# microBoard_power.net
KiCad netlist of a schematic drawn in EAGLE
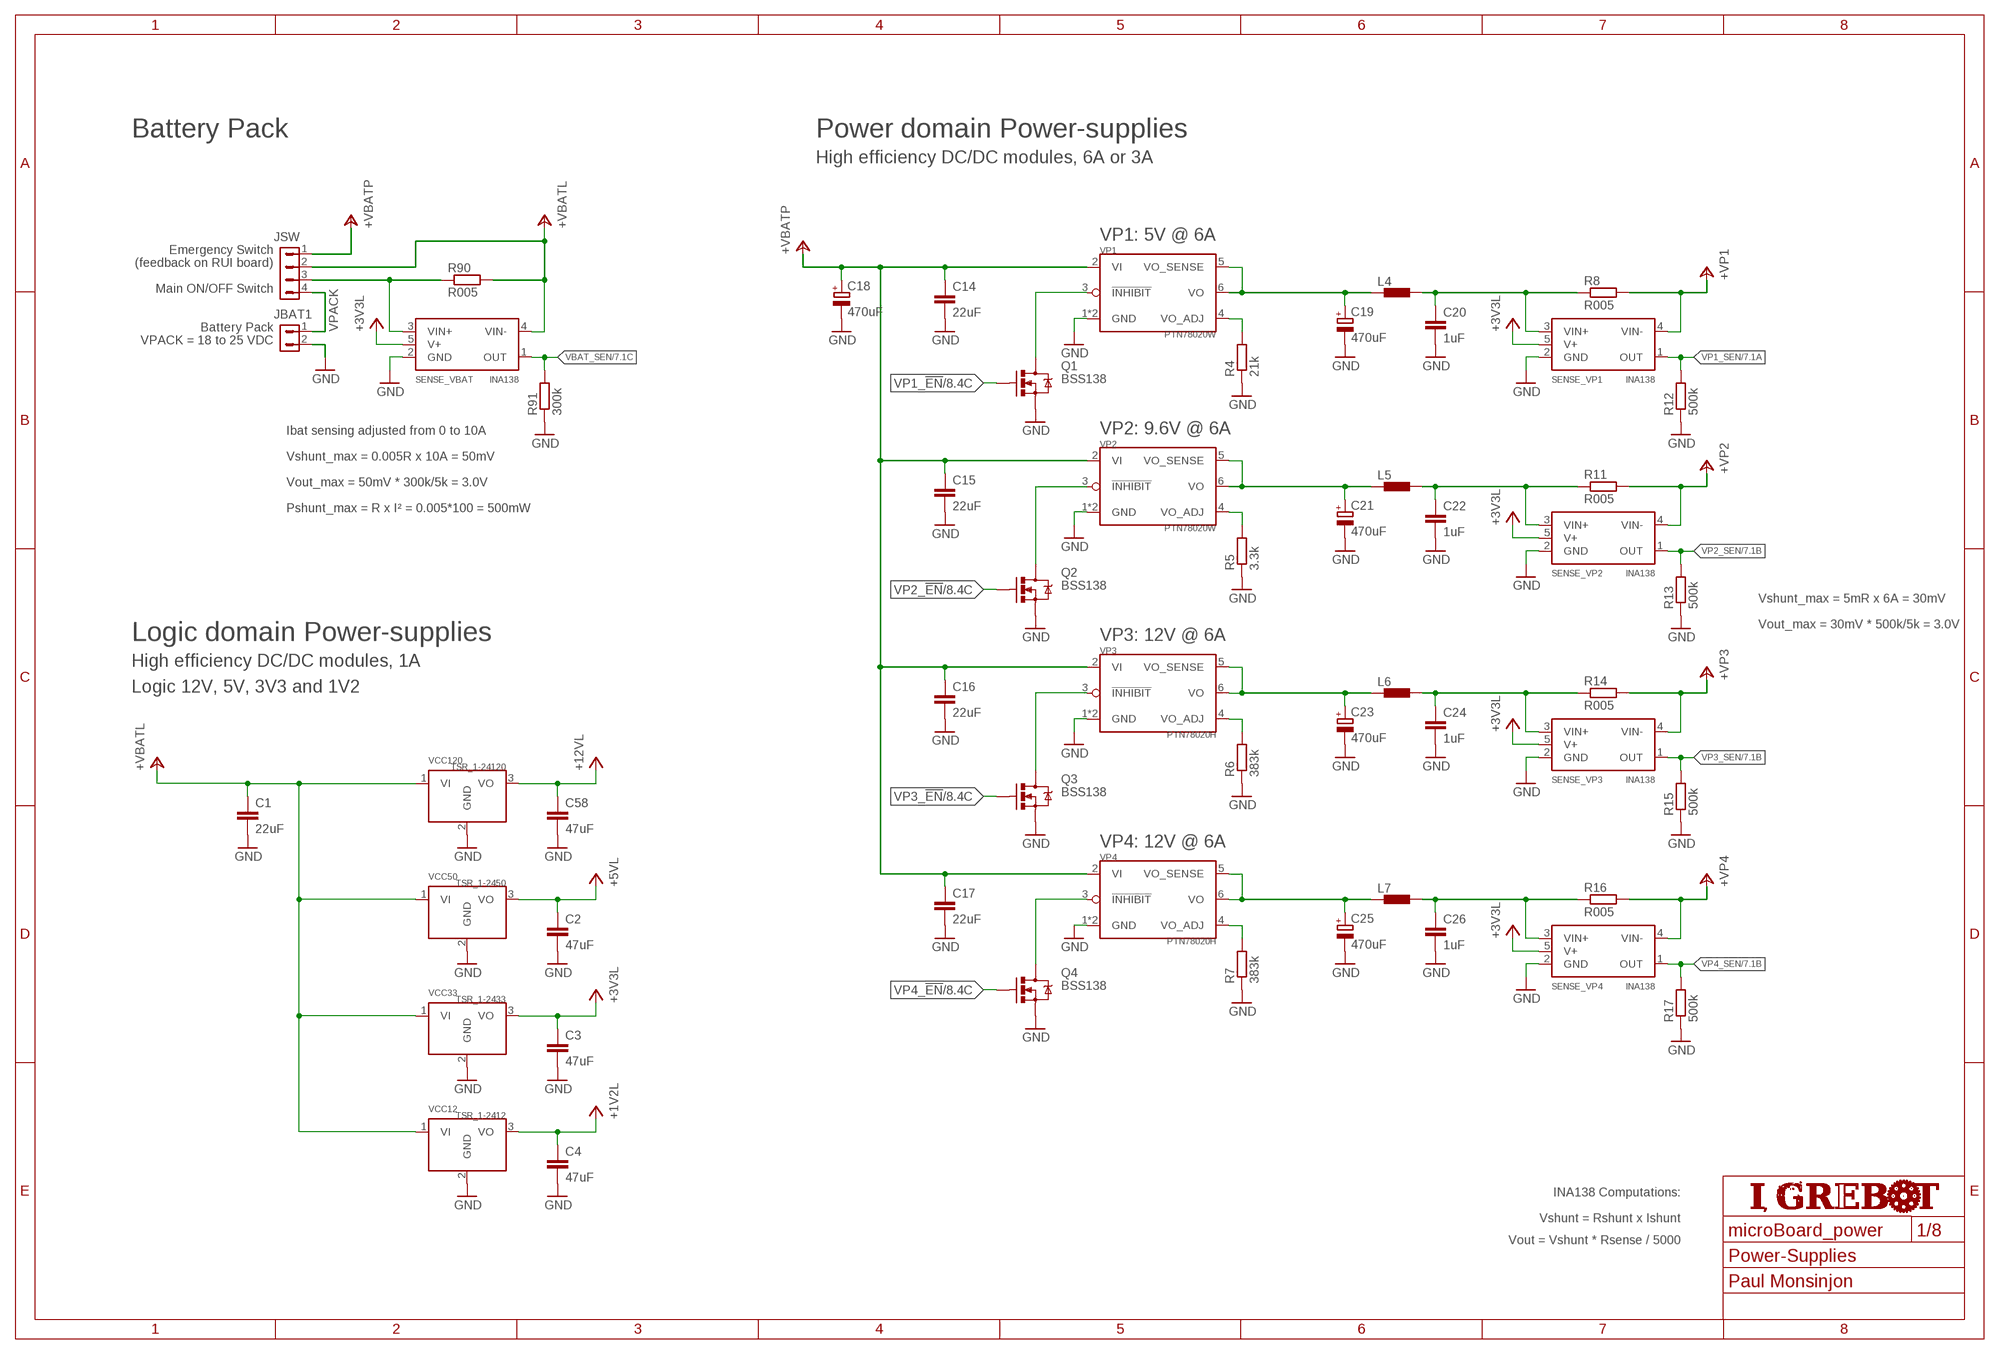
[diagram p0: schematic, sheet 1]
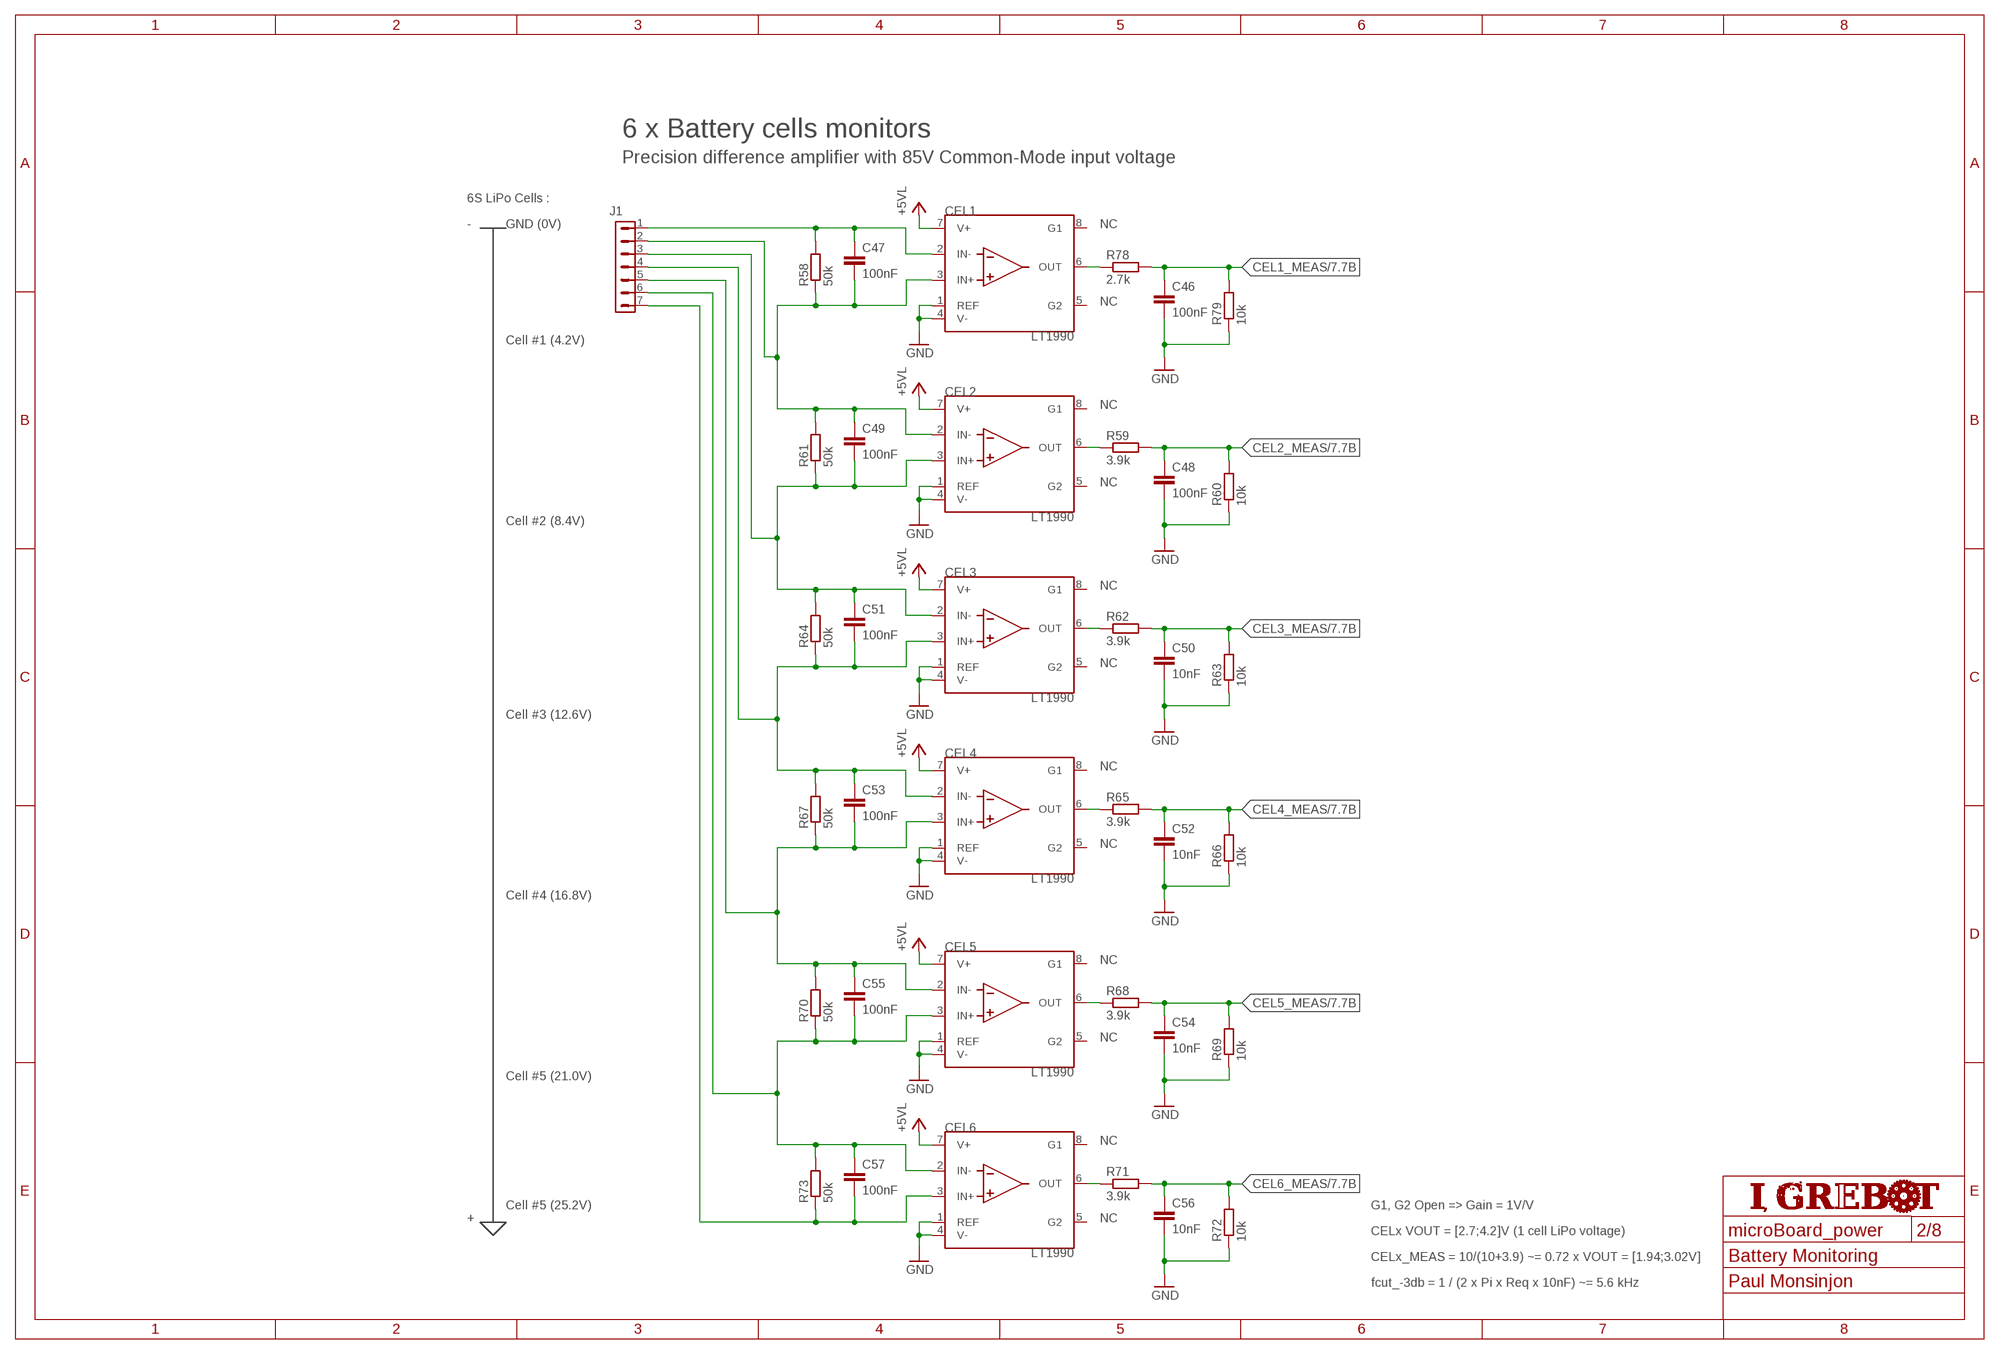
[diagram p1: schematic, sheet 2]
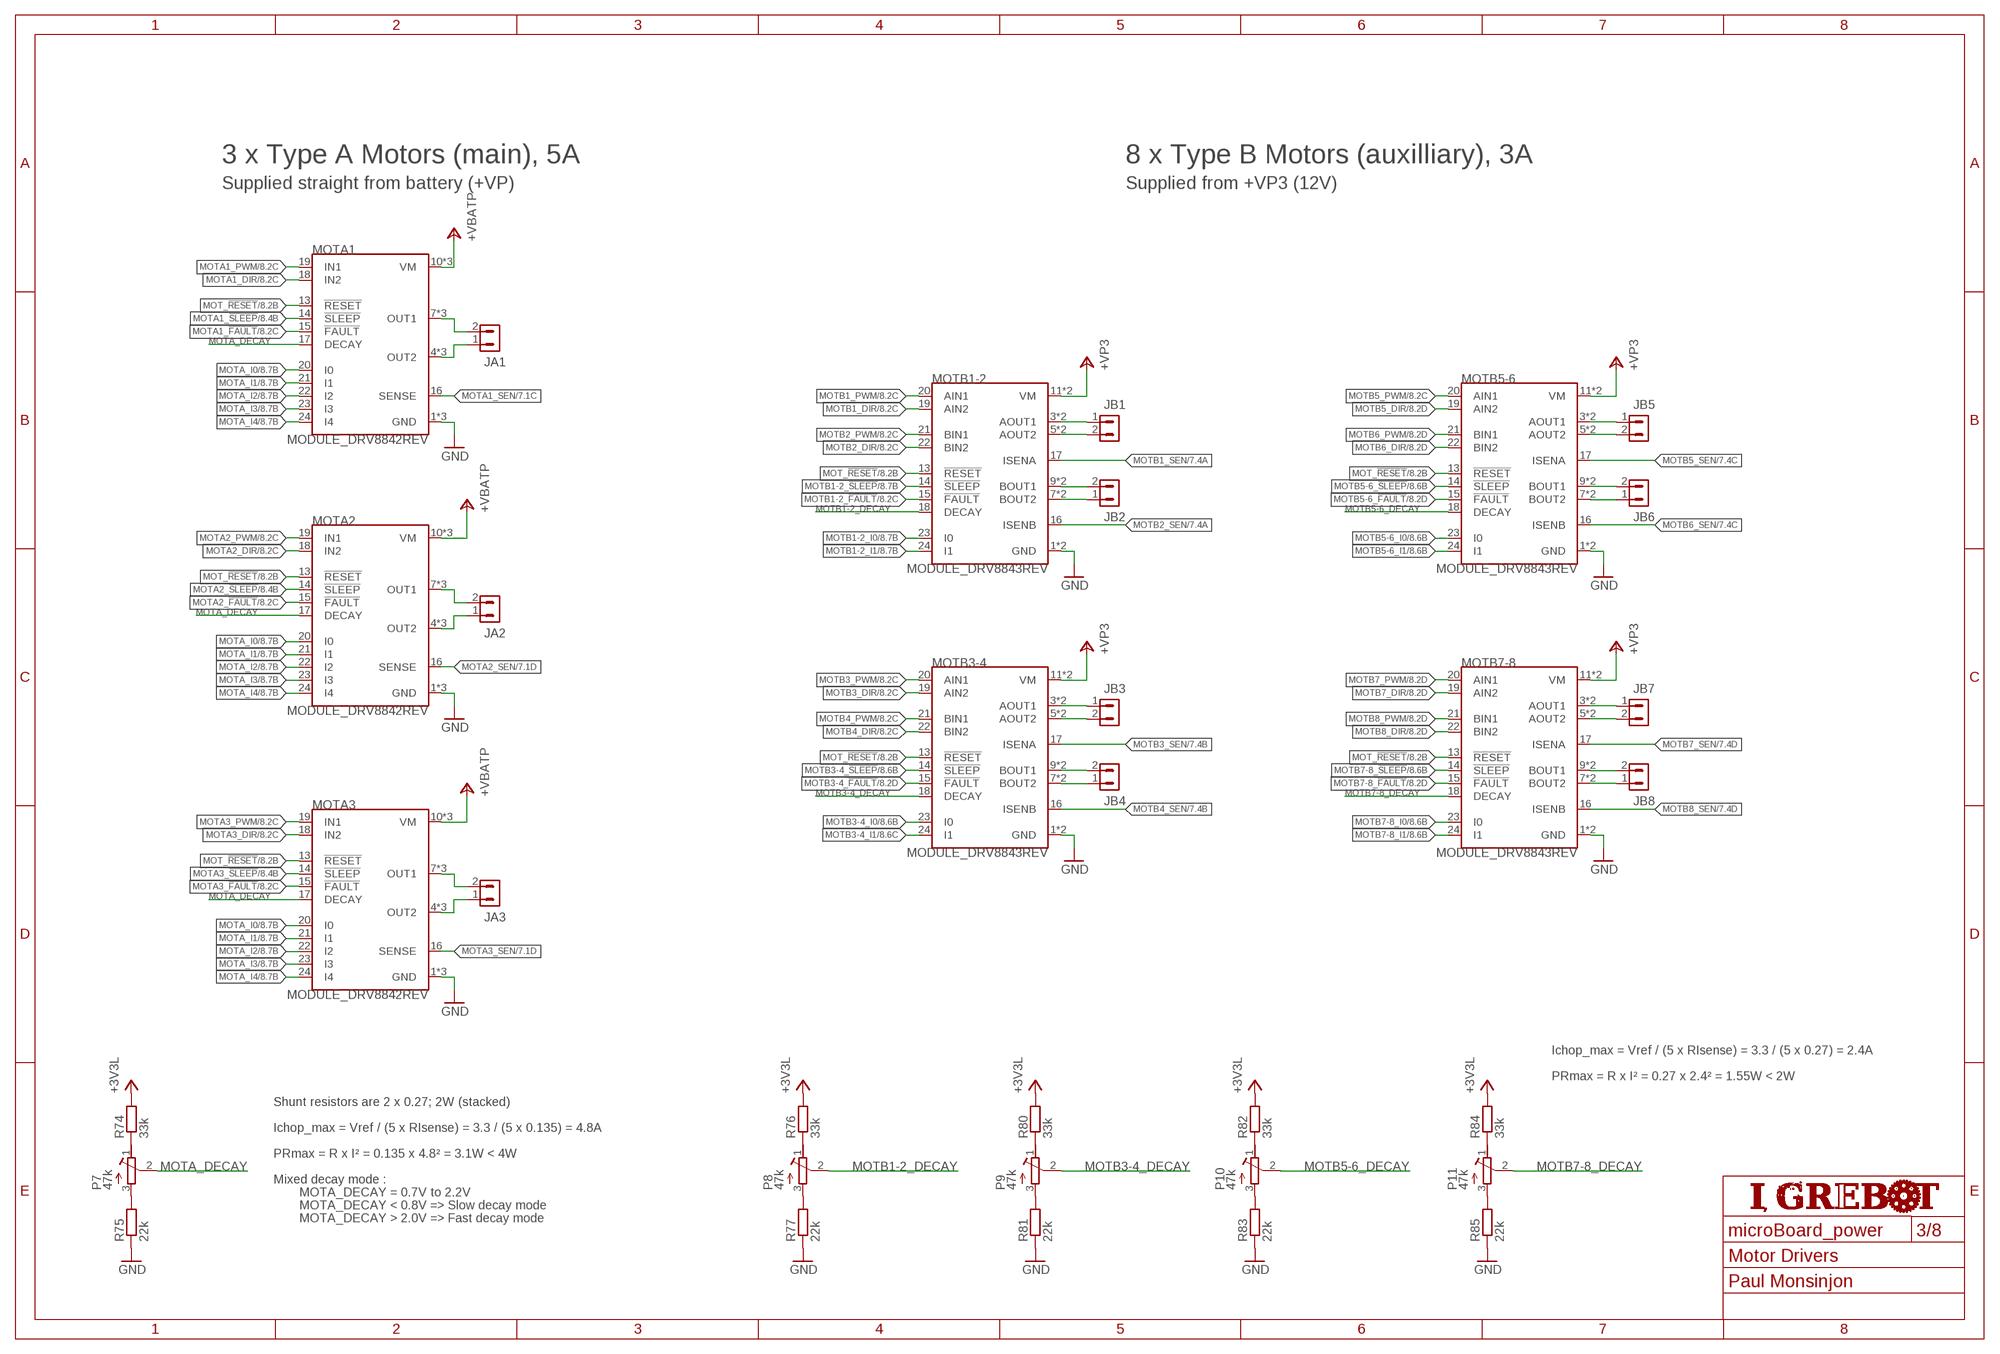
[diagram p2: schematic, sheet 3]
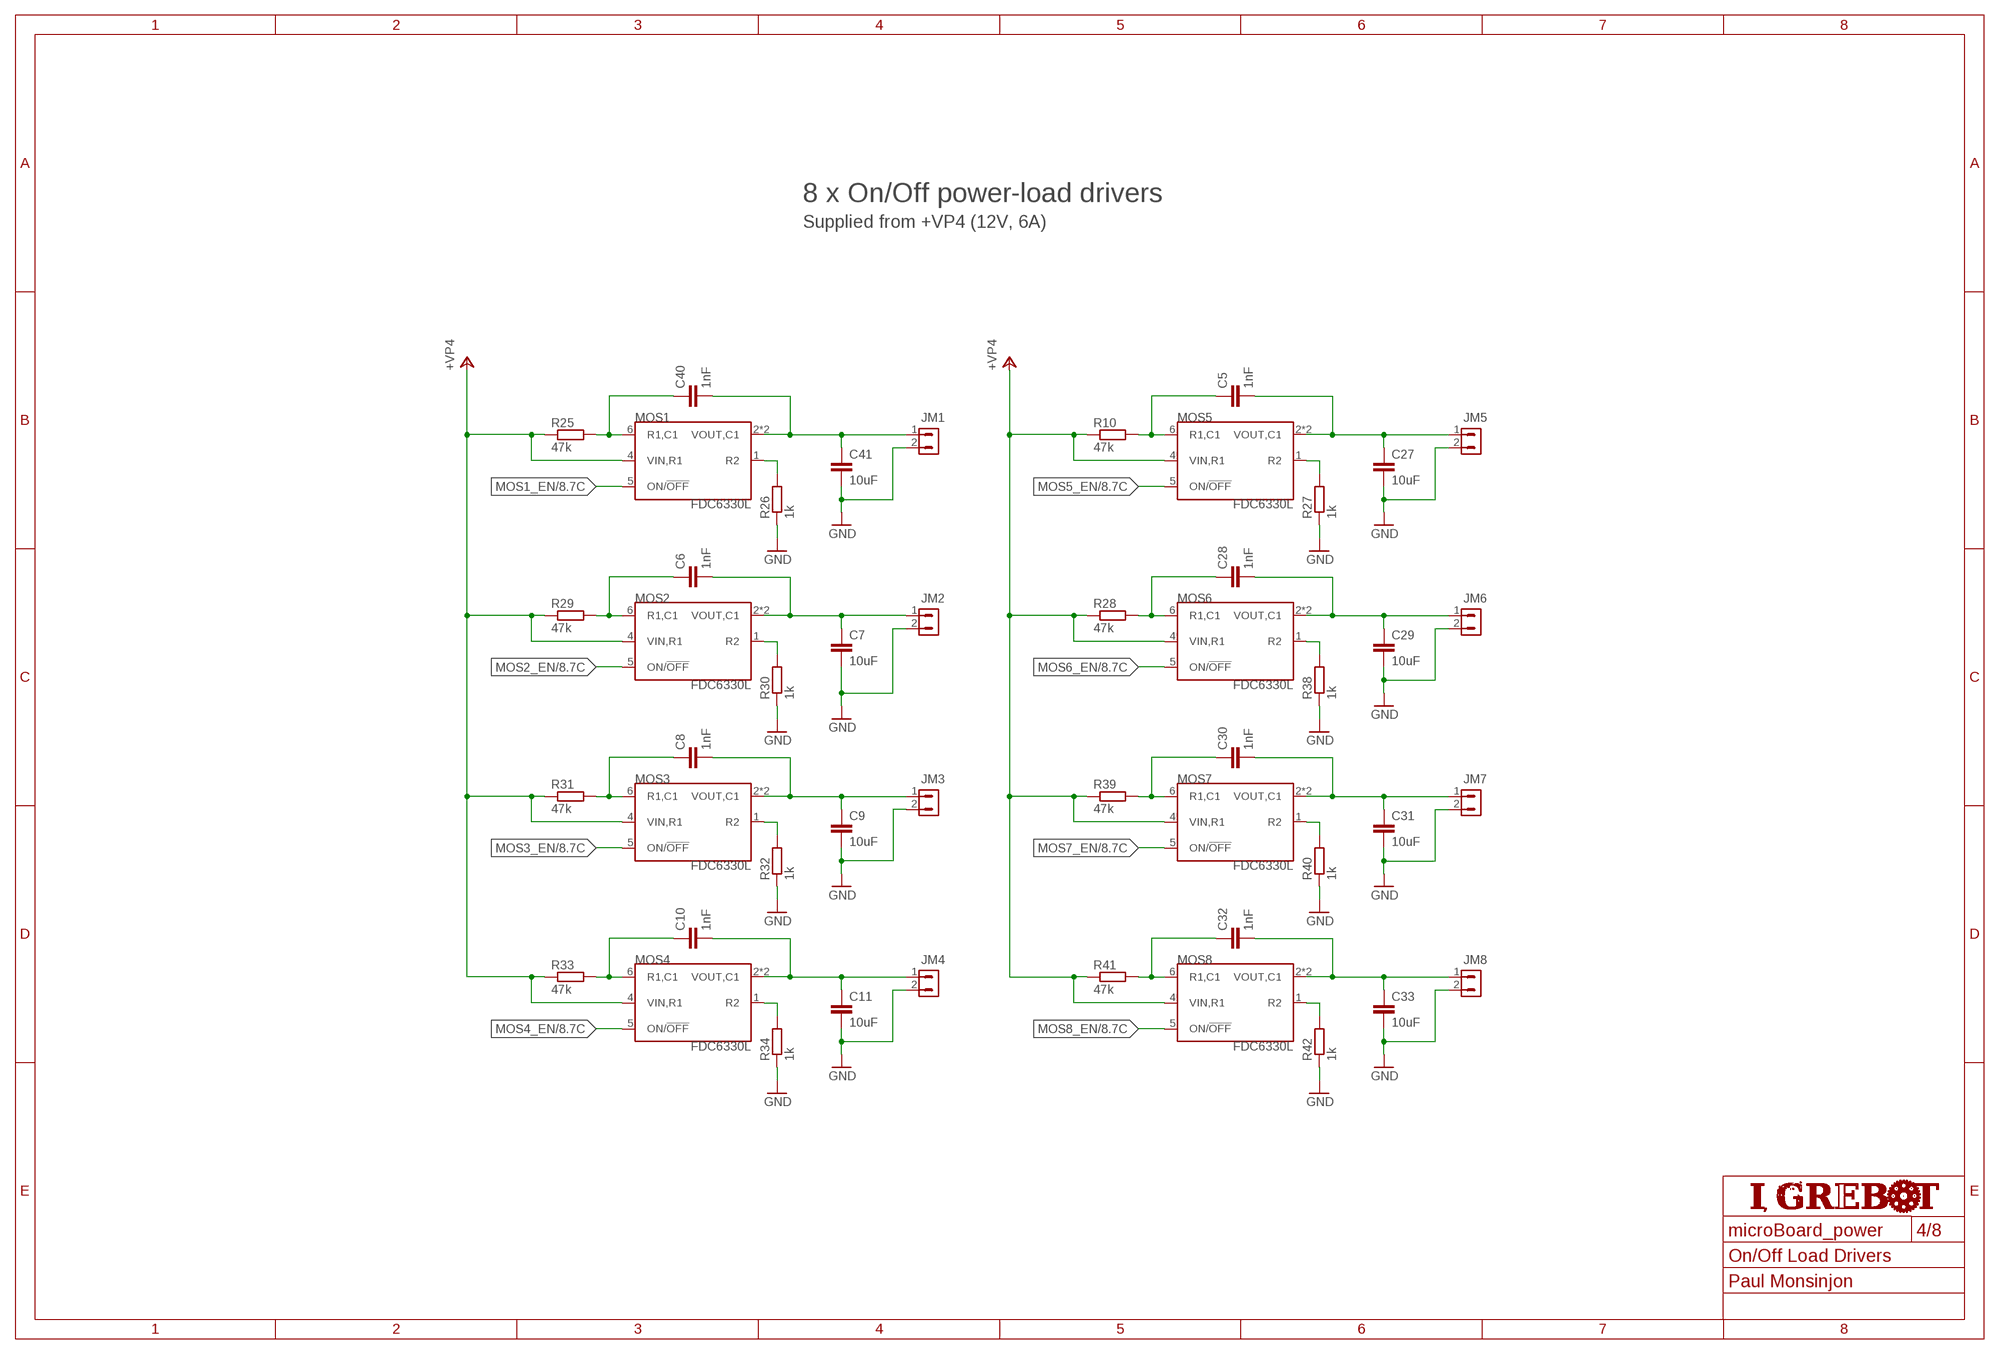
[diagram p3: schematic, sheet 4]
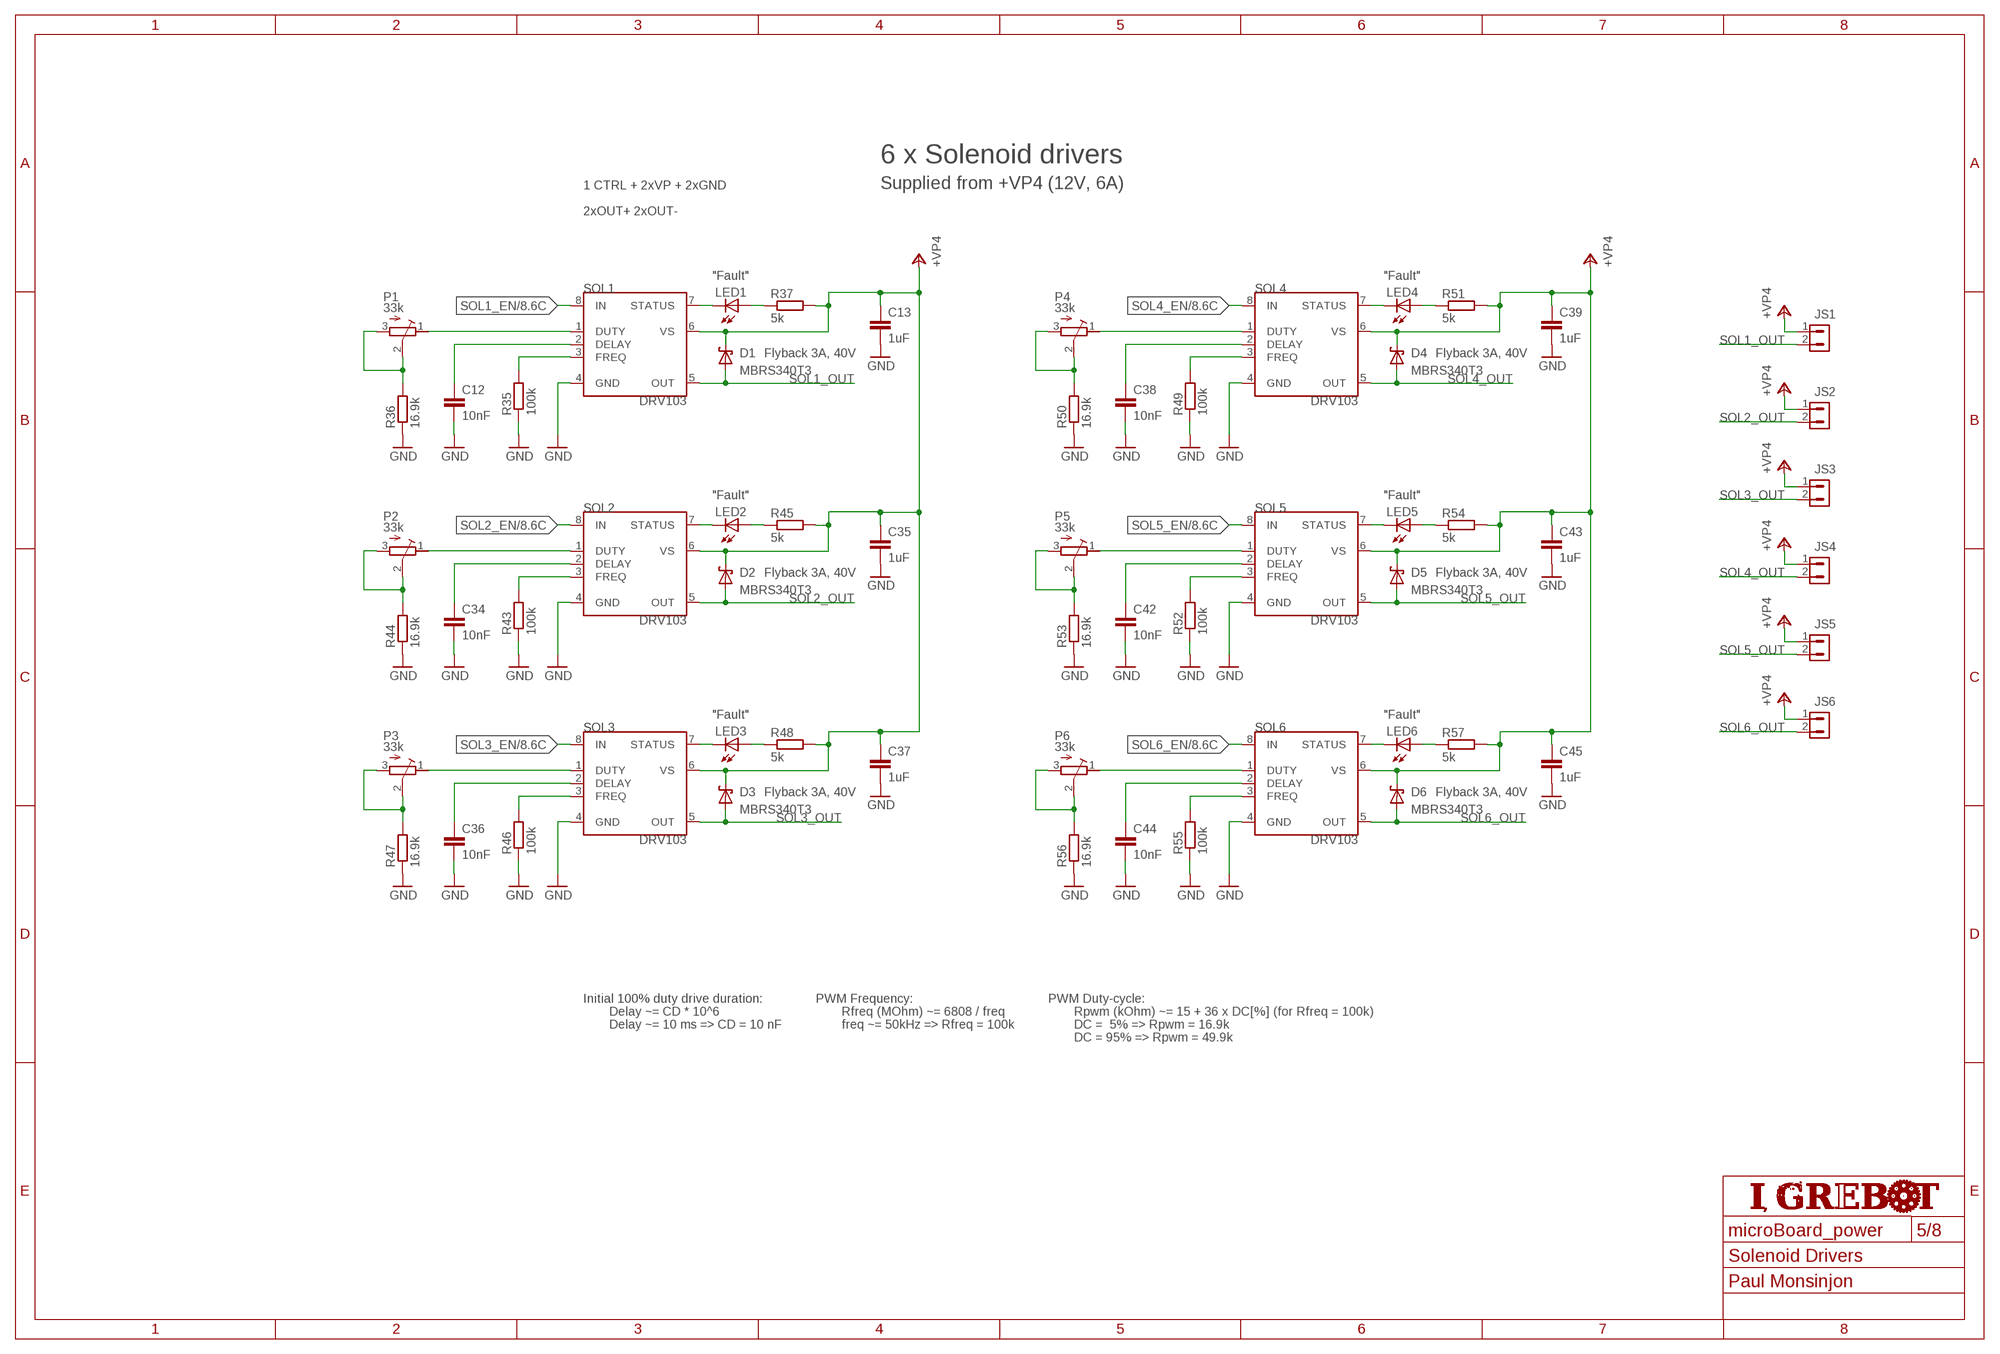
[diagram p4: schematic, sheet 5]
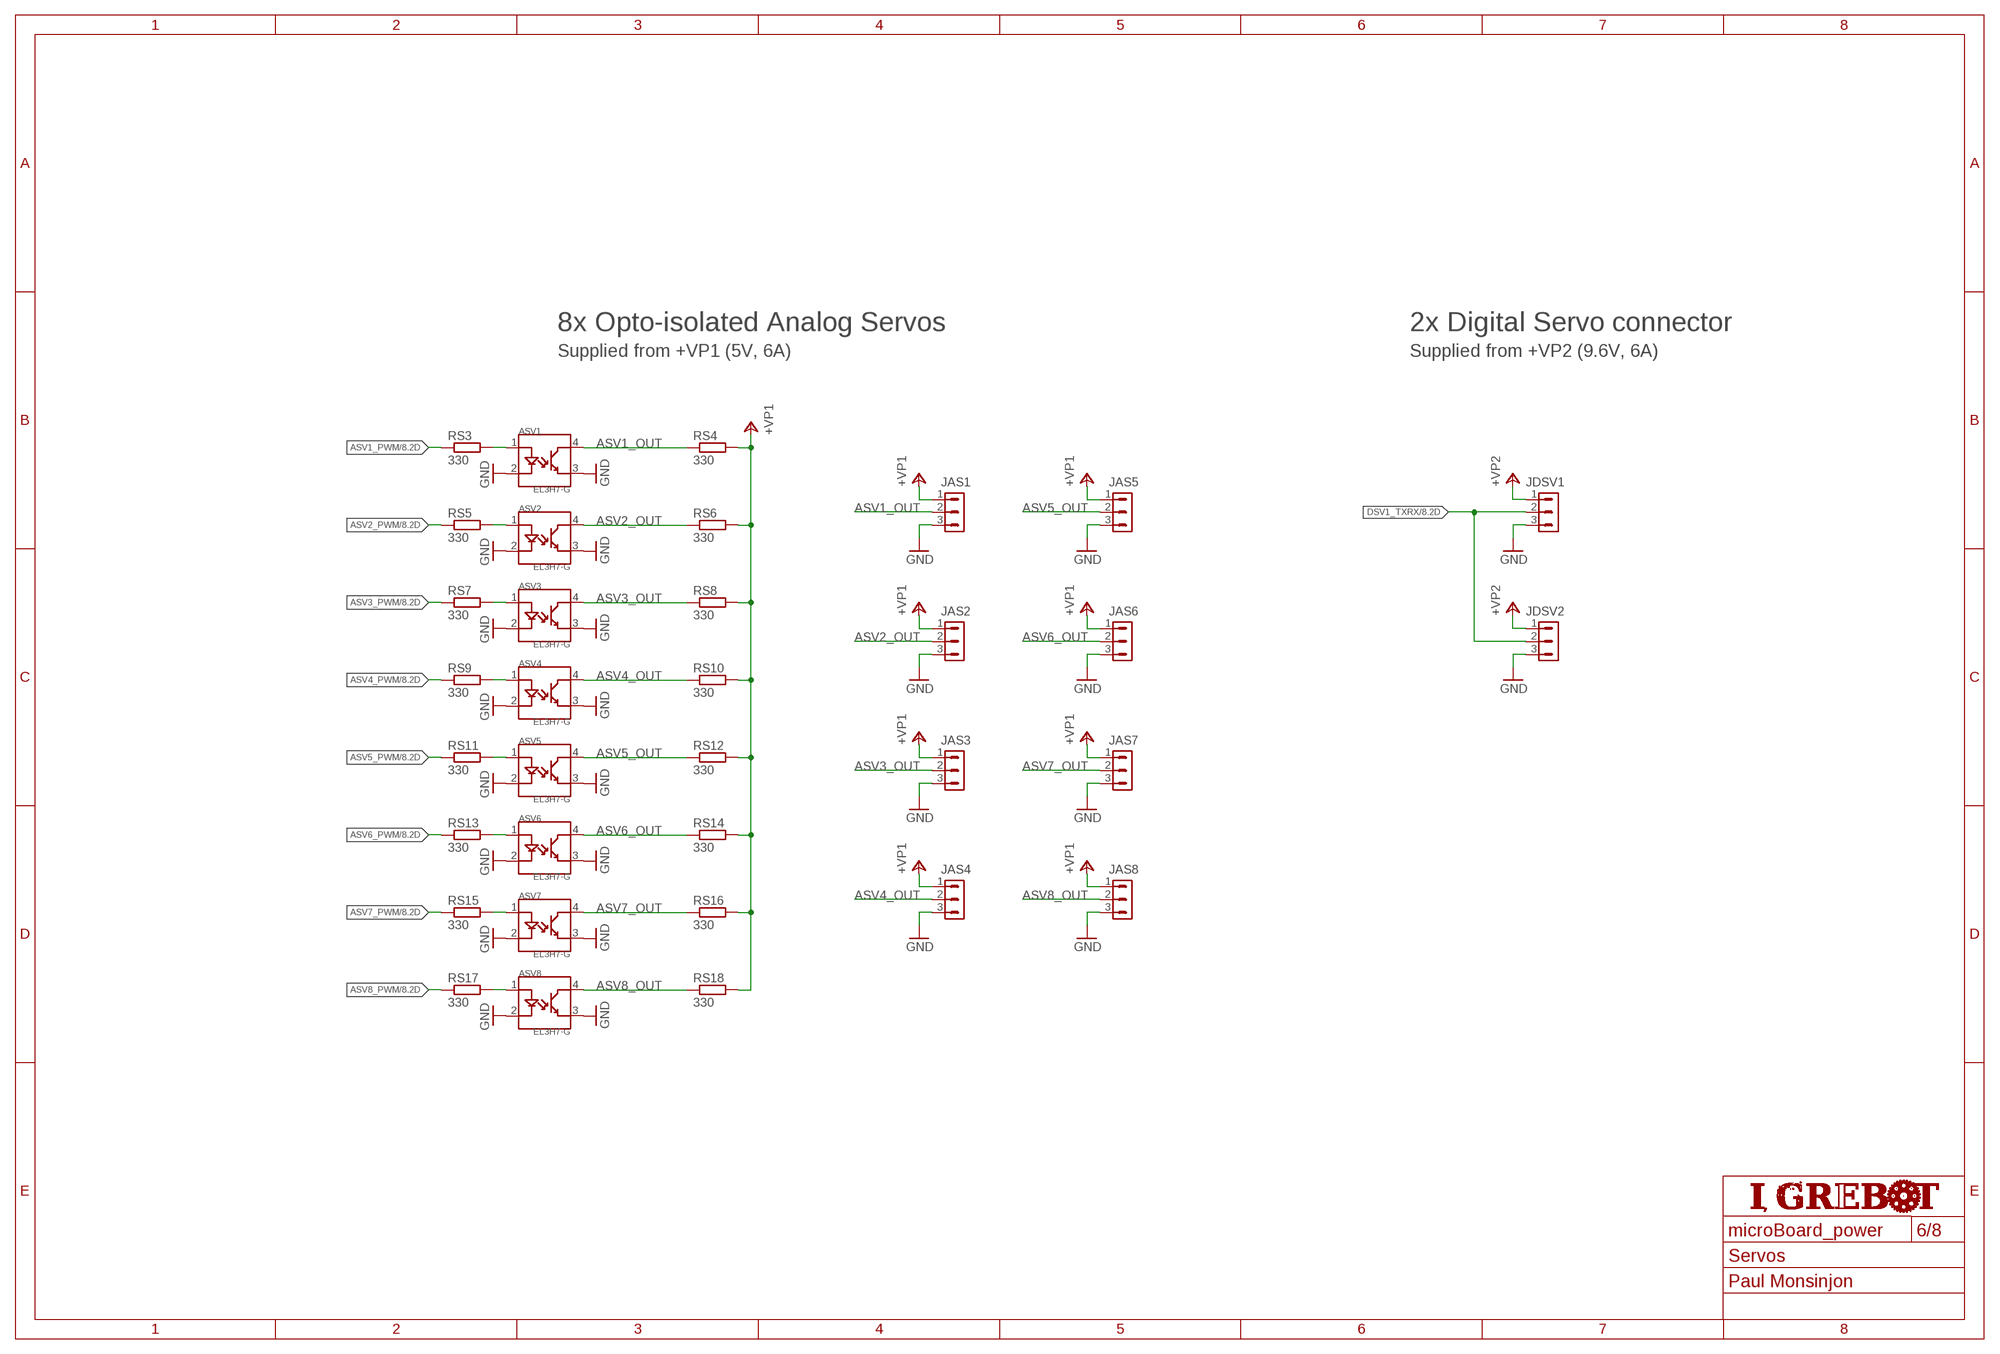
[diagram p5: schematic, sheet 6]
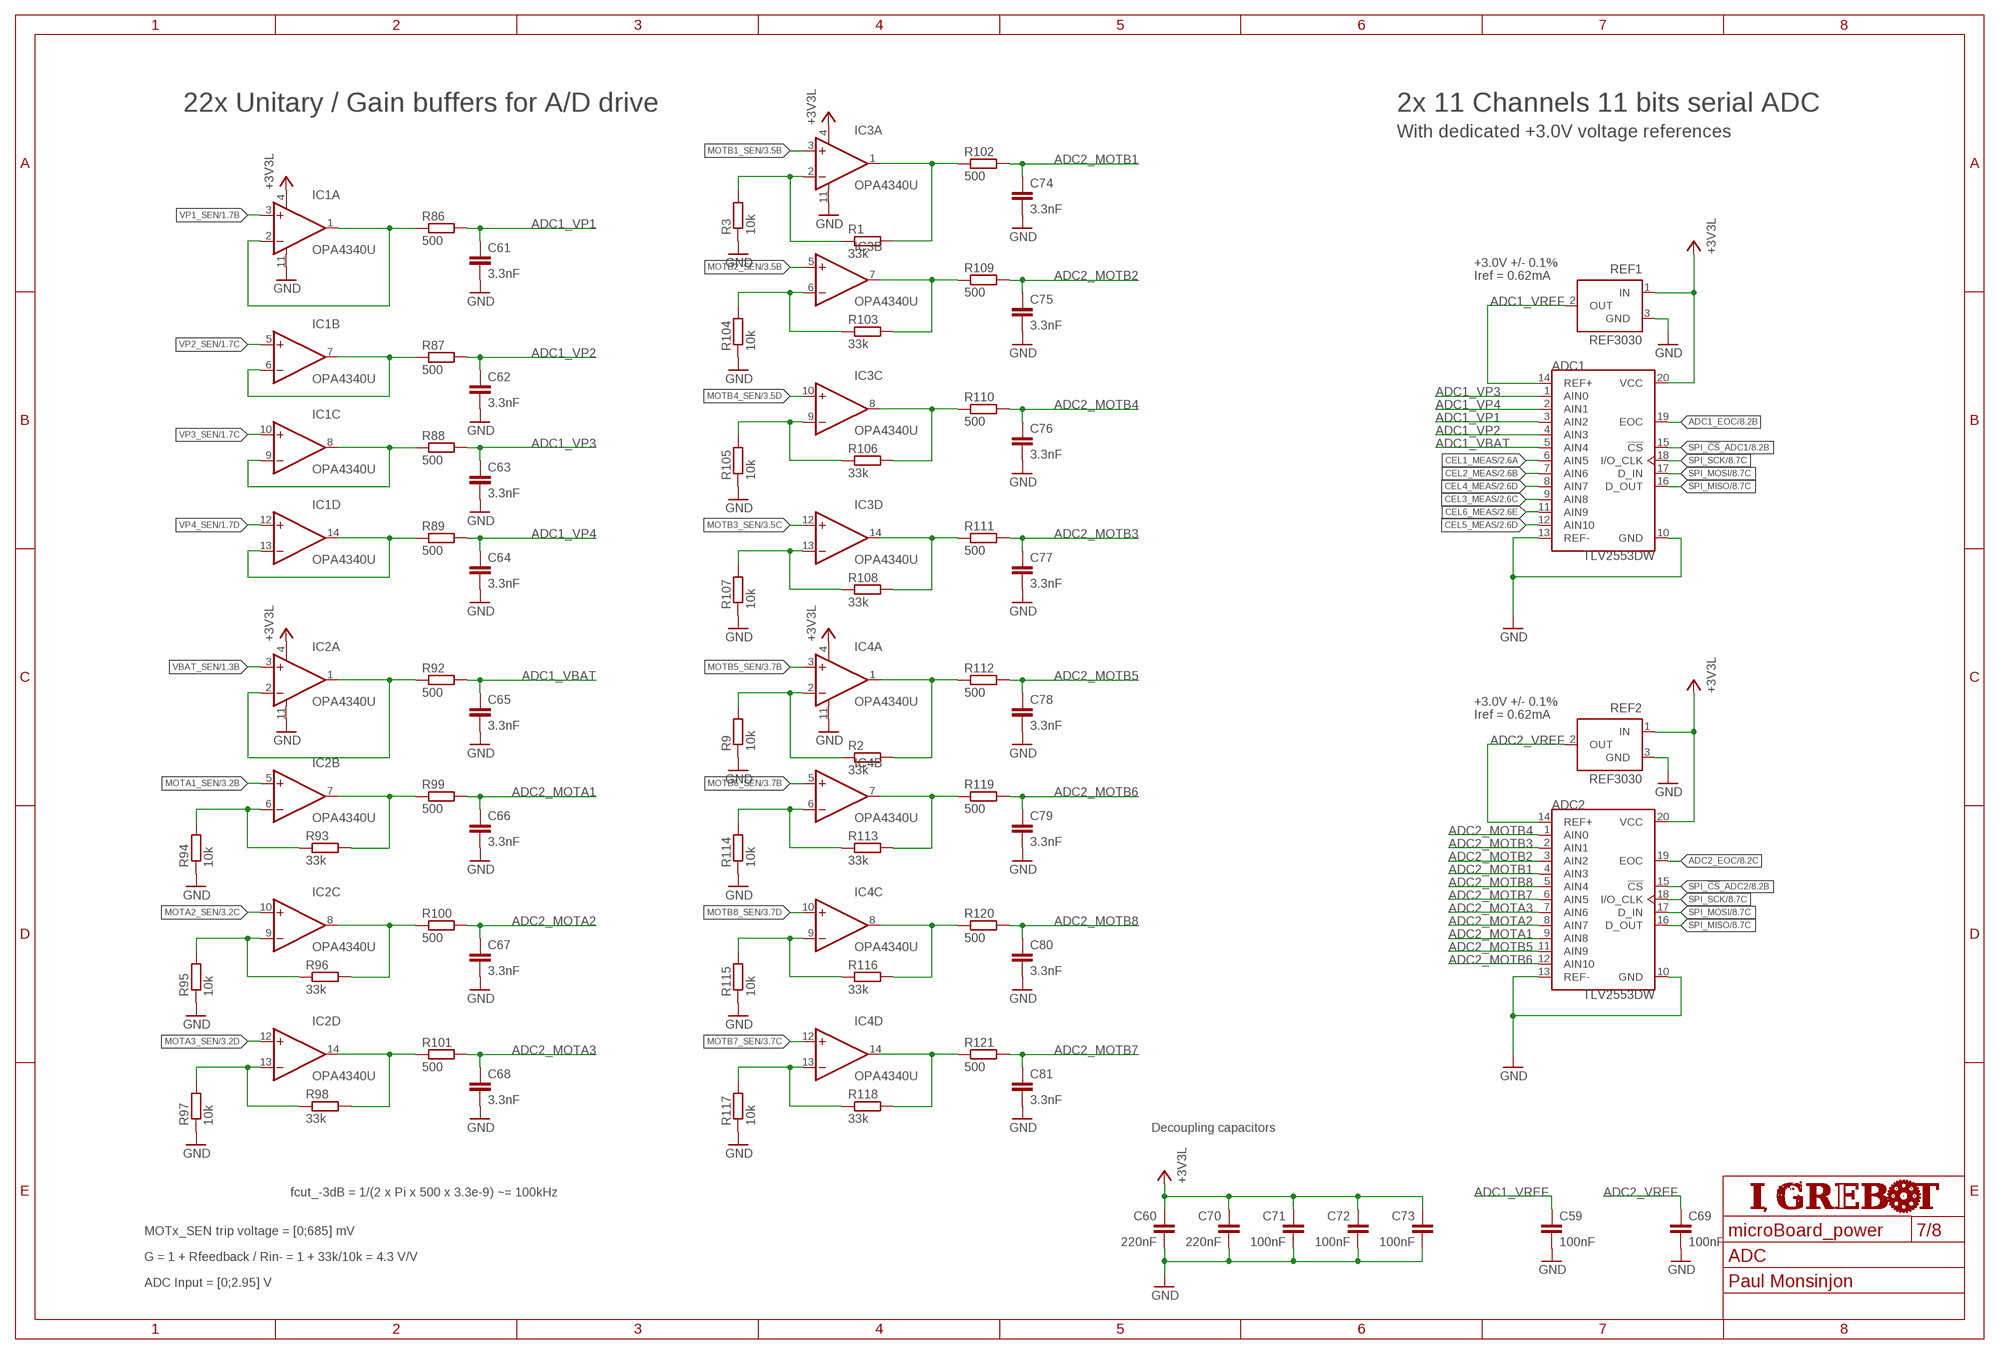
[diagram p6: schematic, sheet 7]
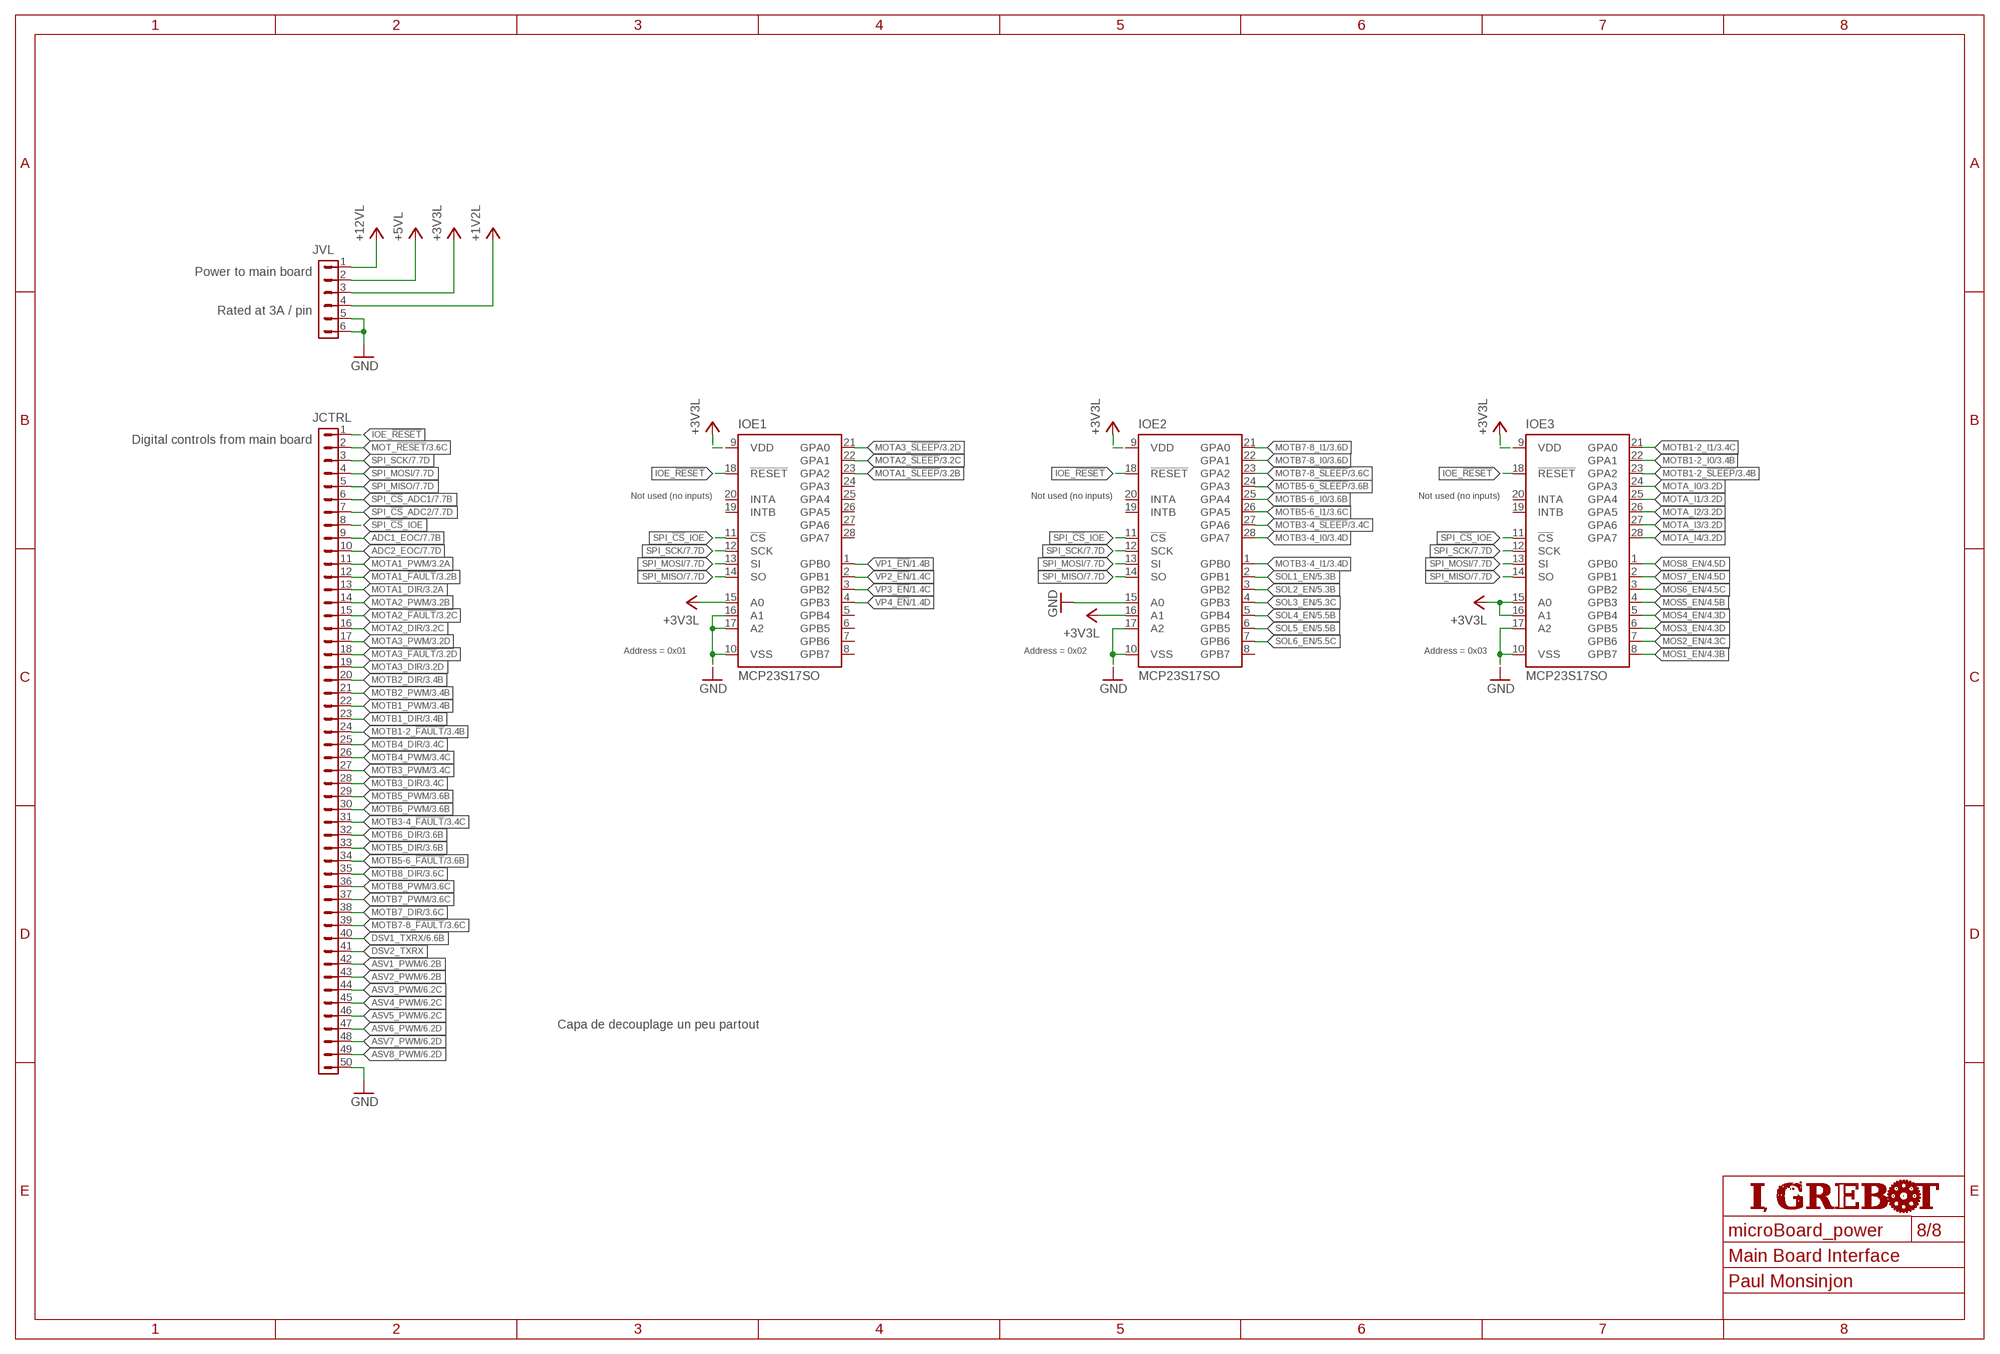
[diagram p7: schematic, sheet 8]

(export (version "E")
  (design (tool "Eeschema 10.0.6"))
  (components
    (comp (ref "ASV1")
      (value "EL3H7-G")
      (footprint "eagle-import:SSOP_4")
      (libsource (lib "eagle-import") (part "EL3H7-G"))
    )
    (comp (ref "ASV2")
      (value "EL3H7-G")
      (footprint "eagle-import:SSOP_4")
      (libsource (lib "eagle-import") (part "EL3H7-G"))
    )
    (comp (ref "ASV3")
      (value "EL3H7-G")
      (footprint "eagle-import:SSOP_4")
      (libsource (lib "eagle-import") (part "EL3H7-G"))
    )
    (comp (ref "ASV4")
      (value "EL3H7-G")
      (footprint "eagle-import:SSOP_4")
      (libsource (lib "eagle-import") (part "EL3H7-G"))
    )
    (comp (ref "ASV5")
      (value "EL3H7-G")
      (footprint "eagle-import:SSOP_4")
      (libsource (lib "eagle-import") (part "EL3H7-G"))
    )
    (comp (ref "ASV6")
      (value "EL3H7-G")
      (footprint "eagle-import:SSOP_4")
      (libsource (lib "eagle-import") (part "EL3H7-G"))
    )
    (comp (ref "ASV7")
      (value "EL3H7-G")
      (footprint "eagle-import:SSOP_4")
      (libsource (lib "eagle-import") (part "EL3H7-G"))
    )
    (comp (ref "ASV8")
      (value "EL3H7-G")
      (footprint "eagle-import:SSOP_4")
      (libsource (lib "eagle-import") (part "EL3H7-G"))
    )
    (comp (ref "JAS1")
      (value "HE14_H_3")
      (footprint "eagle-import:HE14_H_3")
      (libsource (lib "eagle-import") (part "HE14_H_3"))
    )
    (comp (ref "JAS2")
      (value "HE14_H_3")
      (footprint "eagle-import:HE14_H_3")
      (libsource (lib "eagle-import") (part "HE14_H_3"))
    )
    (comp (ref "JAS3")
      (value "HE14_H_3")
      (footprint "eagle-import:HE14_H_3")
      (libsource (lib "eagle-import") (part "HE14_H_3"))
    )
    (comp (ref "JAS4")
      (value "HE14_H_3")
      (footprint "eagle-import:HE14_H_3")
      (libsource (lib "eagle-import") (part "HE14_H_3"))
    )
    (comp (ref "JAS5")
      (value "HE14_H_3")
      (footprint "eagle-import:HE14_H_3")
      (libsource (lib "eagle-import") (part "HE14_H_3"))
    )
    (comp (ref "JAS6")
      (value "HE14_H_3")
      (footprint "eagle-import:HE14_H_3")
      (libsource (lib "eagle-import") (part "HE14_H_3"))
    )
    (comp (ref "JAS7")
      (value "HE14_H_3")
      (footprint "eagle-import:HE14_H_3")
      (libsource (lib "eagle-import") (part "HE14_H_3"))
    )
    (comp (ref "JAS8")
      (value "HE14_H_3")
      (footprint "eagle-import:HE14_H_3")
      (libsource (lib "eagle-import") (part "HE14_H_3"))
    )
    (comp (ref "JDSV1")
      (value "HE14_H_3")
      (footprint "eagle-import:HE14_H_3")
      (libsource (lib "eagle-import") (part "HE14_H_3"))
    )
    (comp (ref "JDSV2")
      (value "HE14_H_3")
      (footprint "eagle-import:HE14_H_3")
      (libsource (lib "eagle-import") (part "HE14_H_3"))
    )
    (comp (ref "RS3")
      (value "330")
      (footprint "eagle-import:R0603")
      (libsource (lib "eagle-import") (part "resistor_R-EU_R0603"))
    )
    (comp (ref "RS4")
      (value "330")
      (footprint "eagle-import:R0603")
      (libsource (lib "eagle-import") (part "resistor_R-EU_R0603"))
    )
    (comp (ref "RS5")
      (value "330")
      (footprint "eagle-import:R0603")
      (libsource (lib "eagle-import") (part "resistor_R-EU_R0603"))
    )
    (comp (ref "RS6")
      (value "330")
      (footprint "eagle-import:R0603")
      (libsource (lib "eagle-import") (part "resistor_R-EU_R0603"))
    )
    (comp (ref "RS7")
      (value "330")
      (footprint "eagle-import:R0603")
      (libsource (lib "eagle-import") (part "resistor_R-EU_R0603"))
    )
    (comp (ref "RS8")
      (value "330")
      (footprint "eagle-import:R0603")
      (libsource (lib "eagle-import") (part "resistor_R-EU_R0603"))
    )
    (comp (ref "RS9")
      (value "330")
      (footprint "eagle-import:R0603")
      (libsource (lib "eagle-import") (part "resistor_R-EU_R0603"))
    )
    (comp (ref "RS10")
      (value "330")
      (footprint "eagle-import:R0603")
      (libsource (lib "eagle-import") (part "resistor_R-EU_R0603"))
    )
    (comp (ref "RS11")
      (value "330")
      (footprint "eagle-import:R0603")
      (libsource (lib "eagle-import") (part "resistor_R-EU_R0603"))
    )
    (comp (ref "RS12")
      (value "330")
      (footprint "eagle-import:R0603")
      (libsource (lib "eagle-import") (part "resistor_R-EU_R0603"))
    )
    (comp (ref "RS13")
      (value "330")
      (footprint "eagle-import:R0603")
      (libsource (lib "eagle-import") (part "resistor_R-EU_R0603"))
    )
    (comp (ref "RS14")
      (value "330")
      (footprint "eagle-import:R0603")
      (libsource (lib "eagle-import") (part "resistor_R-EU_R0603"))
    )
    (comp (ref "RS15")
      (value "330")
      (footprint "eagle-import:R0603")
      (libsource (lib "eagle-import") (part "resistor_R-EU_R0603"))
    )
    (comp (ref "RS16")
      (value "330")
      (footprint "eagle-import:R0603")
      (libsource (lib "eagle-import") (part "resistor_R-EU_R0603"))
    )
    (comp (ref "RS17")
      (value "330")
      (footprint "eagle-import:R0603")
      (libsource (lib "eagle-import") (part "resistor_R-EU_R0603"))
    )
    (comp (ref "RS18")
      (value "330")
      (footprint "eagle-import:R0603")
      (libsource (lib "eagle-import") (part "resistor_R-EU_R0603"))
    )
    (comp (ref "C46")
      (value "100nF")
      (footprint "eagle-import:C0603")
      (libsource (lib "eagle-import") (part "C-EUC0603"))
    )
    (comp (ref "C47")
      (value "100nF")
      (footprint "eagle-import:C0603")
      (libsource (lib "eagle-import") (part "C-EUC0603"))
    )
    (comp (ref "C48")
      (value "100nF")
      (footprint "eagle-import:C0603")
      (libsource (lib "eagle-import") (part "C-EUC0603"))
    )
    (comp (ref "C49")
      (value "100nF")
      (footprint "eagle-import:C0603")
      (libsource (lib "eagle-import") (part "C-EUC0603"))
    )
    (comp (ref "C50")
      (value "10nF")
      (footprint "eagle-import:C0603")
      (libsource (lib "eagle-import") (part "C-EUC0603"))
    )
    (comp (ref "C51")
      (value "100nF")
      (footprint "eagle-import:C0603")
      (libsource (lib "eagle-import") (part "C-EUC0603"))
    )
    (comp (ref "C52")
      (value "10nF")
      (footprint "eagle-import:C0603")
      (libsource (lib "eagle-import") (part "C-EUC0603"))
    )
    (comp (ref "C53")
      (value "100nF")
      (footprint "eagle-import:C0603")
      (libsource (lib "eagle-import") (part "C-EUC0603"))
    )
    (comp (ref "C54")
      (value "10nF")
      (footprint "eagle-import:C0603")
      (libsource (lib "eagle-import") (part "C-EUC0603"))
    )
    (comp (ref "C55")
      (value "100nF")
      (footprint "eagle-import:C0603")
      (libsource (lib "eagle-import") (part "C-EUC0603"))
    )
    (comp (ref "C56")
      (value "10nF")
      (footprint "eagle-import:C0603")
      (libsource (lib "eagle-import") (part "C-EUC0603"))
    )
    (comp (ref "C57")
      (value "100nF")
      (footprint "eagle-import:C0603")
      (libsource (lib "eagle-import") (part "C-EUC0603"))
    )
    (comp (ref "CEL1")
      (value "LT1990")
      (footprint "eagle-import:S8")
      (libsource (lib "eagle-import") (part "LT1990"))
    )
    (comp (ref "CEL2")
      (value "LT1990")
      (footprint "eagle-import:S8")
      (libsource (lib "eagle-import") (part "LT1990"))
    )
    (comp (ref "CEL3")
      (value "LT1990")
      (footprint "eagle-import:S8")
      (libsource (lib "eagle-import") (part "LT1990"))
    )
    (comp (ref "CEL4")
      (value "LT1990")
      (footprint "eagle-import:S8")
      (libsource (lib "eagle-import") (part "LT1990"))
    )
    (comp (ref "CEL5")
      (value "LT1990")
      (footprint "eagle-import:S8")
      (libsource (lib "eagle-import") (part "LT1990"))
    )
    (comp (ref "CEL6")
      (value "LT1990")
      (footprint "eagle-import:S8")
      (libsource (lib "eagle-import") (part "LT1990"))
    )
    (comp (ref "J1")
      (value "JST-XH-S_7")
      (footprint "eagle-import:JST-XH-7S")
      (libsource (lib "eagle-import") (part "JST-XH-S_7"))
    )
    (comp (ref "R58")
      (value "50k")
      (footprint "eagle-import:R0603")
      (libsource (lib "eagle-import") (part "resistor_R-EU_R0603"))
    )
    (comp (ref "R59")
      (value "3.9k")
      (footprint "eagle-import:R0603")
      (libsource (lib "eagle-import") (part "resistor_R-EU_R0603"))
    )
    (comp (ref "R60")
      (value "10k")
      (footprint "eagle-import:R0603")
      (libsource (lib "eagle-import") (part "resistor_R-EU_R0603"))
    )
    (comp (ref "R61")
      (value "50k")
      (footprint "eagle-import:R0603")
      (libsource (lib "eagle-import") (part "resistor_R-EU_R0603"))
    )
    (comp (ref "R62")
      (value "3.9k")
      (footprint "eagle-import:R0603")
      (libsource (lib "eagle-import") (part "resistor_R-EU_R0603"))
    )
    (comp (ref "R63")
      (value "10k")
      (footprint "eagle-import:R0603")
      (libsource (lib "eagle-import") (part "resistor_R-EU_R0603"))
    )
    (comp (ref "R64")
      (value "50k")
      (footprint "eagle-import:R0603")
      (libsource (lib "eagle-import") (part "resistor_R-EU_R0603"))
    )
    (comp (ref "R65")
      (value "3.9k")
      (footprint "eagle-import:R0603")
      (libsource (lib "eagle-import") (part "resistor_R-EU_R0603"))
    )
    (comp (ref "R66")
      (value "10k")
      (footprint "eagle-import:R0603")
      (libsource (lib "eagle-import") (part "resistor_R-EU_R0603"))
    )
    (comp (ref "R67")
      (value "50k")
      (footprint "eagle-import:R0603")
      (libsource (lib "eagle-import") (part "resistor_R-EU_R0603"))
    )
    (comp (ref "R68")
      (value "3.9k")
      (footprint "eagle-import:R0603")
      (libsource (lib "eagle-import") (part "resistor_R-EU_R0603"))
    )
    (comp (ref "R69")
      (value "10k")
      (footprint "eagle-import:R0603")
      (libsource (lib "eagle-import") (part "resistor_R-EU_R0603"))
    )
    (comp (ref "R70")
      (value "50k")
      (footprint "eagle-import:R0603")
      (libsource (lib "eagle-import") (part "resistor_R-EU_R0603"))
    )
    (comp (ref "R71")
      (value "3.9k")
      (footprint "eagle-import:R0603")
      (libsource (lib "eagle-import") (part "resistor_R-EU_R0603"))
    )
    (comp (ref "R72")
      (value "10k")
      (footprint "eagle-import:R0603")
      (libsource (lib "eagle-import") (part "resistor_R-EU_R0603"))
    )
    (comp (ref "R73")
      (value "50k")
      (footprint "eagle-import:R0603")
      (libsource (lib "eagle-import") (part "resistor_R-EU_R0603"))
    )
    (comp (ref "R78")
      (value "2.7k")
      (footprint "eagle-import:R0603")
      (libsource (lib "eagle-import") (part "resistor_R-EU_R0603"))
    )
    (comp (ref "R79")
      (value "10k")
      (footprint "eagle-import:R0603")
      (libsource (lib "eagle-import") (part "resistor_R-EU_R0603"))
    )
    (comp (ref "ADC1")
      (value "TLV2553DW")
      (footprint "eagle-import:SSOP_20")
      (libsource (lib "eagle-import") (part "TLV2553DW"))
    )
    (comp (ref "ADC2")
      (value "TLV2553DW")
      (footprint "eagle-import:SSOP_20")
      (libsource (lib "eagle-import") (part "TLV2553DW"))
    )
    (comp (ref "C59")
      (value "100nF")
      (footprint "eagle-import:C0603")
      (libsource (lib "eagle-import") (part "C-EUC0603"))
    )
    (comp (ref "C60")
      (value "220nF")
      (footprint "eagle-import:C0603")
      (libsource (lib "eagle-import") (part "C-EUC0603"))
    )
    (comp (ref "C61")
      (value "3.3nF")
      (footprint "eagle-import:C0603")
      (libsource (lib "eagle-import") (part "C-EUC0603"))
    )
    (comp (ref "C62")
      (value "3.3nF")
      (footprint "eagle-import:C0603")
      (libsource (lib "eagle-import") (part "C-EUC0603"))
    )
    (comp (ref "C63")
      (value "3.3nF")
      (footprint "eagle-import:C0603")
      (libsource (lib "eagle-import") (part "C-EUC0603"))
    )
    (comp (ref "C64")
      (value "3.3nF")
      (footprint "eagle-import:C0603")
      (libsource (lib "eagle-import") (part "C-EUC0603"))
    )
    (comp (ref "C65")
      (value "3.3nF")
      (footprint "eagle-import:C0603")
      (libsource (lib "eagle-import") (part "C-EUC0603"))
    )
    (comp (ref "C66")
      (value "3.3nF")
      (footprint "eagle-import:C0603")
      (libsource (lib "eagle-import") (part "C-EUC0603"))
    )
    (comp (ref "C67")
      (value "3.3nF")
      (footprint "eagle-import:C0603")
      (libsource (lib "eagle-import") (part "C-EUC0603"))
    )
    (comp (ref "C68")
      (value "3.3nF")
      (footprint "eagle-import:C0603")
      (libsource (lib "eagle-import") (part "C-EUC0603"))
    )
    (comp (ref "C69")
      (value "100nF")
      (footprint "eagle-import:C0603")
      (libsource (lib "eagle-import") (part "C-EUC0603"))
    )
    (comp (ref "C70")
      (value "220nF")
      (footprint "eagle-import:C0603")
      (libsource (lib "eagle-import") (part "C-EUC0603"))
    )
    (comp (ref "C71")
      (value "100nF")
      (footprint "eagle-import:C0603")
      (libsource (lib "eagle-import") (part "C-EUC0603"))
    )
    (comp (ref "C72")
      (value "100nF")
      (footprint "eagle-import:C0603")
      (libsource (lib "eagle-import") (part "C-EUC0603"))
    )
    (comp (ref "C73")
      (value "100nF")
      (footprint "eagle-import:C0603")
      (libsource (lib "eagle-import") (part "C-EUC0603"))
    )
    (comp (ref "C74")
      (value "3.3nF")
      (footprint "eagle-import:C0603")
      (libsource (lib "eagle-import") (part "C-EUC0603"))
    )
    (comp (ref "C75")
      (value "3.3nF")
      (footprint "eagle-import:C0603")
      (libsource (lib "eagle-import") (part "C-EUC0603"))
    )
    (comp (ref "C76")
      (value "3.3nF")
      (footprint "eagle-import:C0603")
      (libsource (lib "eagle-import") (part "C-EUC0603"))
    )
    (comp (ref "C77")
      (value "3.3nF")
      (footprint "eagle-import:C0603")
      (libsource (lib "eagle-import") (part "C-EUC0603"))
    )
    (comp (ref "C78")
      (value "3.3nF")
      (footprint "eagle-import:C0603")
      (libsource (lib "eagle-import") (part "C-EUC0603"))
    )
    (comp (ref "C79")
      (value "3.3nF")
      (footprint "eagle-import:C0603")
      (libsource (lib "eagle-import") (part "C-EUC0603"))
    )
    (comp (ref "C80")
      (value "3.3nF")
      (footprint "eagle-import:C0603")
      (libsource (lib "eagle-import") (part "C-EUC0603"))
    )
    (comp (ref "C81")
      (value "3.3nF")
      (footprint "eagle-import:C0603")
      (libsource (lib "eagle-import") (part "C-EUC0603"))
    )
    (comp (ref "IC1")
      (value "OPA4340U")
      (footprint "eagle-import:SO14")
      (fields (field (name "MF") "TEXAS INSTRUMENTS") (field (name "MPN") "OPA4340UA"))
      (libsource (lib "eagle-import") (part "OPA4340U"))
    )
    (comp (ref "IC2")
      (value "OPA4340U")
      (footprint "eagle-import:SO14")
      (fields (field (name "MF") "TEXAS INSTRUMENTS") (field (name "MPN") "OPA4340UA"))
      (libsource (lib "eagle-import") (part "OPA4340U"))
    )
    (comp (ref "IC3")
      (value "OPA4340U")
      (footprint "eagle-import:SO14")
      (fields (field (name "MF") "TEXAS INSTRUMENTS") (field (name "MPN") "OPA4340UA"))
      (libsource (lib "eagle-import") (part "OPA4340U"))
    )
    (comp (ref "IC4")
      (value "OPA4340U")
      (footprint "eagle-import:SO14")
      (fields (field (name "MF") "TEXAS INSTRUMENTS") (field (name "MPN") "OPA4340UA"))
      (libsource (lib "eagle-import") (part "OPA4340U"))
    )
    (comp (ref "R1")
      (value "33k")
      (footprint "eagle-import:R0603")
      (libsource (lib "eagle-import") (part "R-EU_R0603"))
    )
    (comp (ref "R2")
      (value "33k")
      (footprint "eagle-import:R0603")
      (libsource (lib "eagle-import") (part "R-EU_R0603"))
    )
    (comp (ref "R3")
      (value "10k")
      (footprint "eagle-import:R0603")
      (libsource (lib "eagle-import") (part "R-EU_R0603"))
    )
    (comp (ref "R9")
      (value "10k")
      (footprint "eagle-import:R0603")
      (libsource (lib "eagle-import") (part "R-EU_R0603"))
    )
    (comp (ref "R86")
      (value "500")
      (footprint "eagle-import:R0603")
      (libsource (lib "eagle-import") (part "R-EU_R0603"))
    )
    (comp (ref "R87")
      (value "500")
      (footprint "eagle-import:R0603")
      (libsource (lib "eagle-import") (part "R-EU_R0603"))
    )
    (comp (ref "R88")
      (value "500")
      (footprint "eagle-import:R0603")
      (libsource (lib "eagle-import") (part "R-EU_R0603"))
    )
    (comp (ref "R89")
      (value "500")
      (footprint "eagle-import:R0603")
      (libsource (lib "eagle-import") (part "R-EU_R0603"))
    )
    (comp (ref "R92")
      (value "500")
      (footprint "eagle-import:R0603")
      (libsource (lib "eagle-import") (part "R-EU_R0603"))
    )
    (comp (ref "R93")
      (value "33k")
      (footprint "eagle-import:R0603")
      (libsource (lib "eagle-import") (part "R-EU_R0603"))
    )
    (comp (ref "R94")
      (value "10k")
      (footprint "eagle-import:R0603")
      (libsource (lib "eagle-import") (part "R-EU_R0603"))
    )
    (comp (ref "R95")
      (value "10k")
      (footprint "eagle-import:R0603")
      (libsource (lib "eagle-import") (part "R-EU_R0603"))
    )
    (comp (ref "R96")
      (value "33k")
      (footprint "eagle-import:R0603")
      (libsource (lib "eagle-import") (part "R-EU_R0603"))
    )
    (comp (ref "R97")
      (value "10k")
      (footprint "eagle-import:R0603")
      (libsource (lib "eagle-import") (part "R-EU_R0603"))
    )
    (comp (ref "R98")
      (value "33k")
      (footprint "eagle-import:R0603")
      (libsource (lib "eagle-import") (part "R-EU_R0603"))
    )
    (comp (ref "R99")
      (value "500")
      (footprint "eagle-import:R0603")
      (libsource (lib "eagle-import") (part "R-EU_R0603"))
    )
    (comp (ref "R100")
      (value "500")
      (footprint "eagle-import:R0603")
      (libsource (lib "eagle-import") (part "R-EU_R0603"))
    )
    (comp (ref "R101")
      (value "500")
      (footprint "eagle-import:R0603")
      (libsource (lib "eagle-import") (part "R-EU_R0603"))
    )
    (comp (ref "R102")
      (value "500")
      (footprint "eagle-import:R0603")
      (libsource (lib "eagle-import") (part "R-EU_R0603"))
    )
    (comp (ref "R103")
      (value "33k")
      (footprint "eagle-import:R0603")
      (libsource (lib "eagle-import") (part "R-EU_R0603"))
    )
    (comp (ref "R104")
      (value "10k")
      (footprint "eagle-import:R0603")
      (libsource (lib "eagle-import") (part "R-EU_R0603"))
    )
    (comp (ref "R105")
      (value "10k")
      (footprint "eagle-import:R0603")
      (libsource (lib "eagle-import") (part "R-EU_R0603"))
    )
    (comp (ref "R106")
      (value "33k")
      (footprint "eagle-import:R0603")
      (libsource (lib "eagle-import") (part "R-EU_R0603"))
    )
    (comp (ref "R107")
      (value "10k")
      (footprint "eagle-import:R0603")
      (libsource (lib "eagle-import") (part "R-EU_R0603"))
    )
    (comp (ref "R108")
      (value "33k")
      (footprint "eagle-import:R0603")
      (libsource (lib "eagle-import") (part "R-EU_R0603"))
    )
    (comp (ref "R109")
      (value "500")
      (footprint "eagle-import:R0603")
      (libsource (lib "eagle-import") (part "R-EU_R0603"))
    )
    (comp (ref "R110")
      (value "500")
      (footprint "eagle-import:R0603")
      (libsource (lib "eagle-import") (part "R-EU_R0603"))
    )
    (comp (ref "R111")
      (value "500")
      (footprint "eagle-import:R0603")
      (libsource (lib "eagle-import") (part "R-EU_R0603"))
    )
    (comp (ref "R112")
      (value "500")
      (footprint "eagle-import:R0603")
      (libsource (lib "eagle-import") (part "R-EU_R0603"))
    )
    (comp (ref "R113")
      (value "33k")
      (footprint "eagle-import:R0603")
      (libsource (lib "eagle-import") (part "R-EU_R0603"))
    )
    (comp (ref "R114")
      (value "10k")
      (footprint "eagle-import:R0603")
      (libsource (lib "eagle-import") (part "R-EU_R0603"))
    )
    (comp (ref "R115")
      (value "10k")
      (footprint "eagle-import:R0603")
      (libsource (lib "eagle-import") (part "R-EU_R0603"))
    )
    (comp (ref "R116")
      (value "33k")
      (footprint "eagle-import:R0603")
      (libsource (lib "eagle-import") (part "R-EU_R0603"))
    )
    (comp (ref "R117")
      (value "10k")
      (footprint "eagle-import:R0603")
      (libsource (lib "eagle-import") (part "R-EU_R0603"))
    )
    (comp (ref "R118")
      (value "33k")
      (footprint "eagle-import:R0603")
      (libsource (lib "eagle-import") (part "R-EU_R0603"))
    )
    (comp (ref "R119")
      (value "500")
      (footprint "eagle-import:R0603")
      (libsource (lib "eagle-import") (part "R-EU_R0603"))
    )
    (comp (ref "R120")
      (value "500")
      (footprint "eagle-import:R0603")
      (libsource (lib "eagle-import") (part "R-EU_R0603"))
    )
    (comp (ref "R121")
      (value "500")
      (footprint "eagle-import:R0603")
      (libsource (lib "eagle-import") (part "R-EU_R0603"))
    )
    (comp (ref "REF1")
      (value "REF3030")
      (footprint "eagle-import:SOT23")
      (fields (field (name "MF") "MAXIM") (field (name "MPN") "MAX6520EUR-T"))
      (libsource (lib "eagle-import") (part "MAX6520"))
    )
    (comp (ref "REF2")
      (value "REF3030")
      (footprint "eagle-import:SOT23")
      (fields (field (name "MF") "MAXIM") (field (name "MPN") "MAX6520EUR-T"))
      (libsource (lib "eagle-import") (part "MAX6520"))
    )
    (comp (ref "JA1")
      (value "MC15-G-3-3.81_2")
      (footprint "eagle-import:CON_3.81_2")
      (libsource (lib "eagle-import") (part "MC15-G-3-3.81_2"))
    )
    (comp (ref "JA2")
      (value "MC15-G-3-3.81_2")
      (footprint "eagle-import:CON_3.81_2")
      (libsource (lib "eagle-import") (part "MC15-G-3-3.81_2"))
    )
    (comp (ref "JA3")
      (value "MC15-G-3-3.81_2")
      (footprint "eagle-import:CON_3.81_2")
      (libsource (lib "eagle-import") (part "MC15-G-3-3.81_2"))
    )
    (comp (ref "JB1")
      (value "MC15-G-3-3.81_2")
      (footprint "eagle-import:CON_3.81_2")
      (libsource (lib "eagle-import") (part "MC15-G-3-3.81_2"))
    )
    (comp (ref "JB2")
      (value "MC15-G-3-3.81_2")
      (footprint "eagle-import:CON_3.81_2")
      (libsource (lib "eagle-import") (part "MC15-G-3-3.81_2"))
    )
    (comp (ref "JB3")
      (value "MC15-G-3-3.81_2")
      (footprint "eagle-import:CON_3.81_2")
      (libsource (lib "eagle-import") (part "MC15-G-3-3.81_2"))
    )
    (comp (ref "JB4")
      (value "MC15-G-3-3.81_2")
      (footprint "eagle-import:CON_3.81_2")
      (libsource (lib "eagle-import") (part "MC15-G-3-3.81_2"))
    )
    (comp (ref "JB5")
      (value "MC15-G-3-3.81_2")
      (footprint "eagle-import:CON_3.81_2")
      (libsource (lib "eagle-import") (part "MC15-G-3-3.81_2"))
    )
    (comp (ref "JB6")
      (value "MC15-G-3-3.81_2")
      (footprint "eagle-import:CON_3.81_2")
      (libsource (lib "eagle-import") (part "MC15-G-3-3.81_2"))
    )
    (comp (ref "JB7")
      (value "MC15-G-3-3.81_2")
      (footprint "eagle-import:CON_3.81_2")
      (libsource (lib "eagle-import") (part "MC15-G-3-3.81_2"))
    )
    (comp (ref "JB8")
      (value "MC15-G-3-3.81_2")
      (footprint "eagle-import:CON_3.81_2")
      (libsource (lib "eagle-import") (part "MC15-G-3-3.81_2"))
    )
    (comp (ref "MOTA1")
      (value "MODULE_DRV8842REV")
      (footprint "eagle-import:MODULE_DRV884X_REV")
      (libsource (lib "eagle-import") (part "MODULE_DRV8842REV"))
    )
    (comp (ref "MOTA2")
      (value "MODULE_DRV8842REV")
      (footprint "eagle-import:MODULE_DRV884X_REV")
      (libsource (lib "eagle-import") (part "MODULE_DRV8842REV"))
    )
    (comp (ref "MOTA3")
      (value "MODULE_DRV8842REV")
      (footprint "eagle-import:MODULE_DRV884X_REV")
      (libsource (lib "eagle-import") (part "MODULE_DRV8842REV"))
    )
    (comp (ref "MOTB1-2")
      (value "MODULE_DRV8843REV")
      (footprint "eagle-import:MODULE_DRV884X_REV")
      (libsource (lib "eagle-import") (part "MODULE_DRV8843REV"))
    )
    (comp (ref "MOTB3-4")
      (value "MODULE_DRV8843REV")
      (footprint "eagle-import:MODULE_DRV884X_REV")
      (libsource (lib "eagle-import") (part "MODULE_DRV8843REV"))
    )
    (comp (ref "MOTB5-6")
      (value "MODULE_DRV8843REV")
      (footprint "eagle-import:MODULE_DRV884X_REV")
      (libsource (lib "eagle-import") (part "MODULE_DRV8843REV"))
    )
    (comp (ref "MOTB7-8")
      (value "MODULE_DRV8843REV")
      (footprint "eagle-import:MODULE_DRV884X_REV")
      (libsource (lib "eagle-import") (part "MODULE_DRV8843REV"))
    )
    (comp (ref "P7")
      (value "47k")
      (footprint "eagle-import:RTRIMT93XB")
      (libsource (lib "eagle-import") (part "R-TRIMMT93XB"))
    )
    (comp (ref "P8")
      (value "47k")
      (footprint "eagle-import:RTRIMT93XB")
      (libsource (lib "eagle-import") (part "R-TRIMMT93XB"))
    )
    (comp (ref "P9")
      (value "47k")
      (footprint "eagle-import:RTRIMT93XB")
      (libsource (lib "eagle-import") (part "R-TRIMMT93XB"))
    )
    (comp (ref "P10")
      (value "47k")
      (footprint "eagle-import:RTRIMT93XB")
      (libsource (lib "eagle-import") (part "R-TRIMMT93XB"))
    )
    (comp (ref "P11")
      (value "47k")
      (footprint "eagle-import:RTRIMT93XB")
      (libsource (lib "eagle-import") (part "R-TRIMMT93XB"))
    )
    (comp (ref "R74")
      (value "33k")
      (footprint "eagle-import:R0603")
      (libsource (lib "eagle-import") (part "resistor_R-EU_R0603"))
    )
    (comp (ref "R75")
      (value "22k")
      (footprint "eagle-import:R0603")
      (libsource (lib "eagle-import") (part "resistor_R-EU_R0603"))
    )
    (comp (ref "R76")
      (value "33k")
      (footprint "eagle-import:R0603")
      (libsource (lib "eagle-import") (part "resistor_R-EU_R0603"))
    )
    (comp (ref "R77")
      (value "22k")
      (footprint "eagle-import:R0603")
      (libsource (lib "eagle-import") (part "resistor_R-EU_R0603"))
    )
    (comp (ref "R80")
      (value "33k")
      (footprint "eagle-import:R0603")
      (libsource (lib "eagle-import") (part "resistor_R-EU_R0603"))
    )
    (comp (ref "R81")
      (value "22k")
      (footprint "eagle-import:R0603")
      (libsource (lib "eagle-import") (part "resistor_R-EU_R0603"))
    )
    (comp (ref "R82")
      (value "33k")
      (footprint "eagle-import:R0603")
      (libsource (lib "eagle-import") (part "resistor_R-EU_R0603"))
    )
    (comp (ref "R83")
      (value "22k")
      (footprint "eagle-import:R0603")
      (libsource (lib "eagle-import") (part "resistor_R-EU_R0603"))
    )
    (comp (ref "R84")
      (value "33k")
      (footprint "eagle-import:R0603")
      (libsource (lib "eagle-import") (part "resistor_R-EU_R0603"))
    )
    (comp (ref "R85")
      (value "22k")
      (footprint "eagle-import:R0603")
      (libsource (lib "eagle-import") (part "resistor_R-EU_R0603"))
    )
    (comp (ref "C12")
      (value "10nF")
      (footprint "eagle-import:C0603")
      (libsource (lib "eagle-import") (part "C-EUC0603"))
    )
    (comp (ref "C13")
      (value "1uF")
      (footprint "eagle-import:C1210")
      (libsource (lib "eagle-import") (part "C-EUC1210"))
    )
    (comp (ref "C34")
      (value "10nF")
      (footprint "eagle-import:C0603")
      (libsource (lib "eagle-import") (part "C-EUC0603"))
    )
    (comp (ref "C35")
      (value "1uF")
      (footprint "eagle-import:C1210")
      (libsource (lib "eagle-import") (part "C-EUC1210"))
    )
    (comp (ref "C36")
      (value "10nF")
      (footprint "eagle-import:C0603")
      (libsource (lib "eagle-import") (part "C-EUC0603"))
    )
    (comp (ref "C37")
      (value "1uF")
      (footprint "eagle-import:C1210")
      (libsource (lib "eagle-import") (part "C-EUC1210"))
    )
    (comp (ref "C38")
      (value "10nF")
      (footprint "eagle-import:C0603")
      (libsource (lib "eagle-import") (part "C-EUC0603"))
    )
    (comp (ref "C39")
      (value "1uF")
      (footprint "eagle-import:C1210")
      (libsource (lib "eagle-import") (part "C-EUC1210"))
    )
    (comp (ref "C42")
      (value "10nF")
      (footprint "eagle-import:C0603")
      (libsource (lib "eagle-import") (part "C-EUC0603"))
    )
    (comp (ref "C43")
      (value "1uF")
      (footprint "eagle-import:C1210")
      (libsource (lib "eagle-import") (part "C-EUC1210"))
    )
    (comp (ref "C44")
      (value "10nF")
      (footprint "eagle-import:C0603")
      (libsource (lib "eagle-import") (part "C-EUC0603"))
    )
    (comp (ref "C45")
      (value "1uF")
      (footprint "eagle-import:C1210")
      (libsource (lib "eagle-import") (part "C-EUC1210"))
    )
    (comp (ref "D1")
      (value "MBRS340T3")
      (footprint "eagle-import:SMC")
      (libsource (lib "eagle-import") (part "MBRS30T34"))
    )
    (comp (ref "D2")
      (value "MBRS340T3")
      (footprint "eagle-import:SMC")
      (libsource (lib "eagle-import") (part "MBRS30T34"))
    )
    (comp (ref "D3")
      (value "MBRS340T3")
      (footprint "eagle-import:SMC")
      (libsource (lib "eagle-import") (part "MBRS30T34"))
    )
    (comp (ref "D4")
      (value "MBRS340T3")
      (footprint "eagle-import:SMC")
      (libsource (lib "eagle-import") (part "MBRS30T34"))
    )
    (comp (ref "D5")
      (value "MBRS340T3")
      (footprint "eagle-import:SMC")
      (libsource (lib "eagle-import") (part "MBRS30T34"))
    )
    (comp (ref "D6")
      (value "MBRS340T3")
      (footprint "eagle-import:SMC")
      (libsource (lib "eagle-import") (part "MBRS30T34"))
    )
    (comp (ref "JS1")
      (value "CON_2.54_H_2")
      (footprint "eagle-import:CON_2.54_H_2")
      (libsource (lib "eagle-import") (part "CON_2.54_H_2"))
    )
    (comp (ref "JS2")
      (value "CON_2.54_H_2")
      (footprint "eagle-import:CON_2.54_H_2")
      (libsource (lib "eagle-import") (part "CON_2.54_H_2"))
    )
    (comp (ref "JS3")
      (value "CON_2.54_H_2")
      (footprint "eagle-import:CON_2.54_H_2")
      (libsource (lib "eagle-import") (part "CON_2.54_H_2"))
    )
    (comp (ref "JS4")
      (value "CON_2.54_H_2")
      (footprint "eagle-import:CON_2.54_H_2")
      (libsource (lib "eagle-import") (part "CON_2.54_H_2"))
    )
    (comp (ref "JS5")
      (value "CON_2.54_H_2")
      (footprint "eagle-import:CON_2.54_H_2")
      (libsource (lib "eagle-import") (part "CON_2.54_H_2"))
    )
    (comp (ref "JS6")
      (value "CON_2.54_H_2")
      (footprint "eagle-import:CON_2.54_H_2")
      (libsource (lib "eagle-import") (part "CON_2.54_H_2"))
    )
    (comp (ref "LED1")
      (value "LEDCHIPLED_0805")
      (footprint "eagle-import:CHIPLED_0805")
      (libsource (lib "eagle-import") (part "LEDCHIPLED_0805"))
    )
    (comp (ref "LED2")
      (value "LEDCHIPLED_0805")
      (footprint "eagle-import:CHIPLED_0805")
      (libsource (lib "eagle-import") (part "LEDCHIPLED_0805"))
    )
    (comp (ref "LED3")
      (value "LEDCHIPLED_0805")
      (footprint "eagle-import:CHIPLED_0805")
      (libsource (lib "eagle-import") (part "LEDCHIPLED_0805"))
    )
    (comp (ref "LED4")
      (value "LEDCHIPLED_0805")
      (footprint "eagle-import:CHIPLED_0805")
      (libsource (lib "eagle-import") (part "LEDCHIPLED_0805"))
    )
    (comp (ref "LED5")
      (value "LEDCHIPLED_0805")
      (footprint "eagle-import:CHIPLED_0805")
      (libsource (lib "eagle-import") (part "LEDCHIPLED_0805"))
    )
    (comp (ref "LED6")
      (value "LEDCHIPLED_0805")
      (footprint "eagle-import:CHIPLED_0805")
      (libsource (lib "eagle-import") (part "LEDCHIPLED_0805"))
    )
    (comp (ref "P1")
      (value "33k")
      (footprint "eagle-import:RTRIMT93XB")
      (libsource (lib "eagle-import") (part "R-TRIMMT93XB"))
    )
    (comp (ref "P2")
      (value "33k")
      (footprint "eagle-import:RTRIMT93XB")
      (libsource (lib "eagle-import") (part "R-TRIMMT93XB"))
    )
    (comp (ref "P3")
      (value "33k")
      (footprint "eagle-import:RTRIMT93XB")
      (libsource (lib "eagle-import") (part "R-TRIMMT93XB"))
    )
    (comp (ref "P4")
      (value "33k")
      (footprint "eagle-import:RTRIMT93XB")
      (libsource (lib "eagle-import") (part "R-TRIMMT93XB"))
    )
    (comp (ref "P5")
      (value "33k")
      (footprint "eagle-import:RTRIMT93XB")
      (libsource (lib "eagle-import") (part "R-TRIMMT93XB"))
    )
    (comp (ref "P6")
      (value "33k")
      (footprint "eagle-import:RTRIMT93XB")
      (libsource (lib "eagle-import") (part "R-TRIMMT93XB"))
    )
    (comp (ref "R35")
      (value "100k")
      (footprint "eagle-import:R0603")
      (libsource (lib "eagle-import") (part "resistor_R-EU_R0603"))
    )
    (comp (ref "R36")
      (value "16.9k")
      (footprint "eagle-import:R0603")
      (libsource (lib "eagle-import") (part "resistor_R-EU_R0603"))
    )
    (comp (ref "R37")
      (value "5k")
      (footprint "eagle-import:R0603")
      (libsource (lib "eagle-import") (part "resistor_R-EU_R0603"))
    )
    (comp (ref "R43")
      (value "100k")
      (footprint "eagle-import:R0603")
      (libsource (lib "eagle-import") (part "resistor_R-EU_R0603"))
    )
    (comp (ref "R44")
      (value "16.9k")
      (footprint "eagle-import:R0603")
      (libsource (lib "eagle-import") (part "resistor_R-EU_R0603"))
    )
    (comp (ref "R45")
      (value "5k")
      (footprint "eagle-import:R0603")
      (libsource (lib "eagle-import") (part "resistor_R-EU_R0603"))
    )
    (comp (ref "R46")
      (value "100k")
      (footprint "eagle-import:R0603")
      (libsource (lib "eagle-import") (part "resistor_R-EU_R0603"))
    )
    (comp (ref "R47")
      (value "16.9k")
      (footprint "eagle-import:R0603")
      (libsource (lib "eagle-import") (part "resistor_R-EU_R0603"))
    )
    (comp (ref "R48")
      (value "5k")
      (footprint "eagle-import:R0603")
      (libsource (lib "eagle-import") (part "resistor_R-EU_R0603"))
    )
    (comp (ref "R49")
      (value "100k")
      (footprint "eagle-import:R0603")
      (libsource (lib "eagle-import") (part "resistor_R-EU_R0603"))
    )
    (comp (ref "R50")
      (value "16.9k")
      (footprint "eagle-import:R0603")
      (libsource (lib "eagle-import") (part "resistor_R-EU_R0603"))
    )
    (comp (ref "R51")
      (value "5k")
      (footprint "eagle-import:R0603")
      (libsource (lib "eagle-import") (part "resistor_R-EU_R0603"))
    )
    (comp (ref "R52")
      (value "100k")
      (footprint "eagle-import:R0603")
      (libsource (lib "eagle-import") (part "resistor_R-EU_R0603"))
    )
    (comp (ref "R53")
      (value "16.9k")
      (footprint "eagle-import:R0603")
      (libsource (lib "eagle-import") (part "resistor_R-EU_R0603"))
    )
    (comp (ref "R54")
      (value "5k")
      (footprint "eagle-import:R0603")
      (libsource (lib "eagle-import") (part "resistor_R-EU_R0603"))
    )
    (comp (ref "R55")
      (value "100k")
      (footprint "eagle-import:R0603")
      (libsource (lib "eagle-import") (part "resistor_R-EU_R0603"))
    )
    (comp (ref "R56")
      (value "16.9k")
      (footprint "eagle-import:R0603")
      (libsource (lib "eagle-import") (part "resistor_R-EU_R0603"))
    )
    (comp (ref "R57")
      (value "5k")
      (footprint "eagle-import:R0603")
      (libsource (lib "eagle-import") (part "resistor_R-EU_R0603"))
    )
    (comp (ref "SOL1")
      (value "DRV103")
      (footprint "eagle-import:PWP_8")
      (libsource (lib "eagle-import") (part "DRV103"))
    )
    (comp (ref "SOL2")
      (value "DRV103")
      (footprint "eagle-import:PWP_8")
      (libsource (lib "eagle-import") (part "DRV103"))
    )
    (comp (ref "SOL3")
      (value "DRV103")
      (footprint "eagle-import:PWP_8")
      (libsource (lib "eagle-import") (part "DRV103"))
    )
    (comp (ref "SOL4")
      (value "DRV103")
      (footprint "eagle-import:PWP_8")
      (libsource (lib "eagle-import") (part "DRV103"))
    )
    (comp (ref "SOL5")
      (value "DRV103")
      (footprint "eagle-import:PWP_8")
      (libsource (lib "eagle-import") (part "DRV103"))
    )
    (comp (ref "SOL6")
      (value "DRV103")
      (footprint "eagle-import:PWP_8")
      (libsource (lib "eagle-import") (part "DRV103"))
    )
    (comp (ref "C5")
      (value "1nF")
      (footprint "eagle-import:C0603")
      (libsource (lib "eagle-import") (part "C-EUC0603"))
    )
    (comp (ref "C6")
      (value "1nF")
      (footprint "eagle-import:C0603")
      (libsource (lib "eagle-import") (part "C-EUC0603"))
    )
    (comp (ref "C7")
      (value "10uF")
      (footprint "eagle-import:C1210")
      (libsource (lib "eagle-import") (part "C-EUC1210"))
    )
    (comp (ref "C8")
      (value "1nF")
      (footprint "eagle-import:C0603")
      (libsource (lib "eagle-import") (part "C-EUC0603"))
    )
    (comp (ref "C9")
      (value "10uF")
      (footprint "eagle-import:C1210")
      (libsource (lib "eagle-import") (part "C-EUC1210"))
    )
    (comp (ref "C10")
      (value "1nF")
      (footprint "eagle-import:C0603")
      (libsource (lib "eagle-import") (part "C-EUC0603"))
    )
    (comp (ref "C11")
      (value "10uF")
      (footprint "eagle-import:C1210")
      (libsource (lib "eagle-import") (part "C-EUC1210"))
    )
    (comp (ref "C27")
      (value "10uF")
      (footprint "eagle-import:C1210")
      (libsource (lib "eagle-import") (part "C-EUC1210"))
    )
    (comp (ref "C28")
      (value "1nF")
      (footprint "eagle-import:C0603")
      (libsource (lib "eagle-import") (part "C-EUC0603"))
    )
    (comp (ref "C29")
      (value "10uF")
      (footprint "eagle-import:C1210")
      (libsource (lib "eagle-import") (part "C-EUC1210"))
    )
    (comp (ref "C30")
      (value "1nF")
      (footprint "eagle-import:C0603")
      (libsource (lib "eagle-import") (part "C-EUC0603"))
    )
    (comp (ref "C31")
      (value "10uF")
      (footprint "eagle-import:C1210")
      (libsource (lib "eagle-import") (part "C-EUC1210"))
    )
    (comp (ref "C32")
      (value "1nF")
      (footprint "eagle-import:C0603")
      (libsource (lib "eagle-import") (part "C-EUC0603"))
    )
    (comp (ref "C33")
      (value "10uF")
      (footprint "eagle-import:C1210")
      (libsource (lib "eagle-import") (part "C-EUC1210"))
    )
    (comp (ref "C40")
      (value "1nF")
      (footprint "eagle-import:C0603")
      (libsource (lib "eagle-import") (part "C-EUC0603"))
    )
    (comp (ref "C41")
      (value "10uF")
      (footprint "eagle-import:C1210")
      (libsource (lib "eagle-import") (part "C-EUC1210"))
    )
    (comp (ref "JM1")
      (value "CON_2.54_H_2")
      (footprint "eagle-import:CON_2.54_H_2")
      (libsource (lib "eagle-import") (part "CON_2.54_H_2"))
    )
    (comp (ref "JM2")
      (value "CON_2.54_H_2")
      (footprint "eagle-import:CON_2.54_H_2")
      (libsource (lib "eagle-import") (part "CON_2.54_H_2"))
    )
    (comp (ref "JM3")
      (value "CON_2.54_H_2")
      (footprint "eagle-import:CON_2.54_H_2")
      (libsource (lib "eagle-import") (part "CON_2.54_H_2"))
    )
    (comp (ref "JM4")
      (value "CON_2.54_H_2")
      (footprint "eagle-import:CON_2.54_H_2")
      (libsource (lib "eagle-import") (part "CON_2.54_H_2"))
    )
    (comp (ref "JM5")
      (value "CON_2.54_H_2")
      (footprint "eagle-import:CON_2.54_H_2")
      (libsource (lib "eagle-import") (part "CON_2.54_H_2"))
    )
    (comp (ref "JM6")
      (value "CON_2.54_H_2")
      (footprint "eagle-import:CON_2.54_H_2")
      (libsource (lib "eagle-import") (part "CON_2.54_H_2"))
    )
    (comp (ref "JM7")
      (value "CON_2.54_H_2")
      (footprint "eagle-import:CON_2.54_H_2")
      (libsource (lib "eagle-import") (part "CON_2.54_H_2"))
    )
    (comp (ref "JM8")
      (value "CON_2.54_H_2")
      (footprint "eagle-import:CON_2.54_H_2")
      (libsource (lib "eagle-import") (part "CON_2.54_H_2"))
    )
    (comp (ref "MOS1")
      (value "FDC6330L")
      (footprint "eagle-import:SSOT-6")
      (libsource (lib "eagle-import") (part "FDC6330L"))
    )
    (comp (ref "MOS2")
      (value "FDC6330L")
      (footprint "eagle-import:SSOT-6")
      (libsource (lib "eagle-import") (part "FDC6330L"))
    )
    (comp (ref "MOS3")
      (value "FDC6330L")
      (footprint "eagle-import:SSOT-6")
      (libsource (lib "eagle-import") (part "FDC6330L"))
    )
    (comp (ref "MOS4")
      (value "FDC6330L")
      (footprint "eagle-import:SSOT-6")
      (libsource (lib "eagle-import") (part "FDC6330L"))
    )
    (comp (ref "MOS5")
      (value "FDC6330L")
      (footprint "eagle-import:SSOT-6")
      (libsource (lib "eagle-import") (part "FDC6330L"))
    )
    (comp (ref "MOS6")
      (value "FDC6330L")
      (footprint "eagle-import:SSOT-6")
      (libsource (lib "eagle-import") (part "FDC6330L"))
    )
    (comp (ref "MOS7")
      (value "FDC6330L")
      (footprint "eagle-import:SSOT-6")
      (libsource (lib "eagle-import") (part "FDC6330L"))
    )
    (comp (ref "MOS8")
      (value "FDC6330L")
      (footprint "eagle-import:SSOT-6")
      (libsource (lib "eagle-import") (part "FDC6330L"))
    )
    (comp (ref "R10")
      (value "47k")
      (footprint "eagle-import:R0603")
      (libsource (lib "eagle-import") (part "resistor_R-EU_R0603"))
    )
    (comp (ref "R25")
      (value "47k")
      (footprint "eagle-import:R0603")
      (libsource (lib "eagle-import") (part "resistor_R-EU_R0603"))
    )
    (comp (ref "R26")
      (value "1k")
      (footprint "eagle-import:R0603")
      (libsource (lib "eagle-import") (part "resistor_R-EU_R0603"))
    )
    (comp (ref "R27")
      (value "1k")
      (footprint "eagle-import:R0603")
      (libsource (lib "eagle-import") (part "resistor_R-EU_R0603"))
    )
    (comp (ref "R28")
      (value "47k")
      (footprint "eagle-import:R0603")
      (libsource (lib "eagle-import") (part "resistor_R-EU_R0603"))
    )
    (comp (ref "R29")
      (value "47k")
      (footprint "eagle-import:R0603")
      (libsource (lib "eagle-import") (part "resistor_R-EU_R0603"))
    )
    (comp (ref "R30")
      (value "1k")
      (footprint "eagle-import:R0603")
      (libsource (lib "eagle-import") (part "resistor_R-EU_R0603"))
    )
    (comp (ref "R31")
      (value "47k")
      (footprint "eagle-import:R0603")
      (libsource (lib "eagle-import") (part "resistor_R-EU_R0603"))
    )
    (comp (ref "R32")
      (value "1k")
      (footprint "eagle-import:R0603")
      (libsource (lib "eagle-import") (part "resistor_R-EU_R0603"))
    )
    (comp (ref "R33")
      (value "47k")
      (footprint "eagle-import:R0603")
      (libsource (lib "eagle-import") (part "resistor_R-EU_R0603"))
    )
    (comp (ref "R34")
      (value "1k")
      (footprint "eagle-import:R0603")
      (libsource (lib "eagle-import") (part "resistor_R-EU_R0603"))
    )
    (comp (ref "R38")
      (value "1k")
      (footprint "eagle-import:R0603")
      (libsource (lib "eagle-import") (part "resistor_R-EU_R0603"))
    )
    (comp (ref "R39")
      (value "47k")
      (footprint "eagle-import:R0603")
      (libsource (lib "eagle-import") (part "resistor_R-EU_R0603"))
    )
    (comp (ref "R40")
      (value "1k")
      (footprint "eagle-import:R0603")
      (libsource (lib "eagle-import") (part "resistor_R-EU_R0603"))
    )
    (comp (ref "R41")
      (value "47k")
      (footprint "eagle-import:R0603")
      (libsource (lib "eagle-import") (part "resistor_R-EU_R0603"))
    )
    (comp (ref "R42")
      (value "1k")
      (footprint "eagle-import:R0603")
      (libsource (lib "eagle-import") (part "resistor_R-EU_R0603"))
    )
    (comp (ref "IOE1")
      (value "MCP23S17SO")
      (footprint "eagle-import:SO28W")
      (fields (field (name "MF") "MICROCHIP") (field (name "MPN") "MCP23S17-E/SO"))
      (libsource (lib "eagle-import") (part "MCP23S17SO"))
    )
    (comp (ref "IOE2")
      (value "MCP23S17SO")
      (footprint "eagle-import:SO28W")
      (fields (field (name "MF") "MICROCHIP") (field (name "MPN") "MCP23S17-E/SO"))
      (libsource (lib "eagle-import") (part "MCP23S17SO"))
    )
    (comp (ref "IOE3")
      (value "MCP23S17SO")
      (footprint "eagle-import:SO28W")
      (fields (field (name "MF") "MICROCHIP") (field (name "MPN") "MCP23S17-E/SO"))
      (libsource (lib "eagle-import") (part "MCP23S17SO"))
    )
    (comp (ref "JCTRL")
      (value "FFC-0.5_50")
      (footprint "eagle-import:FFC-SMD-0.5_50")
      (libsource (lib "eagle-import") (part "FFC-0.5_50"))
    )
    (comp (ref "JVL")
      (value "HE14_H_6")
      (footprint "eagle-import:HE14_H_6")
      (libsource (lib "eagle-import") (part "HE14_H_6"))
    )
    (comp (ref "C1")
      (value "22uF")
      (footprint "eagle-import:C3225")
      (libsource (lib "eagle-import") (part "C-EUC3225"))
    )
    (comp (ref "C2")
      (value "47uF")
      (footprint "eagle-import:C1210")
      (libsource (lib "eagle-import") (part "C-EUC1210"))
    )
    (comp (ref "C3")
      (value "47uF")
      (footprint "eagle-import:C1210")
      (libsource (lib "eagle-import") (part "C-EUC1210"))
    )
    (comp (ref "C4")
      (value "47uF")
      (footprint "eagle-import:C1210")
      (libsource (lib "eagle-import") (part "C-EUC1210"))
    )
    (comp (ref "C14")
      (value "22uF")
      (footprint "eagle-import:C3225")
      (libsource (lib "eagle-import") (part "C-EUC3225"))
    )
    (comp (ref "C15")
      (value "22uF")
      (footprint "eagle-import:C3225")
      (libsource (lib "eagle-import") (part "C-EUC3225"))
    )
    (comp (ref "C16")
      (value "22uF")
      (footprint "eagle-import:C3225")
      (libsource (lib "eagle-import") (part "C-EUC3225"))
    )
    (comp (ref "C17")
      (value "22uF")
      (footprint "eagle-import:C3225")
      (libsource (lib "eagle-import") (part "C-EUC3225"))
    )
    (comp (ref "C18")
      (value "470uF")
      (footprint "eagle-import:PANASONIC_B")
      (libsource (lib "eagle-import") (part "CPOL-EUB"))
    )
    (comp (ref "C19")
      (value "470uF")
      (footprint "eagle-import:PANASONIC_D")
      (libsource (lib "eagle-import") (part "CPOL-EUD"))
    )
    (comp (ref "C20")
      (value "1uF")
      (footprint "eagle-import:C3225")
      (libsource (lib "eagle-import") (part "C-EUC3225"))
    )
    (comp (ref "C21")
      (value "470uF")
      (footprint "eagle-import:PANASONIC_D")
      (libsource (lib "eagle-import") (part "CPOL-EUD"))
    )
    (comp (ref "C22")
      (value "1uF")
      (footprint "eagle-import:C3225")
      (libsource (lib "eagle-import") (part "C-EUC3225"))
    )
    (comp (ref "C23")
      (value "470uF")
      (footprint "eagle-import:PANASONIC_D")
      (libsource (lib "eagle-import") (part "CPOL-EUD"))
    )
    (comp (ref "C24")
      (value "1uF")
      (footprint "eagle-import:C3225")
      (libsource (lib "eagle-import") (part "C-EUC3225"))
    )
    (comp (ref "C25")
      (value "470uF")
      (footprint "eagle-import:PANASONIC_D")
      (libsource (lib "eagle-import") (part "CPOL-EUD"))
    )
    (comp (ref "C26")
      (value "1uF")
      (footprint "eagle-import:C3225")
      (libsource (lib "eagle-import") (part "C-EUC3225"))
    )
    (comp (ref "C58")
      (value "47uF")
      (footprint "eagle-import:C1210")
      (libsource (lib "eagle-import") (part "C-EUC1210"))
    )
    (comp (ref "JBAT1")
      (value "MC15-GF-3.81-LR_2")
      (footprint "eagle-import:CON_3.81_LR_2")
      (libsource (lib "eagle-import") (part "MC15-GF-3.81-LR_2"))
    )
    (comp (ref "JSW")
      (value "MC15-GF-3.81-LR_4")
      (footprint "eagle-import:CON_3.81_LR_4")
      (libsource (lib "eagle-import") (part "MC15-GF-3.81-LR_4"))
    )
    (comp (ref "L4")
      (value "DR1030")
      (footprint "eagle-import:DR1030")
      (libsource (lib "eagle-import") (part "DR1030"))
    )
    (comp (ref "L5")
      (value "DR1030")
      (footprint "eagle-import:DR1030")
      (libsource (lib "eagle-import") (part "DR1030"))
    )
    (comp (ref "L6")
      (value "DR1030")
      (footprint "eagle-import:DR1030")
      (libsource (lib "eagle-import") (part "DR1030"))
    )
    (comp (ref "L7")
      (value "DR1030")
      (footprint "eagle-import:DR1030")
      (libsource (lib "eagle-import") (part "DR1030"))
    )
    (comp (ref "Q1")
      (value "BSS138")
      (footprint "eagle-import:SOT23")
      (libsource (lib "eagle-import") (part "MOSFET-NCHANNELBSS138"))
    )
    (comp (ref "Q2")
      (value "BSS138")
      (footprint "eagle-import:SOT23")
      (libsource (lib "eagle-import") (part "MOSFET-NCHANNELBSS138"))
    )
    (comp (ref "Q3")
      (value "BSS138")
      (footprint "eagle-import:SOT23")
      (libsource (lib "eagle-import") (part "MOSFET-NCHANNELBSS138"))
    )
    (comp (ref "Q4")
      (value "BSS138")
      (footprint "eagle-import:SOT23")
      (libsource (lib "eagle-import") (part "MOSFET-NCHANNELBSS138"))
    )
    (comp (ref "R4")
      (value "21k")
      (footprint "eagle-import:R0603")
      (libsource (lib "eagle-import") (part "R-EU_R0603"))
    )
    (comp (ref "R5")
      (value "3.3k")
      (footprint "eagle-import:R0603")
      (libsource (lib "eagle-import") (part "R-EU_R0603"))
    )
    (comp (ref "R6")
      (value "383k")
      (footprint "eagle-import:R0603")
      (libsource (lib "eagle-import") (part "R-EU_R0603"))
    )
    (comp (ref "R7")
      (value "383k")
      (footprint "eagle-import:R0603")
      (libsource (lib "eagle-import") (part "R-EU_R0603"))
    )
    (comp (ref "R8")
      (value "R005")
      (footprint "eagle-import:R2512")
      (libsource (lib "eagle-import") (part "R-EU_R2512"))
    )
    (comp (ref "R11")
      (value "R005")
      (footprint "eagle-import:R2512")
      (libsource (lib "eagle-import") (part "R-EU_R2512"))
    )
    (comp (ref "R12")
      (value "500k")
      (footprint "eagle-import:R0603")
      (libsource (lib "eagle-import") (part "R-EU_R0603"))
    )
    (comp (ref "R13")
      (value "500k")
      (footprint "eagle-import:R0603")
      (libsource (lib "eagle-import") (part "R-EU_R0603"))
    )
    (comp (ref "R14")
      (value "R005")
      (footprint "eagle-import:R2512")
      (libsource (lib "eagle-import") (part "R-EU_R2512"))
    )
    (comp (ref "R15")
      (value "500k")
      (footprint "eagle-import:R0603")
      (libsource (lib "eagle-import") (part "R-EU_R0603"))
    )
    (comp (ref "R16")
      (value "R005")
      (footprint "eagle-import:R2512")
      (libsource (lib "eagle-import") (part "R-EU_R2512"))
    )
    (comp (ref "R17")
      (value "500k")
      (footprint "eagle-import:R0603")
      (libsource (lib "eagle-import") (part "R-EU_R0603"))
    )
    (comp (ref "R90")
      (value "R005")
      (footprint "eagle-import:R2512")
      (libsource (lib "eagle-import") (part "R-EU_R2512"))
    )
    (comp (ref "R91")
      (value "300k")
      (footprint "eagle-import:R0603")
      (libsource (lib "eagle-import") (part "R-EU_R0603"))
    )
    (comp (ref "SENSE_VBAT")
      (value "INA138")
      (footprint "eagle-import:DBV_05")
      (libsource (lib "eagle-import") (part "INA138"))
    )
    (comp (ref "SENSE_VP1")
      (value "INA138")
      (footprint "eagle-import:DBV_05")
      (libsource (lib "eagle-import") (part "INA138"))
    )
    (comp (ref "SENSE_VP2")
      (value "INA138")
      (footprint "eagle-import:DBV_05")
      (libsource (lib "eagle-import") (part "INA138"))
    )
    (comp (ref "SENSE_VP3")
      (value "INA138")
      (footprint "eagle-import:DBV_05")
      (libsource (lib "eagle-import") (part "INA138"))
    )
    (comp (ref "SENSE_VP4")
      (value "INA138")
      (footprint "eagle-import:DBV_05")
      (libsource (lib "eagle-import") (part "INA138"))
    )
    (comp (ref "VCC12")
      (value "TSR_1-2412")
      (footprint "eagle-import:TSR1")
      (libsource (lib "eagle-import") (part "TSR_1-24XX"))
    )
    (comp (ref "VCC33")
      (value "TSR_1-2433")
      (footprint "eagle-import:TSR1")
      (libsource (lib "eagle-import") (part "TSR_1-24XX"))
    )
    (comp (ref "VCC50")
      (value "TSR_1-2450")
      (footprint "eagle-import:TSR1")
      (libsource (lib "eagle-import") (part "TSR_1-24XX"))
    )
    (comp (ref "VCC120")
      (value "TSR_1-24120")
      (footprint "eagle-import:TSR1")
      (libsource (lib "eagle-import") (part "TSR_1-24XX"))
    )
    (comp (ref "VP1")
      (value "PTN78020W")
      (footprint "eagle-import:PTN78020")
      (libsource (lib "eagle-import") (part "PTN78020W"))
    )
    (comp (ref "VP2")
      (value "PTN78020W")
      (footprint "eagle-import:PTN78020")
      (libsource (lib "eagle-import") (part "PTN78020W"))
    )
    (comp (ref "VP3")
      (value "PTN78020H")
      (footprint "eagle-import:PTN78020")
      (libsource (lib "eagle-import") (part "PTN78020W"))
    )
    (comp (ref "VP4")
      (value "PTN78020H")
      (footprint "eagle-import:PTN78020")
      (libsource (lib "eagle-import") (part "PTN78020W"))
    )
  )
  (nets
    (net (code "1") (name "+1V2L") (class "Default")
      (node (ref "C4") (pin "1") (pinfunction "1_1") (pintype "passive"))
      (node (ref "JVL") (pin "4") (pinfunction "4_4") (pintype "bidirectional"))
      (node (ref "VCC12") (pin "3") (pinfunction "VO_3") (pintype "power_in"))
    )
    (net (code "2") (name "+3V3L") (class "Default")
      (node (ref "ADC1") (pin "20") (pinfunction "VCC_20") (pintype "power_in"))
      (node (ref "ADC2") (pin "20") (pinfunction "VCC_20") (pintype "power_in"))
      (node (ref "C3") (pin "1") (pinfunction "1_1") (pintype "passive"))
      (node (ref "C60") (pin "1") (pinfunction "1_1") (pintype "passive"))
      (node (ref "C70") (pin "1") (pinfunction "1_1") (pintype "passive"))
      (node (ref "C71") (pin "1") (pinfunction "1_1") (pintype "passive"))
      (node (ref "C72") (pin "1") (pinfunction "1_1") (pintype "passive"))
      (node (ref "C73") (pin "1") (pinfunction "1_1") (pintype "passive"))
      (node (ref "IC1") (pin "4") (pinfunction "V+_4") (pintype "power_in"))
      (node (ref "IC2") (pin "4") (pinfunction "V+_4") (pintype "power_in"))
      (node (ref "IC3") (pin "4") (pinfunction "V+_4") (pintype "power_in"))
      (node (ref "IC4") (pin "4") (pinfunction "V+_4") (pintype "power_in"))
      (node (ref "IOE1") (pin "15") (pinfunction "A0_15") (pintype "input"))
      (node (ref "IOE1") (pin "9") (pinfunction "VDD_9") (pintype "power_in"))
      (node (ref "IOE2") (pin "16") (pinfunction "A1_16") (pintype "input"))
      (node (ref "IOE2") (pin "9") (pinfunction "VDD_9") (pintype "power_in"))
      (node (ref "IOE3") (pin "15") (pinfunction "A0_15") (pintype "input"))
      (node (ref "IOE3") (pin "16") (pinfunction "A1_16") (pintype "input"))
      (node (ref "IOE3") (pin "9") (pinfunction "VDD_9") (pintype "power_in"))
      (node (ref "JVL") (pin "3") (pinfunction "3_3") (pintype "bidirectional"))
      (node (ref "R74") (pin "2") (pinfunction "2_2") (pintype "passive"))
      (node (ref "R76") (pin "2") (pinfunction "2_2") (pintype "passive"))
      (node (ref "R80") (pin "2") (pinfunction "2_2") (pintype "passive"))
      (node (ref "R82") (pin "2") (pinfunction "2_2") (pintype "passive"))
      (node (ref "R84") (pin "2") (pinfunction "2_2") (pintype "passive"))
      (node (ref "REF1") (pin "1") (pinfunction "IN_1") (pintype "input"))
      (node (ref "REF2") (pin "1") (pinfunction "IN_1") (pintype "input"))
      (node (ref "SENSE_VBAT") (pin "5") (pinfunction "V+_5") (pintype "bidirectional"))
      (node (ref "SENSE_VP1") (pin "5") (pinfunction "V+_5") (pintype "bidirectional"))
      (node (ref "SENSE_VP2") (pin "5") (pinfunction "V+_5") (pintype "bidirectional"))
      (node (ref "SENSE_VP3") (pin "5") (pinfunction "V+_5") (pintype "bidirectional"))
      (node (ref "SENSE_VP4") (pin "5") (pinfunction "V+_5") (pintype "bidirectional"))
      (node (ref "VCC33") (pin "3") (pinfunction "VO_3") (pintype "power_in"))
    )
    (net (code "3") (name "+5VL") (class "Default")
      (node (ref "C2") (pin "1") (pinfunction "1_1") (pintype "passive"))
      (node (ref "CEL1") (pin "7") (pinfunction "V+_7") (pintype "bidirectional"))
      (node (ref "CEL2") (pin "7") (pinfunction "V+_7") (pintype "bidirectional"))
      (node (ref "CEL3") (pin "7") (pinfunction "V+_7") (pintype "bidirectional"))
      (node (ref "CEL4") (pin "7") (pinfunction "V+_7") (pintype "bidirectional"))
      (node (ref "CEL5") (pin "7") (pinfunction "V+_7") (pintype "bidirectional"))
      (node (ref "CEL6") (pin "7") (pinfunction "V+_7") (pintype "bidirectional"))
      (node (ref "JVL") (pin "2") (pinfunction "2_2") (pintype "bidirectional"))
      (node (ref "VCC50") (pin "3") (pinfunction "VO_3") (pintype "power_in"))
    )
    (net (code "4") (name "+12VL") (class "Default")
      (node (ref "C58") (pin "1") (pinfunction "1_1") (pintype "passive"))
      (node (ref "JVL") (pin "1") (pinfunction "1_1") (pintype "bidirectional"))
      (node (ref "VCC120") (pin "3") (pinfunction "VO_3") (pintype "power_in"))
    )
    (net (code "5") (name "+VBATL") (class "Default")
      (node (ref "C1") (pin "1") (pinfunction "1_1") (pintype "passive"))
      (node (ref "JSW") (pin "2") (pinfunction "2_2") (pintype "bidirectional"))
      (node (ref "R90") (pin "2") (pinfunction "2_2") (pintype "passive"))
      (node (ref "SENSE_VBAT") (pin "4") (pinfunction "VIN-_4") (pintype "bidirectional"))
      (node (ref "VCC12") (pin "1") (pinfunction "VI_1") (pintype "power_in"))
      (node (ref "VCC120") (pin "1") (pinfunction "VI_1") (pintype "power_in"))
      (node (ref "VCC33") (pin "1") (pinfunction "VI_1") (pintype "power_in"))
      (node (ref "VCC50") (pin "1") (pinfunction "VI_1") (pintype "power_in"))
    )
    (net (code "6") (name "+VBATP") (class "Default")
      (node (ref "C14") (pin "1") (pinfunction "1_1") (pintype "passive"))
      (node (ref "C15") (pin "1") (pinfunction "1_1") (pintype "passive"))
      (node (ref "C16") (pin "1") (pinfunction "1_1") (pintype "passive"))
      (node (ref "C17") (pin "1") (pinfunction "1_1") (pintype "passive"))
      (node (ref "C18") (pin "+") (pinfunction "+_+") (pintype "passive"))
      (node (ref "JSW") (pin "1") (pinfunction "1_1") (pintype "bidirectional"))
      (node (ref "MOTA1") (pin "10") (pinfunction "VM_10") (pintype "bidirectional"))
      (node (ref "MOTA1") (pin "11") (pinfunction "VM_11") (pintype "bidirectional"))
      (node (ref "MOTA1") (pin "12") (pinfunction "VM_12") (pintype "bidirectional"))
      (node (ref "MOTA2") (pin "10") (pinfunction "VM_10") (pintype "bidirectional"))
      (node (ref "MOTA2") (pin "11") (pinfunction "VM_11") (pintype "bidirectional"))
      (node (ref "MOTA2") (pin "12") (pinfunction "VM_12") (pintype "bidirectional"))
      (node (ref "MOTA3") (pin "10") (pinfunction "VM_10") (pintype "bidirectional"))
      (node (ref "MOTA3") (pin "11") (pinfunction "VM_11") (pintype "bidirectional"))
      (node (ref "MOTA3") (pin "12") (pinfunction "VM_12") (pintype "bidirectional"))
      (node (ref "VP1") (pin "2") (pinfunction "VI_2") (pintype "power_in"))
      (node (ref "VP2") (pin "2") (pinfunction "VI_2") (pintype "power_in"))
      (node (ref "VP3") (pin "2") (pinfunction "VI_2") (pintype "power_in"))
      (node (ref "VP4") (pin "2") (pinfunction "VI_2") (pintype "power_in"))
    )
    (net (code "7") (name "+VP1") (class "Default")
      (node (ref "JAS1") (pin "1") (pinfunction "1_1") (pintype "bidirectional"))
      (node (ref "JAS2") (pin "1") (pinfunction "1_1") (pintype "bidirectional"))
      (node (ref "JAS3") (pin "1") (pinfunction "1_1") (pintype "bidirectional"))
      (node (ref "JAS4") (pin "1") (pinfunction "1_1") (pintype "bidirectional"))
      (node (ref "JAS5") (pin "1") (pinfunction "1_1") (pintype "bidirectional"))
      (node (ref "JAS6") (pin "1") (pinfunction "1_1") (pintype "bidirectional"))
      (node (ref "JAS7") (pin "1") (pinfunction "1_1") (pintype "bidirectional"))
      (node (ref "JAS8") (pin "1") (pinfunction "1_1") (pintype "bidirectional"))
      (node (ref "R8") (pin "2") (pinfunction "2_2") (pintype "passive"))
      (node (ref "RS10") (pin "2") (pinfunction "2_2") (pintype "passive"))
      (node (ref "RS12") (pin "2") (pinfunction "2_2") (pintype "passive"))
      (node (ref "RS14") (pin "2") (pinfunction "2_2") (pintype "passive"))
      (node (ref "RS16") (pin "2") (pinfunction "2_2") (pintype "passive"))
      (node (ref "RS18") (pin "2") (pinfunction "2_2") (pintype "passive"))
      (node (ref "RS4") (pin "2") (pinfunction "2_2") (pintype "passive"))
      (node (ref "RS6") (pin "2") (pinfunction "2_2") (pintype "passive"))
      (node (ref "RS8") (pin "2") (pinfunction "2_2") (pintype "passive"))
      (node (ref "SENSE_VP1") (pin "4") (pinfunction "VIN-_4") (pintype "bidirectional"))
    )
    (net (code "8") (name "+VP2") (class "Default")
      (node (ref "JDSV1") (pin "1") (pinfunction "1_1") (pintype "bidirectional"))
      (node (ref "JDSV2") (pin "1") (pinfunction "1_1") (pintype "bidirectional"))
      (node (ref "R11") (pin "2") (pinfunction "2_2") (pintype "passive"))
      (node (ref "SENSE_VP2") (pin "4") (pinfunction "VIN-_4") (pintype "bidirectional"))
    )
    (net (code "9") (name "+VP3") (class "Default")
      (node (ref "MOTB1-2") (pin "11") (pinfunction "VM_11") (pintype "bidirectional"))
      (node (ref "MOTB1-2") (pin "12") (pinfunction "VM_12") (pintype "bidirectional"))
      (node (ref "MOTB3-4") (pin "11") (pinfunction "VM_11") (pintype "bidirectional"))
      (node (ref "MOTB3-4") (pin "12") (pinfunction "VM_12") (pintype "bidirectional"))
      (node (ref "MOTB5-6") (pin "11") (pinfunction "VM_11") (pintype "bidirectional"))
      (node (ref "MOTB5-6") (pin "12") (pinfunction "VM_12") (pintype "bidirectional"))
      (node (ref "MOTB7-8") (pin "11") (pinfunction "VM_11") (pintype "bidirectional"))
      (node (ref "MOTB7-8") (pin "12") (pinfunction "VM_12") (pintype "bidirectional"))
      (node (ref "R14") (pin "2") (pinfunction "2_2") (pintype "passive"))
      (node (ref "SENSE_VP3") (pin "4") (pinfunction "VIN-_4") (pintype "bidirectional"))
    )
    (net (code "10") (name "+VP4") (class "Default")
      (node (ref "C13") (pin "1") (pinfunction "1_1") (pintype "passive"))
      (node (ref "C35") (pin "1") (pinfunction "1_1") (pintype "passive"))
      (node (ref "C37") (pin "1") (pinfunction "1_1") (pintype "passive"))
      (node (ref "C39") (pin "1") (pinfunction "1_1") (pintype "passive"))
      (node (ref "C43") (pin "1") (pinfunction "1_1") (pintype "passive"))
      (node (ref "C45") (pin "1") (pinfunction "1_1") (pintype "passive"))
      (node (ref "D1") (pin "C") (pinfunction "C_C") (pintype "passive"))
      (node (ref "D2") (pin "C") (pinfunction "C_C") (pintype "passive"))
      (node (ref "D3") (pin "C") (pinfunction "C_C") (pintype "passive"))
      (node (ref "D4") (pin "C") (pinfunction "C_C") (pintype "passive"))
      (node (ref "D5") (pin "C") (pinfunction "C_C") (pintype "passive"))
      (node (ref "D6") (pin "C") (pinfunction "C_C") (pintype "passive"))
      (node (ref "JS1") (pin "1") (pinfunction "1_1") (pintype "bidirectional"))
      (node (ref "JS2") (pin "1") (pinfunction "1_1") (pintype "bidirectional"))
      (node (ref "JS3") (pin "1") (pinfunction "1_1") (pintype "bidirectional"))
      (node (ref "JS4") (pin "1") (pinfunction "1_1") (pintype "bidirectional"))
      (node (ref "JS5") (pin "1") (pinfunction "1_1") (pintype "bidirectional"))
      (node (ref "JS6") (pin "1") (pinfunction "1_1") (pintype "bidirectional"))
      (node (ref "MOS1") (pin "4") (pinfunction "VIN,R1_4") (pintype "bidirectional"))
      (node (ref "MOS2") (pin "4") (pinfunction "VIN,R1_4") (pintype "bidirectional"))
      (node (ref "MOS3") (pin "4") (pinfunction "VIN,R1_4") (pintype "bidirectional"))
      (node (ref "MOS4") (pin "4") (pinfunction "VIN,R1_4") (pintype "bidirectional"))
      (node (ref "MOS5") (pin "4") (pinfunction "VIN,R1_4") (pintype "bidirectional"))
      (node (ref "MOS6") (pin "4") (pinfunction "VIN,R1_4") (pintype "bidirectional"))
      (node (ref "MOS7") (pin "4") (pinfunction "VIN,R1_4") (pintype "bidirectional"))
      (node (ref "MOS8") (pin "4") (pinfunction "VIN,R1_4") (pintype "bidirectional"))
      (node (ref "R10") (pin "1") (pinfunction "1_1") (pintype "passive"))
      (node (ref "R16") (pin "2") (pinfunction "2_2") (pintype "passive"))
      (node (ref "R25") (pin "1") (pinfunction "1_1") (pintype "passive"))
      (node (ref "R28") (pin "1") (pinfunction "1_1") (pintype "passive"))
      (node (ref "R29") (pin "1") (pinfunction "1_1") (pintype "passive"))
      (node (ref "R31") (pin "1") (pinfunction "1_1") (pintype "passive"))
      (node (ref "R33") (pin "1") (pinfunction "1_1") (pintype "passive"))
      (node (ref "R37") (pin "2") (pinfunction "2_2") (pintype "passive"))
      (node (ref "R39") (pin "1") (pinfunction "1_1") (pintype "passive"))
      (node (ref "R41") (pin "1") (pinfunction "1_1") (pintype "passive"))
      (node (ref "R45") (pin "2") (pinfunction "2_2") (pintype "passive"))
      (node (ref "R48") (pin "2") (pinfunction "2_2") (pintype "passive"))
      (node (ref "R51") (pin "2") (pinfunction "2_2") (pintype "passive"))
      (node (ref "R54") (pin "2") (pinfunction "2_2") (pintype "passive"))
      (node (ref "R57") (pin "2") (pinfunction "2_2") (pintype "passive"))
      (node (ref "SENSE_VP4") (pin "4") (pinfunction "VIN-_4") (pintype "bidirectional"))
      (node (ref "SOL1") (pin "6") (pinfunction "VS_6") (pintype "bidirectional"))
      (node (ref "SOL2") (pin "6") (pinfunction "VS_6") (pintype "bidirectional"))
      (node (ref "SOL3") (pin "6") (pinfunction "VS_6") (pintype "bidirectional"))
      (node (ref "SOL4") (pin "6") (pinfunction "VS_6") (pintype "bidirectional"))
      (node (ref "SOL5") (pin "6") (pinfunction "VS_6") (pintype "bidirectional"))
      (node (ref "SOL6") (pin "6") (pinfunction "VS_6") (pintype "bidirectional"))
    )
    (net (code "11") (name "ADC1_EOC") (class "Default")
      (node (ref "ADC1") (pin "19") (pinfunction "EOC_19") (pintype "bidirectional"))
      (node (ref "JCTRL") (pin "9") (pinfunction "9_9") (pintype "bidirectional"))
    )
    (net (code "12") (name "ADC1_VBAT") (class "Default")
      (node (ref "ADC1") (pin "5") (pinfunction "AIN4_5") (pintype "bidirectional"))
      (node (ref "C65") (pin "1") (pinfunction "1_1") (pintype "passive"))
      (node (ref "R92") (pin "2") (pinfunction "2_2") (pintype "passive"))
    )
    (net (code "13") (name "ADC1_VP1") (class "Default")
      (node (ref "ADC1") (pin "3") (pinfunction "AIN2_3") (pintype "bidirectional"))
      (node (ref "C61") (pin "1") (pinfunction "1_1") (pintype "passive"))
      (node (ref "R86") (pin "2") (pinfunction "2_2") (pintype "passive"))
    )
    (net (code "14") (name "ADC1_VP2") (class "Default")
      (node (ref "ADC1") (pin "4") (pinfunction "AIN3_4") (pintype "bidirectional"))
      (node (ref "C62") (pin "1") (pinfunction "1_1") (pintype "passive"))
      (node (ref "R87") (pin "2") (pinfunction "2_2") (pintype "passive"))
    )
    (net (code "15") (name "ADC1_VP3") (class "Default")
      (node (ref "ADC1") (pin "1") (pinfunction "AIN0_1") (pintype "bidirectional"))
      (node (ref "C63") (pin "1") (pinfunction "1_1") (pintype "passive"))
      (node (ref "R88") (pin "2") (pinfunction "2_2") (pintype "passive"))
    )
    (net (code "16") (name "ADC1_VP4") (class "Default")
      (node (ref "ADC1") (pin "2") (pinfunction "AIN1_2") (pintype "bidirectional"))
      (node (ref "C64") (pin "1") (pinfunction "1_1") (pintype "passive"))
      (node (ref "R89") (pin "2") (pinfunction "2_2") (pintype "passive"))
    )
    (net (code "17") (name "ADC1_VREF") (class "Default")
      (node (ref "ADC1") (pin "14") (pinfunction "REF+_14") (pintype "bidirectional"))
      (node (ref "C59") (pin "1") (pinfunction "1_1") (pintype "passive"))
      (node (ref "REF1") (pin "2") (pinfunction "OUT_2") (pintype "output"))
    )
    (net (code "18") (name "ADC2_EOC") (class "Default")
      (node (ref "ADC2") (pin "19") (pinfunction "EOC_19") (pintype "bidirectional"))
      (node (ref "JCTRL") (pin "10") (pinfunction "10_10") (pintype "bidirectional"))
    )
    (net (code "19") (name "ADC2_MOTA1") (class "Default")
      (node (ref "ADC2") (pin "9") (pinfunction "AIN8_9") (pintype "bidirectional"))
      (node (ref "C66") (pin "1") (pinfunction "1_1") (pintype "passive"))
      (node (ref "R99") (pin "2") (pinfunction "2_2") (pintype "passive"))
    )
    (net (code "20") (name "ADC2_MOTA2") (class "Default")
      (node (ref "ADC2") (pin "8") (pinfunction "AIN7_8") (pintype "bidirectional"))
      (node (ref "C67") (pin "1") (pinfunction "1_1") (pintype "passive"))
      (node (ref "R100") (pin "2") (pinfunction "2_2") (pintype "passive"))
    )
    (net (code "21") (name "ADC2_MOTA3") (class "Default")
      (node (ref "ADC2") (pin "7") (pinfunction "AIN6_7") (pintype "bidirectional"))
      (node (ref "C68") (pin "1") (pinfunction "1_1") (pintype "passive"))
      (node (ref "R101") (pin "2") (pinfunction "2_2") (pintype "passive"))
    )
    (net (code "22") (name "ADC2_MOTB1") (class "Default")
      (node (ref "ADC2") (pin "4") (pinfunction "AIN3_4") (pintype "bidirectional"))
      (node (ref "C74") (pin "1") (pinfunction "1_1") (pintype "passive"))
      (node (ref "R102") (pin "2") (pinfunction "2_2") (pintype "passive"))
    )
    (net (code "23") (name "ADC2_MOTB2") (class "Default")
      (node (ref "ADC2") (pin "3") (pinfunction "AIN2_3") (pintype "bidirectional"))
      (node (ref "C75") (pin "1") (pinfunction "1_1") (pintype "passive"))
      (node (ref "R109") (pin "2") (pinfunction "2_2") (pintype "passive"))
    )
    (net (code "24") (name "ADC2_MOTB3") (class "Default")
      (node (ref "ADC2") (pin "2") (pinfunction "AIN1_2") (pintype "bidirectional"))
      (node (ref "C77") (pin "1") (pinfunction "1_1") (pintype "passive"))
      (node (ref "R111") (pin "2") (pinfunction "2_2") (pintype "passive"))
    )
    (net (code "25") (name "ADC2_MOTB4") (class "Default")
      (node (ref "ADC2") (pin "1") (pinfunction "AIN0_1") (pintype "bidirectional"))
      (node (ref "C76") (pin "1") (pinfunction "1_1") (pintype "passive"))
      (node (ref "R110") (pin "2") (pinfunction "2_2") (pintype "passive"))
    )
    (net (code "26") (name "ADC2_MOTB5") (class "Default")
      (node (ref "ADC2") (pin "11") (pinfunction "AIN9_11") (pintype "bidirectional"))
      (node (ref "C78") (pin "1") (pinfunction "1_1") (pintype "passive"))
      (node (ref "R112") (pin "2") (pinfunction "2_2") (pintype "passive"))
    )
    (net (code "27") (name "ADC2_MOTB6") (class "Default")
      (node (ref "ADC2") (pin "12") (pinfunction "AIN10_12") (pintype "bidirectional"))
      (node (ref "C79") (pin "1") (pinfunction "1_1") (pintype "passive"))
      (node (ref "R119") (pin "2") (pinfunction "2_2") (pintype "passive"))
    )
    (net (code "28") (name "ADC2_MOTB7") (class "Default")
      (node (ref "ADC2") (pin "6") (pinfunction "AIN5_6") (pintype "bidirectional"))
      (node (ref "C81") (pin "1") (pinfunction "1_1") (pintype "passive"))
      (node (ref "R121") (pin "2") (pinfunction "2_2") (pintype "passive"))
    )
    (net (code "29") (name "ADC2_MOTB8") (class "Default")
      (node (ref "ADC2") (pin "5") (pinfunction "AIN4_5") (pintype "bidirectional"))
      (node (ref "C80") (pin "1") (pinfunction "1_1") (pintype "passive"))
      (node (ref "R120") (pin "2") (pinfunction "2_2") (pintype "passive"))
    )
    (net (code "30") (name "ADC2_VREF") (class "Default")
      (node (ref "ADC2") (pin "14") (pinfunction "REF+_14") (pintype "bidirectional"))
      (node (ref "C69") (pin "1") (pinfunction "1_1") (pintype "passive"))
      (node (ref "REF2") (pin "2") (pinfunction "OUT_2") (pintype "output"))
    )
    (net (code "31") (name "ASV1_OUT") (class "Default")
      (node (ref "ASV1") (pin "4") (pinfunction "4_4") (pintype "bidirectional"))
      (node (ref "JAS1") (pin "2") (pinfunction "2_2") (pintype "bidirectional"))
      (node (ref "RS4") (pin "1") (pinfunction "1_1") (pintype "passive"))
    )
    (net (code "32") (name "ASV1_PWM") (class "Default")
      (node (ref "JCTRL") (pin "42") (pinfunction "42_42") (pintype "bidirectional"))
      (node (ref "RS3") (pin "1") (pinfunction "1_1") (pintype "passive"))
    )
    (net (code "33") (name "ASV2_OUT") (class "Default")
      (node (ref "ASV2") (pin "4") (pinfunction "4_4") (pintype "bidirectional"))
      (node (ref "JAS2") (pin "2") (pinfunction "2_2") (pintype "bidirectional"))
      (node (ref "RS6") (pin "1") (pinfunction "1_1") (pintype "passive"))
    )
    (net (code "34") (name "ASV2_PWM") (class "Default")
      (node (ref "JCTRL") (pin "43") (pinfunction "43_43") (pintype "bidirectional"))
      (node (ref "RS5") (pin "1") (pinfunction "1_1") (pintype "passive"))
    )
    (net (code "35") (name "ASV3_OUT") (class "Default")
      (node (ref "ASV3") (pin "4") (pinfunction "4_4") (pintype "bidirectional"))
      (node (ref "JAS3") (pin "2") (pinfunction "2_2") (pintype "bidirectional"))
      (node (ref "RS8") (pin "1") (pinfunction "1_1") (pintype "passive"))
    )
    (net (code "36") (name "ASV3_PWM") (class "Default")
      (node (ref "JCTRL") (pin "44") (pinfunction "44_44") (pintype "bidirectional"))
      (node (ref "RS7") (pin "1") (pinfunction "1_1") (pintype "passive"))
    )
    (net (code "37") (name "ASV4_OUT") (class "Default")
      (node (ref "ASV4") (pin "4") (pinfunction "4_4") (pintype "bidirectional"))
      (node (ref "JAS4") (pin "2") (pinfunction "2_2") (pintype "bidirectional"))
      (node (ref "RS10") (pin "1") (pinfunction "1_1") (pintype "passive"))
    )
    (net (code "38") (name "ASV4_PWM") (class "Default")
      (node (ref "JCTRL") (pin "45") (pinfunction "45_45") (pintype "bidirectional"))
      (node (ref "RS9") (pin "1") (pinfunction "1_1") (pintype "passive"))
    )
    (net (code "39") (name "ASV5_OUT") (class "Default")
      (node (ref "ASV5") (pin "4") (pinfunction "4_4") (pintype "bidirectional"))
      (node (ref "JAS5") (pin "2") (pinfunction "2_2") (pintype "bidirectional"))
      (node (ref "RS12") (pin "1") (pinfunction "1_1") (pintype "passive"))
    )
    (net (code "40") (name "ASV5_PWM") (class "Default")
      (node (ref "JCTRL") (pin "46") (pinfunction "46_46") (pintype "bidirectional"))
      (node (ref "RS11") (pin "1") (pinfunction "1_1") (pintype "passive"))
    )
    (net (code "41") (name "ASV6_OUT") (class "Default")
      (node (ref "ASV6") (pin "4") (pinfunction "4_4") (pintype "bidirectional"))
      (node (ref "JAS6") (pin "2") (pinfunction "2_2") (pintype "bidirectional"))
      (node (ref "RS14") (pin "1") (pinfunction "1_1") (pintype "passive"))
    )
    (net (code "42") (name "ASV6_PWM") (class "Default")
      (node (ref "JCTRL") (pin "47") (pinfunction "47_47") (pintype "bidirectional"))
      (node (ref "RS13") (pin "1") (pinfunction "1_1") (pintype "passive"))
    )
    (net (code "43") (name "ASV7_OUT") (class "Default")
      (node (ref "ASV7") (pin "4") (pinfunction "4_4") (pintype "bidirectional"))
      (node (ref "JAS7") (pin "2") (pinfunction "2_2") (pintype "bidirectional"))
      (node (ref "RS16") (pin "1") (pinfunction "1_1") (pintype "passive"))
    )
    (net (code "44") (name "ASV7_PWM") (class "Default")
      (node (ref "JCTRL") (pin "48") (pinfunction "48_48") (pintype "bidirectional"))
      (node (ref "RS15") (pin "1") (pinfunction "1_1") (pintype "passive"))
    )
    (net (code "45") (name "ASV8_OUT") (class "Default")
      (node (ref "ASV8") (pin "4") (pinfunction "4_4") (pintype "bidirectional"))
      (node (ref "JAS8") (pin "2") (pinfunction "2_2") (pintype "bidirectional"))
      (node (ref "RS18") (pin "1") (pinfunction "1_1") (pintype "passive"))
    )
    (net (code "46") (name "ASV8_PWM") (class "Default")
      (node (ref "JCTRL") (pin "49") (pinfunction "49_49") (pintype "bidirectional"))
      (node (ref "RS17") (pin "1") (pinfunction "1_1") (pintype "passive"))
    )
    (net (code "47") (name "CEL1_MEAS") (class "Default")
      (node (ref "ADC1") (pin "6") (pinfunction "AIN5_6") (pintype "bidirectional"))
      (node (ref "C46") (pin "1") (pinfunction "1_1") (pintype "passive"))
      (node (ref "R78") (pin "2") (pinfunction "2_2") (pintype "passive"))
      (node (ref "R79") (pin "2") (pinfunction "2_2") (pintype "passive"))
    )
    (net (code "48") (name "CEL2_MEAS") (class "Default")
      (node (ref "ADC1") (pin "7") (pinfunction "AIN6_7") (pintype "bidirectional"))
      (node (ref "C48") (pin "1") (pinfunction "1_1") (pintype "passive"))
      (node (ref "R59") (pin "2") (pinfunction "2_2") (pintype "passive"))
      (node (ref "R60") (pin "2") (pinfunction "2_2") (pintype "passive"))
    )
    (net (code "49") (name "CEL3_MEAS") (class "Default")
      (node (ref "ADC1") (pin "9") (pinfunction "AIN8_9") (pintype "bidirectional"))
      (node (ref "C50") (pin "1") (pinfunction "1_1") (pintype "passive"))
      (node (ref "R62") (pin "2") (pinfunction "2_2") (pintype "passive"))
      (node (ref "R63") (pin "2") (pinfunction "2_2") (pintype "passive"))
    )
    (net (code "50") (name "CEL4_MEAS") (class "Default")
      (node (ref "ADC1") (pin "8") (pinfunction "AIN7_8") (pintype "bidirectional"))
      (node (ref "C52") (pin "1") (pinfunction "1_1") (pintype "passive"))
      (node (ref "R65") (pin "2") (pinfunction "2_2") (pintype "passive"))
      (node (ref "R66") (pin "2") (pinfunction "2_2") (pintype "passive"))
    )
    (net (code "51") (name "CEL5_MEAS") (class "Default")
      (node (ref "ADC1") (pin "12") (pinfunction "AIN10_12") (pintype "bidirectional"))
      (node (ref "C54") (pin "1") (pinfunction "1_1") (pintype "passive"))
      (node (ref "R68") (pin "2") (pinfunction "2_2") (pintype "passive"))
      (node (ref "R69") (pin "2") (pinfunction "2_2") (pintype "passive"))
    )
    (net (code "52") (name "CEL6_MEAS") (class "Default")
      (node (ref "ADC1") (pin "11") (pinfunction "AIN9_11") (pintype "bidirectional"))
      (node (ref "C56") (pin "1") (pinfunction "1_1") (pintype "passive"))
      (node (ref "R71") (pin "2") (pinfunction "2_2") (pintype "passive"))
      (node (ref "R72") (pin "2") (pinfunction "2_2") (pintype "passive"))
    )
    (net (code "53") (name "DSV1_TXRX") (class "Default")
      (node (ref "JCTRL") (pin "40") (pinfunction "40_40") (pintype "bidirectional"))
      (node (ref "JDSV1") (pin "2") (pinfunction "2_2") (pintype "bidirectional"))
      (node (ref "JDSV2") (pin "2") (pinfunction "2_2") (pintype "bidirectional"))
    )
    (net (code "54") (name "DSV2_TXRX") (class "Default")
      (node (ref "JCTRL") (pin "41") (pinfunction "41_41") (pintype "bidirectional"))
    )
    (net (code "55") (name "GND") (class "Default")
      (node (ref "ADC1") (pin "10") (pinfunction "GND_10") (pintype "power_in"))
      (node (ref "ADC1") (pin "13") (pinfunction "REF-_13") (pintype "bidirectional"))
      (node (ref "ADC2") (pin "10") (pinfunction "GND_10") (pintype "power_in"))
      (node (ref "ADC2") (pin "13") (pinfunction "REF-_13") (pintype "bidirectional"))
      (node (ref "ASV1") (pin "2") (pinfunction "2_2") (pintype "bidirectional"))
      (node (ref "ASV1") (pin "3") (pinfunction "3_3") (pintype "bidirectional"))
      (node (ref "ASV2") (pin "2") (pinfunction "2_2") (pintype "bidirectional"))
      (node (ref "ASV2") (pin "3") (pinfunction "3_3") (pintype "bidirectional"))
      (node (ref "ASV3") (pin "2") (pinfunction "2_2") (pintype "bidirectional"))
      (node (ref "ASV3") (pin "3") (pinfunction "3_3") (pintype "bidirectional"))
      (node (ref "ASV4") (pin "2") (pinfunction "2_2") (pintype "bidirectional"))
      (node (ref "ASV4") (pin "3") (pinfunction "3_3") (pintype "bidirectional"))
      (node (ref "ASV5") (pin "2") (pinfunction "2_2") (pintype "bidirectional"))
      (node (ref "ASV5") (pin "3") (pinfunction "3_3") (pintype "bidirectional"))
      (node (ref "ASV6") (pin "2") (pinfunction "2_2") (pintype "bidirectional"))
      (node (ref "ASV6") (pin "3") (pinfunction "3_3") (pintype "bidirectional"))
      (node (ref "ASV7") (pin "2") (pinfunction "2_2") (pintype "bidirectional"))
      (node (ref "ASV7") (pin "3") (pinfunction "3_3") (pintype "bidirectional"))
      (node (ref "ASV8") (pin "2") (pinfunction "2_2") (pintype "bidirectional"))
      (node (ref "ASV8") (pin "3") (pinfunction "3_3") (pintype "bidirectional"))
      (node (ref "C1") (pin "2") (pinfunction "2_2") (pintype "passive"))
      (node (ref "C11") (pin "2") (pinfunction "2_2") (pintype "passive"))
      (node (ref "C12") (pin "2") (pinfunction "2_2") (pintype "passive"))
      (node (ref "C13") (pin "2") (pinfunction "2_2") (pintype "passive"))
      (node (ref "C14") (pin "2") (pinfunction "2_2") (pintype "passive"))
      (node (ref "C15") (pin "2") (pinfunction "2_2") (pintype "passive"))
      (node (ref "C16") (pin "2") (pinfunction "2_2") (pintype "passive"))
      (node (ref "C17") (pin "2") (pinfunction "2_2") (pintype "passive"))
      (node (ref "C18") (pin "-") (pinfunction "-_-") (pintype "passive"))
      (node (ref "C19") (pin "-") (pinfunction "-_-") (pintype "passive"))
      (node (ref "C2") (pin "2") (pinfunction "2_2") (pintype "passive"))
      (node (ref "C20") (pin "2") (pinfunction "2_2") (pintype "passive"))
      (node (ref "C21") (pin "-") (pinfunction "-_-") (pintype "passive"))
      (node (ref "C22") (pin "2") (pinfunction "2_2") (pintype "passive"))
      (node (ref "C23") (pin "-") (pinfunction "-_-") (pintype "passive"))
      (node (ref "C24") (pin "2") (pinfunction "2_2") (pintype "passive"))
      (node (ref "C25") (pin "-") (pinfunction "-_-") (pintype "passive"))
      (node (ref "C26") (pin "2") (pinfunction "2_2") (pintype "passive"))
      (node (ref "C27") (pin "2") (pinfunction "2_2") (pintype "passive"))
      (node (ref "C29") (pin "2") (pinfunction "2_2") (pintype "passive"))
      (node (ref "C3") (pin "2") (pinfunction "2_2") (pintype "passive"))
      (node (ref "C31") (pin "2") (pinfunction "2_2") (pintype "passive"))
      (node (ref "C33") (pin "2") (pinfunction "2_2") (pintype "passive"))
      (node (ref "C34") (pin "2") (pinfunction "2_2") (pintype "passive"))
      (node (ref "C35") (pin "2") (pinfunction "2_2") (pintype "passive"))
      (node (ref "C36") (pin "2") (pinfunction "2_2") (pintype "passive"))
      (node (ref "C37") (pin "2") (pinfunction "2_2") (pintype "passive"))
      (node (ref "C38") (pin "2") (pinfunction "2_2") (pintype "passive"))
      (node (ref "C39") (pin "2") (pinfunction "2_2") (pintype "passive"))
      (node (ref "C4") (pin "2") (pinfunction "2_2") (pintype "passive"))
      (node (ref "C41") (pin "2") (pinfunction "2_2") (pintype "passive"))
      (node (ref "C42") (pin "2") (pinfunction "2_2") (pintype "passive"))
      (node (ref "C43") (pin "2") (pinfunction "2_2") (pintype "passive"))
      (node (ref "C44") (pin "2") (pinfunction "2_2") (pintype "passive"))
      (node (ref "C45") (pin "2") (pinfunction "2_2") (pintype "passive"))
      (node (ref "C46") (pin "2") (pinfunction "2_2") (pintype "passive"))
      (node (ref "C48") (pin "2") (pinfunction "2_2") (pintype "passive"))
      (node (ref "C50") (pin "2") (pinfunction "2_2") (pintype "passive"))
      (node (ref "C52") (pin "2") (pinfunction "2_2") (pintype "passive"))
      (node (ref "C54") (pin "2") (pinfunction "2_2") (pintype "passive"))
      (node (ref "C56") (pin "2") (pinfunction "2_2") (pintype "passive"))
      (node (ref "C58") (pin "2") (pinfunction "2_2") (pintype "passive"))
      (node (ref "C59") (pin "2") (pinfunction "2_2") (pintype "passive"))
      (node (ref "C60") (pin "2") (pinfunction "2_2") (pintype "passive"))
      (node (ref "C61") (pin "2") (pinfunction "2_2") (pintype "passive"))
      (node (ref "C62") (pin "2") (pinfunction "2_2") (pintype "passive"))
      (node (ref "C63") (pin "2") (pinfunction "2_2") (pintype "passive"))
      (node (ref "C64") (pin "2") (pinfunction "2_2") (pintype "passive"))
      (node (ref "C65") (pin "2") (pinfunction "2_2") (pintype "passive"))
      (node (ref "C66") (pin "2") (pinfunction "2_2") (pintype "passive"))
      (node (ref "C67") (pin "2") (pinfunction "2_2") (pintype "passive"))
      (node (ref "C68") (pin "2") (pinfunction "2_2") (pintype "passive"))
      (node (ref "C69") (pin "2") (pinfunction "2_2") (pintype "passive"))
      (node (ref "C7") (pin "2") (pinfunction "2_2") (pintype "passive"))
      (node (ref "C70") (pin "2") (pinfunction "2_2") (pintype "passive"))
      (node (ref "C71") (pin "2") (pinfunction "2_2") (pintype "passive"))
      (node (ref "C72") (pin "2") (pinfunction "2_2") (pintype "passive"))
      (node (ref "C73") (pin "2") (pinfunction "2_2") (pintype "passive"))
      (node (ref "C74") (pin "2") (pinfunction "2_2") (pintype "passive"))
      (node (ref "C75") (pin "2") (pinfunction "2_2") (pintype "passive"))
      (node (ref "C76") (pin "2") (pinfunction "2_2") (pintype "passive"))
      (node (ref "C77") (pin "2") (pinfunction "2_2") (pintype "passive"))
      (node (ref "C78") (pin "2") (pinfunction "2_2") (pintype "passive"))
      (node (ref "C79") (pin "2") (pinfunction "2_2") (pintype "passive"))
      (node (ref "C80") (pin "2") (pinfunction "2_2") (pintype "passive"))
      (node (ref "C81") (pin "2") (pinfunction "2_2") (pintype "passive"))
      (node (ref "C9") (pin "2") (pinfunction "2_2") (pintype "passive"))
      (node (ref "CEL1") (pin "1") (pinfunction "REF_1") (pintype "bidirectional"))
      (node (ref "CEL1") (pin "4") (pinfunction "V-_4") (pintype "bidirectional"))
      (node (ref "CEL2") (pin "1") (pinfunction "REF_1") (pintype "bidirectional"))
      (node (ref "CEL2") (pin "4") (pinfunction "V-_4") (pintype "bidirectional"))
      (node (ref "CEL3") (pin "1") (pinfunction "REF_1") (pintype "bidirectional"))
      (node (ref "CEL3") (pin "4") (pinfunction "V-_4") (pintype "bidirectional"))
      (node (ref "CEL4") (pin "1") (pinfunction "REF_1") (pintype "bidirectional"))
      (node (ref "CEL4") (pin "4") (pinfunction "V-_4") (pintype "bidirectional"))
      (node (ref "CEL5") (pin "1") (pinfunction "REF_1") (pintype "bidirectional"))
      (node (ref "CEL5") (pin "4") (pinfunction "V-_4") (pintype "bidirectional"))
      (node (ref "CEL6") (pin "1") (pinfunction "REF_1") (pintype "bidirectional"))
      (node (ref "CEL6") (pin "4") (pinfunction "V-_4") (pintype "bidirectional"))
      (node (ref "IC1") (pin "11") (pinfunction "V-_11") (pintype "power_in"))
      (node (ref "IC2") (pin "11") (pinfunction "V-_11") (pintype "power_in"))
      (node (ref "IC3") (pin "11") (pinfunction "V-_11") (pintype "power_in"))
      (node (ref "IC4") (pin "11") (pinfunction "V-_11") (pintype "power_in"))
      (node (ref "IOE1") (pin "10") (pinfunction "VSS_10") (pintype "power_in"))
      (node (ref "IOE1") (pin "16") (pinfunction "A1_16") (pintype "input"))
      (node (ref "IOE1") (pin "17") (pinfunction "A2_17") (pintype "input"))
      (node (ref "IOE2") (pin "10") (pinfunction "VSS_10") (pintype "power_in"))
      (node (ref "IOE2") (pin "15") (pinfunction "A0_15") (pintype "input"))
      (node (ref "IOE2") (pin "17") (pinfunction "A2_17") (pintype "input"))
      (node (ref "IOE3") (pin "10") (pinfunction "VSS_10") (pintype "power_in"))
      (node (ref "IOE3") (pin "17") (pinfunction "A2_17") (pintype "input"))
      (node (ref "JAS1") (pin "3") (pinfunction "3_3") (pintype "bidirectional"))
      (node (ref "JAS2") (pin "3") (pinfunction "3_3") (pintype "bidirectional"))
      (node (ref "JAS3") (pin "3") (pinfunction "3_3") (pintype "bidirectional"))
      (node (ref "JAS4") (pin "3") (pinfunction "3_3") (pintype "bidirectional"))
      (node (ref "JAS5") (pin "3") (pinfunction "3_3") (pintype "bidirectional"))
      (node (ref "JAS6") (pin "3") (pinfunction "3_3") (pintype "bidirectional"))
      (node (ref "JAS7") (pin "3") (pinfunction "3_3") (pintype "bidirectional"))
      (node (ref "JAS8") (pin "3") (pinfunction "3_3") (pintype "bidirectional"))
      (node (ref "JBAT1") (pin "2") (pinfunction "2_2") (pintype "bidirectional"))
      (node (ref "JCTRL") (pin "50") (pinfunction "50_50") (pintype "bidirectional"))
      (node (ref "JDSV1") (pin "3") (pinfunction "3_3") (pintype "bidirectional"))
      (node (ref "JDSV2") (pin "3") (pinfunction "3_3") (pintype "bidirectional"))
      (node (ref "JM1") (pin "2") (pinfunction "2_2") (pintype "bidirectional"))
      (node (ref "JM2") (pin "2") (pinfunction "2_2") (pintype "bidirectional"))
      (node (ref "JM3") (pin "2") (pinfunction "2_2") (pintype "bidirectional"))
      (node (ref "JM4") (pin "2") (pinfunction "2_2") (pintype "bidirectional"))
      (node (ref "JM5") (pin "2") (pinfunction "2_2") (pintype "bidirectional"))
      (node (ref "JM6") (pin "2") (pinfunction "2_2") (pintype "bidirectional"))
      (node (ref "JM7") (pin "2") (pinfunction "2_2") (pintype "bidirectional"))
      (node (ref "JM8") (pin "2") (pinfunction "2_2") (pintype "bidirectional"))
      (node (ref "JVL") (pin "5") (pinfunction "5_5") (pintype "bidirectional"))
      (node (ref "JVL") (pin "6") (pinfunction "6_6") (pintype "bidirectional"))
      (node (ref "MOTA1") (pin "1") (pinfunction "GND_1") (pintype "bidirectional"))
      (node (ref "MOTA1") (pin "2") (pinfunction "GND_2") (pintype "bidirectional"))
      (node (ref "MOTA1") (pin "3") (pinfunction "GND_3") (pintype "bidirectional"))
      (node (ref "MOTA2") (pin "1") (pinfunction "GND_1") (pintype "bidirectional"))
      (node (ref "MOTA2") (pin "2") (pinfunction "GND_2") (pintype "bidirectional"))
      (node (ref "MOTA2") (pin "3") (pinfunction "GND_3") (pintype "bidirectional"))
      (node (ref "MOTA3") (pin "1") (pinfunction "GND_1") (pintype "bidirectional"))
      (node (ref "MOTA3") (pin "2") (pinfunction "GND_2") (pintype "bidirectional"))
      (node (ref "MOTA3") (pin "3") (pinfunction "GND_3") (pintype "bidirectional"))
      (node (ref "MOTB1-2") (pin "1") (pinfunction "GND_1") (pintype "bidirectional"))
      (node (ref "MOTB1-2") (pin "2") (pinfunction "GND_2") (pintype "bidirectional"))
      (node (ref "MOTB3-4") (pin "1") (pinfunction "GND_1") (pintype "bidirectional"))
      (node (ref "MOTB3-4") (pin "2") (pinfunction "GND_2") (pintype "bidirectional"))
      (node (ref "MOTB5-6") (pin "1") (pinfunction "GND_1") (pintype "bidirectional"))
      (node (ref "MOTB5-6") (pin "2") (pinfunction "GND_2") (pintype "bidirectional"))
      (node (ref "MOTB7-8") (pin "1") (pinfunction "GND_1") (pintype "bidirectional"))
      (node (ref "MOTB7-8") (pin "2") (pinfunction "GND_2") (pintype "bidirectional"))
      (node (ref "Q1") (pin "2") (pinfunction "S_2") (pintype "passive"))
      (node (ref "Q2") (pin "2") (pinfunction "S_2") (pintype "passive"))
      (node (ref "Q3") (pin "2") (pinfunction "S_2") (pintype "passive"))
      (node (ref "Q4") (pin "2") (pinfunction "S_2") (pintype "passive"))
      (node (ref "R104") (pin "1") (pinfunction "1_1") (pintype "passive"))
      (node (ref "R105") (pin "1") (pinfunction "1_1") (pintype "passive"))
      (node (ref "R107") (pin "1") (pinfunction "1_1") (pintype "passive"))
      (node (ref "R114") (pin "1") (pinfunction "1_1") (pintype "passive"))
      (node (ref "R115") (pin "1") (pinfunction "1_1") (pintype "passive"))
      (node (ref "R117") (pin "1") (pinfunction "1_1") (pintype "passive"))
      (node (ref "R12") (pin "1") (pinfunction "1_1") (pintype "passive"))
      (node (ref "R13") (pin "1") (pinfunction "1_1") (pintype "passive"))
      (node (ref "R15") (pin "1") (pinfunction "1_1") (pintype "passive"))
      (node (ref "R17") (pin "1") (pinfunction "1_1") (pintype "passive"))
      (node (ref "R26") (pin "1") (pinfunction "1_1") (pintype "passive"))
      (node (ref "R27") (pin "1") (pinfunction "1_1") (pintype "passive"))
      (node (ref "R3") (pin "1") (pinfunction "1_1") (pintype "passive"))
      (node (ref "R30") (pin "1") (pinfunction "1_1") (pintype "passive"))
      (node (ref "R32") (pin "1") (pinfunction "1_1") (pintype "passive"))
      (node (ref "R34") (pin "1") (pinfunction "1_1") (pintype "passive"))
      (node (ref "R35") (pin "1") (pinfunction "1_1") (pintype "passive"))
      (node (ref "R36") (pin "1") (pinfunction "1_1") (pintype "passive"))
      (node (ref "R38") (pin "1") (pinfunction "1_1") (pintype "passive"))
      (node (ref "R4") (pin "1") (pinfunction "1_1") (pintype "passive"))
      (node (ref "R40") (pin "1") (pinfunction "1_1") (pintype "passive"))
      (node (ref "R42") (pin "1") (pinfunction "1_1") (pintype "passive"))
      (node (ref "R43") (pin "1") (pinfunction "1_1") (pintype "passive"))
      (node (ref "R44") (pin "1") (pinfunction "1_1") (pintype "passive"))
      (node (ref "R46") (pin "1") (pinfunction "1_1") (pintype "passive"))
      (node (ref "R47") (pin "1") (pinfunction "1_1") (pintype "passive"))
      (node (ref "R49") (pin "1") (pinfunction "1_1") (pintype "passive"))
      (node (ref "R5") (pin "1") (pinfunction "1_1") (pintype "passive"))
      (node (ref "R50") (pin "1") (pinfunction "1_1") (pintype "passive"))
      (node (ref "R52") (pin "1") (pinfunction "1_1") (pintype "passive"))
      (node (ref "R53") (pin "1") (pinfunction "1_1") (pintype "passive"))
      (node (ref "R55") (pin "1") (pinfunction "1_1") (pintype "passive"))
      (node (ref "R56") (pin "1") (pinfunction "1_1") (pintype "passive"))
      (node (ref "R6") (pin "1") (pinfunction "1_1") (pintype "passive"))
      (node (ref "R60") (pin "1") (pinfunction "1_1") (pintype "passive"))
      (node (ref "R63") (pin "1") (pinfunction "1_1") (pintype "passive"))
      (node (ref "R66") (pin "1") (pinfunction "1_1") (pintype "passive"))
      (node (ref "R69") (pin "1") (pinfunction "1_1") (pintype "passive"))
      (node (ref "R7") (pin "1") (pinfunction "1_1") (pintype "passive"))
      (node (ref "R72") (pin "1") (pinfunction "1_1") (pintype "passive"))
      (node (ref "R75") (pin "1") (pinfunction "1_1") (pintype "passive"))
      (node (ref "R77") (pin "1") (pinfunction "1_1") (pintype "passive"))
      (node (ref "R79") (pin "1") (pinfunction "1_1") (pintype "passive"))
      (node (ref "R81") (pin "1") (pinfunction "1_1") (pintype "passive"))
      (node (ref "R83") (pin "1") (pinfunction "1_1") (pintype "passive"))
      (node (ref "R85") (pin "1") (pinfunction "1_1") (pintype "passive"))
      (node (ref "R9") (pin "1") (pinfunction "1_1") (pintype "passive"))
      (node (ref "R91") (pin "1") (pinfunction "1_1") (pintype "passive"))
      (node (ref "R94") (pin "1") (pinfunction "1_1") (pintype "passive"))
      (node (ref "R95") (pin "1") (pinfunction "1_1") (pintype "passive"))
      (node (ref "R97") (pin "1") (pinfunction "1_1") (pintype "passive"))
      (node (ref "REF1") (pin "3") (pinfunction "GND_3") (pintype "power_in"))
      (node (ref "REF2") (pin "3") (pinfunction "GND_3") (pintype "power_in"))
      (node (ref "SENSE_VBAT") (pin "2") (pinfunction "GND_2") (pintype "bidirectional"))
      (node (ref "SENSE_VP1") (pin "2") (pinfunction "GND_2") (pintype "bidirectional"))
      (node (ref "SENSE_VP2") (pin "2") (pinfunction "GND_2") (pintype "bidirectional"))
      (node (ref "SENSE_VP3") (pin "2") (pinfunction "GND_2") (pintype "bidirectional"))
      (node (ref "SENSE_VP4") (pin "2") (pinfunction "GND_2") (pintype "bidirectional"))
      (node (ref "SOL1") (pin "4") (pinfunction "GND_4") (pintype "bidirectional"))
      (node (ref "SOL2") (pin "4") (pinfunction "GND_4") (pintype "bidirectional"))
      (node (ref "SOL3") (pin "4") (pinfunction "GND_4") (pintype "bidirectional"))
      (node (ref "SOL4") (pin "4") (pinfunction "GND_4") (pintype "bidirectional"))
      (node (ref "SOL5") (pin "4") (pinfunction "GND_4") (pintype "bidirectional"))
      (node (ref "SOL6") (pin "4") (pinfunction "GND_4") (pintype "bidirectional"))
      (node (ref "VCC12") (pin "2") (pinfunction "GND_2") (pintype "power_in"))
      (node (ref "VCC120") (pin "2") (pinfunction "GND_2") (pintype "power_in"))
      (node (ref "VCC33") (pin "2") (pinfunction "GND_2") (pintype "power_in"))
      (node (ref "VCC50") (pin "2") (pinfunction "GND_2") (pintype "power_in"))
      (node (ref "VP1") (pin "1") (pinfunction "GND_1") (pintype "power_in"))
      (node (ref "VP1") (pin "7") (pinfunction "GND_7") (pintype "power_in"))
      (node (ref "VP2") (pin "1") (pinfunction "GND_1") (pintype "power_in"))
      (node (ref "VP2") (pin "7") (pinfunction "GND_7") (pintype "power_in"))
      (node (ref "VP3") (pin "1") (pinfunction "GND_1") (pintype "power_in"))
      (node (ref "VP3") (pin "7") (pinfunction "GND_7") (pintype "power_in"))
      (node (ref "VP4") (pin "1") (pinfunction "GND_1") (pintype "power_in"))
      (node (ref "VP4") (pin "7") (pinfunction "GND_7") (pintype "power_in"))
    )
    (net (code "56") (name "IOE_~{RESET}") (class "Default")
      (node (ref "IOE1") (pin "18") (pinfunction "~{RESET}_18") (pintype "input"))
      (node (ref "IOE2") (pin "18") (pinfunction "~{RESET}_18") (pintype "input"))
      (node (ref "IOE3") (pin "18") (pinfunction "~{RESET}_18") (pintype "input"))
      (node (ref "JCTRL") (pin "1") (pinfunction "1_1") (pintype "bidirectional"))
    )
    (net (code "57") (name "MOS1_EN") (class "Default")
      (node (ref "IOE3") (pin "8") (pinfunction "GPB7_8") (pintype "bidirectional"))
      (node (ref "MOS1") (pin "5") (pinfunction "ON/~{OFF}_5") (pintype "bidirectional"))
    )
    (net (code "58") (name "MOS2_EN") (class "Default")
      (node (ref "IOE3") (pin "7") (pinfunction "GPB6_7") (pintype "bidirectional"))
      (node (ref "MOS2") (pin "5") (pinfunction "ON/~{OFF}_5") (pintype "bidirectional"))
    )
    (net (code "59") (name "MOS3_EN") (class "Default")
      (node (ref "IOE3") (pin "6") (pinfunction "GPB5_6") (pintype "bidirectional"))
      (node (ref "MOS3") (pin "5") (pinfunction "ON/~{OFF}_5") (pintype "bidirectional"))
    )
    (net (code "60") (name "MOS4_EN") (class "Default")
      (node (ref "IOE3") (pin "5") (pinfunction "GPB4_5") (pintype "bidirectional"))
      (node (ref "MOS4") (pin "5") (pinfunction "ON/~{OFF}_5") (pintype "bidirectional"))
    )
    (net (code "61") (name "MOS5_EN") (class "Default")
      (node (ref "IOE3") (pin "4") (pinfunction "GPB3_4") (pintype "bidirectional"))
      (node (ref "MOS5") (pin "5") (pinfunction "ON/~{OFF}_5") (pintype "bidirectional"))
    )
    (net (code "62") (name "MOS6_EN") (class "Default")
      (node (ref "IOE3") (pin "3") (pinfunction "GPB2_3") (pintype "bidirectional"))
      (node (ref "MOS6") (pin "5") (pinfunction "ON/~{OFF}_5") (pintype "bidirectional"))
    )
    (net (code "63") (name "MOS7_EN") (class "Default")
      (node (ref "IOE3") (pin "2") (pinfunction "GPB1_2") (pintype "bidirectional"))
      (node (ref "MOS7") (pin "5") (pinfunction "ON/~{OFF}_5") (pintype "bidirectional"))
    )
    (net (code "64") (name "MOS8_EN") (class "Default")
      (node (ref "IOE3") (pin "1") (pinfunction "GPB0_1") (pintype "bidirectional"))
      (node (ref "MOS8") (pin "5") (pinfunction "ON/~{OFF}_5") (pintype "bidirectional"))
    )
    (net (code "65") (name "MOTA1_DIR") (class "Default")
      (node (ref "JCTRL") (pin "13") (pinfunction "13_13") (pintype "bidirectional"))
      (node (ref "MOTA1") (pin "18") (pinfunction "IN2_18") (pintype "bidirectional"))
    )
    (net (code "66") (name "MOTA1_PWM") (class "Default")
      (node (ref "JCTRL") (pin "11") (pinfunction "11_11") (pintype "bidirectional"))
      (node (ref "MOTA1") (pin "19") (pinfunction "IN1_19") (pintype "bidirectional"))
    )
    (net (code "67") (name "MOTA1_SEN") (class "Default")
      (node (ref "IC2") (pin "5") (pinfunction "+IN_5") (pintype "input"))
      (node (ref "MOTA1") (pin "16") (pinfunction "SENSE_16") (pintype "bidirectional"))
    )
    (net (code "68") (name "MOTA1_~{FAULT}") (class "Default")
      (node (ref "JCTRL") (pin "12") (pinfunction "12_12") (pintype "bidirectional"))
      (node (ref "MOTA1") (pin "15") (pinfunction "~{FAULT}_15") (pintype "bidirectional"))
    )
    (net (code "69") (name "MOTA1_~{SLEEP}") (class "Default")
      (node (ref "IOE1") (pin "23") (pinfunction "GPA2_23") (pintype "bidirectional"))
      (node (ref "MOTA1") (pin "14") (pinfunction "~{SLEEP}_14") (pintype "bidirectional"))
    )
    (net (code "70") (name "MOTA2_DIR") (class "Default")
      (node (ref "JCTRL") (pin "16") (pinfunction "16_16") (pintype "bidirectional"))
      (node (ref "MOTA2") (pin "18") (pinfunction "IN2_18") (pintype "bidirectional"))
    )
    (net (code "71") (name "MOTA2_PWM") (class "Default")
      (node (ref "JCTRL") (pin "14") (pinfunction "14_14") (pintype "bidirectional"))
      (node (ref "MOTA2") (pin "19") (pinfunction "IN1_19") (pintype "bidirectional"))
    )
    (net (code "72") (name "MOTA2_SEN") (class "Default")
      (node (ref "IC2") (pin "10") (pinfunction "+IN_10") (pintype "input"))
      (node (ref "MOTA2") (pin "16") (pinfunction "SENSE_16") (pintype "bidirectional"))
    )
    (net (code "73") (name "MOTA2_~{FAULT}") (class "Default")
      (node (ref "JCTRL") (pin "15") (pinfunction "15_15") (pintype "bidirectional"))
      (node (ref "MOTA2") (pin "15") (pinfunction "~{FAULT}_15") (pintype "bidirectional"))
    )
    (net (code "74") (name "MOTA2_~{SLEEP}") (class "Default")
      (node (ref "IOE1") (pin "22") (pinfunction "GPA1_22") (pintype "bidirectional"))
      (node (ref "MOTA2") (pin "14") (pinfunction "~{SLEEP}_14") (pintype "bidirectional"))
    )
    (net (code "75") (name "MOTA3_DIR") (class "Default")
      (node (ref "JCTRL") (pin "19") (pinfunction "19_19") (pintype "bidirectional"))
      (node (ref "MOTA3") (pin "18") (pinfunction "IN2_18") (pintype "bidirectional"))
    )
    (net (code "76") (name "MOTA3_PWM") (class "Default")
      (node (ref "JCTRL") (pin "17") (pinfunction "17_17") (pintype "bidirectional"))
      (node (ref "MOTA3") (pin "19") (pinfunction "IN1_19") (pintype "bidirectional"))
    )
    (net (code "77") (name "MOTA3_SEN") (class "Default")
      (node (ref "IC2") (pin "12") (pinfunction "+IN_12") (pintype "input"))
      (node (ref "MOTA3") (pin "16") (pinfunction "SENSE_16") (pintype "bidirectional"))
    )
    (net (code "78") (name "MOTA3_~{FAULT}") (class "Default")
      (node (ref "JCTRL") (pin "18") (pinfunction "18_18") (pintype "bidirectional"))
      (node (ref "MOTA3") (pin "15") (pinfunction "~{FAULT}_15") (pintype "bidirectional"))
    )
    (net (code "79") (name "MOTA3_~{SLEEP}") (class "Default")
      (node (ref "IOE1") (pin "21") (pinfunction "GPA0_21") (pintype "bidirectional"))
      (node (ref "MOTA3") (pin "14") (pinfunction "~{SLEEP}_14") (pintype "bidirectional"))
    )
    (net (code "80") (name "MOTA_DECAY") (class "Default")
      (node (ref "MOTA1") (pin "17") (pinfunction "DECAY_17") (pintype "bidirectional"))
      (node (ref "MOTA2") (pin "17") (pinfunction "DECAY_17") (pintype "bidirectional"))
      (node (ref "MOTA3") (pin "17") (pinfunction "DECAY_17") (pintype "bidirectional"))
      (node (ref "P7") (pin "2") (pinfunction "S_2") (pintype "passive"))
    )
    (net (code "81") (name "MOTA_I0") (class "Default")
      (node (ref "IOE3") (pin "24") (pinfunction "GPA3_24") (pintype "bidirectional"))
      (node (ref "MOTA1") (pin "20") (pinfunction "I0_20") (pintype "bidirectional"))
      (node (ref "MOTA2") (pin "20") (pinfunction "I0_20") (pintype "bidirectional"))
      (node (ref "MOTA3") (pin "20") (pinfunction "I0_20") (pintype "bidirectional"))
    )
    (net (code "82") (name "MOTA_I1") (class "Default")
      (node (ref "IOE3") (pin "25") (pinfunction "GPA4_25") (pintype "bidirectional"))
      (node (ref "MOTA1") (pin "21") (pinfunction "I1_21") (pintype "bidirectional"))
      (node (ref "MOTA2") (pin "21") (pinfunction "I1_21") (pintype "bidirectional"))
      (node (ref "MOTA3") (pin "21") (pinfunction "I1_21") (pintype "bidirectional"))
    )
    (net (code "83") (name "MOTA_I2") (class "Default")
      (node (ref "IOE3") (pin "26") (pinfunction "GPA5_26") (pintype "bidirectional"))
      (node (ref "MOTA1") (pin "22") (pinfunction "I2_22") (pintype "bidirectional"))
      (node (ref "MOTA2") (pin "22") (pinfunction "I2_22") (pintype "bidirectional"))
      (node (ref "MOTA3") (pin "22") (pinfunction "I2_22") (pintype "bidirectional"))
    )
    (net (code "84") (name "MOTA_I3") (class "Default")
      (node (ref "IOE3") (pin "27") (pinfunction "GPA6_27") (pintype "bidirectional"))
      (node (ref "MOTA1") (pin "23") (pinfunction "I3_23") (pintype "bidirectional"))
      (node (ref "MOTA2") (pin "23") (pinfunction "I3_23") (pintype "bidirectional"))
      (node (ref "MOTA3") (pin "23") (pinfunction "I3_23") (pintype "bidirectional"))
    )
    (net (code "85") (name "MOTA_I4") (class "Default")
      (node (ref "IOE3") (pin "28") (pinfunction "GPA7_28") (pintype "bidirectional"))
      (node (ref "MOTA1") (pin "24") (pinfunction "I4_24") (pintype "bidirectional"))
      (node (ref "MOTA2") (pin "24") (pinfunction "I4_24") (pintype "bidirectional"))
      (node (ref "MOTA3") (pin "24") (pinfunction "I4_24") (pintype "bidirectional"))
    )
    (net (code "86") (name "MOTB1-2_DECAY") (class "Default")
      (node (ref "MOTB1-2") (pin "18") (pinfunction "DECAY_18") (pintype "bidirectional"))
      (node (ref "P8") (pin "2") (pinfunction "S_2") (pintype "passive"))
    )
    (net (code "87") (name "MOTB1-2_I0") (class "Default")
      (node (ref "IOE3") (pin "22") (pinfunction "GPA1_22") (pintype "bidirectional"))
      (node (ref "MOTB1-2") (pin "23") (pinfunction "I0_23") (pintype "bidirectional"))
    )
    (net (code "88") (name "MOTB1-2_I1") (class "Default")
      (node (ref "IOE3") (pin "21") (pinfunction "GPA0_21") (pintype "bidirectional"))
      (node (ref "MOTB1-2") (pin "24") (pinfunction "I1_24") (pintype "bidirectional"))
    )
    (net (code "89") (name "MOTB1-2_~{FAULT}") (class "Default")
      (node (ref "JCTRL") (pin "24") (pinfunction "24_24") (pintype "bidirectional"))
      (node (ref "MOTB1-2") (pin "15") (pinfunction "~{FAULT}_15") (pintype "bidirectional"))
    )
    (net (code "90") (name "MOTB1-2_~{SLEEP}") (class "Default")
      (node (ref "IOE3") (pin "23") (pinfunction "GPA2_23") (pintype "bidirectional"))
      (node (ref "MOTB1-2") (pin "14") (pinfunction "~{SLEEP}_14") (pintype "bidirectional"))
    )
    (net (code "91") (name "MOTB1_DIR") (class "Default")
      (node (ref "JCTRL") (pin "23") (pinfunction "23_23") (pintype "bidirectional"))
      (node (ref "MOTB1-2") (pin "19") (pinfunction "AIN2_19") (pintype "bidirectional"))
    )
    (net (code "92") (name "MOTB1_PWM") (class "Default")
      (node (ref "JCTRL") (pin "22") (pinfunction "22_22") (pintype "bidirectional"))
      (node (ref "MOTB1-2") (pin "20") (pinfunction "AIN1_20") (pintype "bidirectional"))
    )
    (net (code "93") (name "MOTB1_SEN") (class "Default")
      (node (ref "IC3") (pin "3") (pinfunction "+IN_3") (pintype "input"))
      (node (ref "MOTB1-2") (pin "17") (pinfunction "ISENA_17") (pintype "bidirectional"))
    )
    (net (code "94") (name "MOTB2_DIR") (class "Default")
      (node (ref "JCTRL") (pin "20") (pinfunction "20_20") (pintype "bidirectional"))
      (node (ref "MOTB1-2") (pin "22") (pinfunction "BIN2_22") (pintype "bidirectional"))
    )
    (net (code "95") (name "MOTB2_PWM") (class "Default")
      (node (ref "JCTRL") (pin "21") (pinfunction "21_21") (pintype "bidirectional"))
      (node (ref "MOTB1-2") (pin "21") (pinfunction "BIN1_21") (pintype "bidirectional"))
    )
    (net (code "96") (name "MOTB2_SEN") (class "Default")
      (node (ref "IC3") (pin "5") (pinfunction "+IN_5") (pintype "input"))
      (node (ref "MOTB1-2") (pin "16") (pinfunction "ISENB_16") (pintype "bidirectional"))
    )
    (net (code "97") (name "MOTB3-4_DECAY") (class "Default")
      (node (ref "MOTB3-4") (pin "18") (pinfunction "DECAY_18") (pintype "bidirectional"))
      (node (ref "P9") (pin "2") (pinfunction "S_2") (pintype "passive"))
    )
    (net (code "98") (name "MOTB3-4_I0") (class "Default")
      (node (ref "IOE2") (pin "28") (pinfunction "GPA7_28") (pintype "bidirectional"))
      (node (ref "MOTB3-4") (pin "23") (pinfunction "I0_23") (pintype "bidirectional"))
    )
    (net (code "99") (name "MOTB3-4_I1") (class "Default")
      (node (ref "IOE2") (pin "1") (pinfunction "GPB0_1") (pintype "bidirectional"))
      (node (ref "MOTB3-4") (pin "24") (pinfunction "I1_24") (pintype "bidirectional"))
    )
    (net (code "100") (name "MOTB3-4_~{FAULT}") (class "Default")
      (node (ref "JCTRL") (pin "31") (pinfunction "31_31") (pintype "bidirectional"))
      (node (ref "MOTB3-4") (pin "15") (pinfunction "~{FAULT}_15") (pintype "bidirectional"))
    )
    (net (code "101") (name "MOTB3-4_~{SLEEP}") (class "Default")
      (node (ref "IOE2") (pin "27") (pinfunction "GPA6_27") (pintype "bidirectional"))
      (node (ref "MOTB3-4") (pin "14") (pinfunction "~{SLEEP}_14") (pintype "bidirectional"))
    )
    (net (code "102") (name "MOTB3_DIR") (class "Default")
      (node (ref "JCTRL") (pin "28") (pinfunction "28_28") (pintype "bidirectional"))
      (node (ref "MOTB3-4") (pin "19") (pinfunction "AIN2_19") (pintype "bidirectional"))
    )
    (net (code "103") (name "MOTB3_PWM") (class "Default")
      (node (ref "JCTRL") (pin "27") (pinfunction "27_27") (pintype "bidirectional"))
      (node (ref "MOTB3-4") (pin "20") (pinfunction "AIN1_20") (pintype "bidirectional"))
    )
    (net (code "104") (name "MOTB3_SEN") (class "Default")
      (node (ref "IC3") (pin "12") (pinfunction "+IN_12") (pintype "input"))
      (node (ref "MOTB3-4") (pin "17") (pinfunction "ISENA_17") (pintype "bidirectional"))
    )
    (net (code "105") (name "MOTB4_DIR") (class "Default")
      (node (ref "JCTRL") (pin "25") (pinfunction "25_25") (pintype "bidirectional"))
      (node (ref "MOTB3-4") (pin "22") (pinfunction "BIN2_22") (pintype "bidirectional"))
    )
    (net (code "106") (name "MOTB4_PWM") (class "Default")
      (node (ref "JCTRL") (pin "26") (pinfunction "26_26") (pintype "bidirectional"))
      (node (ref "MOTB3-4") (pin "21") (pinfunction "BIN1_21") (pintype "bidirectional"))
    )
    (net (code "107") (name "MOTB4_SEN") (class "Default")
      (node (ref "IC3") (pin "10") (pinfunction "+IN_10") (pintype "input"))
      (node (ref "MOTB3-4") (pin "16") (pinfunction "ISENB_16") (pintype "bidirectional"))
    )
    (net (code "108") (name "MOTB5-6_DECAY") (class "Default")
      (node (ref "MOTB5-6") (pin "18") (pinfunction "DECAY_18") (pintype "bidirectional"))
      (node (ref "P10") (pin "2") (pinfunction "S_2") (pintype "passive"))
    )
    (net (code "109") (name "MOTB5-6_I0") (class "Default")
      (node (ref "IOE2") (pin "25") (pinfunction "GPA4_25") (pintype "bidirectional"))
      (node (ref "MOTB5-6") (pin "23") (pinfunction "I0_23") (pintype "bidirectional"))
    )
    (net (code "110") (name "MOTB5-6_I1") (class "Default")
      (node (ref "IOE2") (pin "26") (pinfunction "GPA5_26") (pintype "bidirectional"))
      (node (ref "MOTB5-6") (pin "24") (pinfunction "I1_24") (pintype "bidirectional"))
    )
    (net (code "111") (name "MOTB5-6_~{FAULT}") (class "Default")
      (node (ref "JCTRL") (pin "34") (pinfunction "34_34") (pintype "bidirectional"))
      (node (ref "MOTB5-6") (pin "15") (pinfunction "~{FAULT}_15") (pintype "bidirectional"))
    )
    (net (code "112") (name "MOTB5-6_~{SLEEP}") (class "Default")
      (node (ref "IOE2") (pin "24") (pinfunction "GPA3_24") (pintype "bidirectional"))
      (node (ref "MOTB5-6") (pin "14") (pinfunction "~{SLEEP}_14") (pintype "bidirectional"))
    )
    (net (code "113") (name "MOTB5_DIR") (class "Default")
      (node (ref "JCTRL") (pin "33") (pinfunction "33_33") (pintype "bidirectional"))
      (node (ref "MOTB5-6") (pin "19") (pinfunction "AIN2_19") (pintype "bidirectional"))
    )
    (net (code "114") (name "MOTB5_PWM") (class "Default")
      (node (ref "JCTRL") (pin "29") (pinfunction "29_29") (pintype "bidirectional"))
      (node (ref "MOTB5-6") (pin "20") (pinfunction "AIN1_20") (pintype "bidirectional"))
    )
    (net (code "115") (name "MOTB5_SEN") (class "Default")
      (node (ref "IC4") (pin "3") (pinfunction "+IN_3") (pintype "input"))
      (node (ref "MOTB5-6") (pin "17") (pinfunction "ISENA_17") (pintype "bidirectional"))
    )
    (net (code "116") (name "MOTB6_DIR") (class "Default")
      (node (ref "JCTRL") (pin "32") (pinfunction "32_32") (pintype "bidirectional"))
      (node (ref "MOTB5-6") (pin "22") (pinfunction "BIN2_22") (pintype "bidirectional"))
    )
    (net (code "117") (name "MOTB6_PWM") (class "Default")
      (node (ref "JCTRL") (pin "30") (pinfunction "30_30") (pintype "bidirectional"))
      (node (ref "MOTB5-6") (pin "21") (pinfunction "BIN1_21") (pintype "bidirectional"))
    )
    (net (code "118") (name "MOTB6_SEN") (class "Default")
      (node (ref "IC4") (pin "5") (pinfunction "+IN_5") (pintype "input"))
      (node (ref "MOTB5-6") (pin "16") (pinfunction "ISENB_16") (pintype "bidirectional"))
    )
    (net (code "119") (name "MOTB7-8_DECAY") (class "Default")
      (node (ref "MOTB7-8") (pin "18") (pinfunction "DECAY_18") (pintype "bidirectional"))
      (node (ref "P11") (pin "2") (pinfunction "S_2") (pintype "passive"))
    )
    (net (code "120") (name "MOTB7-8_I0") (class "Default")
      (node (ref "IOE2") (pin "22") (pinfunction "GPA1_22") (pintype "bidirectional"))
      (node (ref "MOTB7-8") (pin "23") (pinfunction "I0_23") (pintype "bidirectional"))
    )
    (net (code "121") (name "MOTB7-8_I1") (class "Default")
      (node (ref "IOE2") (pin "21") (pinfunction "GPA0_21") (pintype "bidirectional"))
      (node (ref "MOTB7-8") (pin "24") (pinfunction "I1_24") (pintype "bidirectional"))
    )
    (net (code "122") (name "MOTB7-8_~{FAULT}") (class "Default")
      (node (ref "JCTRL") (pin "39") (pinfunction "39_39") (pintype "bidirectional"))
      (node (ref "MOTB7-8") (pin "15") (pinfunction "~{FAULT}_15") (pintype "bidirectional"))
    )
    (net (code "123") (name "MOTB7-8_~{SLEEP}") (class "Default")
      (node (ref "IOE2") (pin "23") (pinfunction "GPA2_23") (pintype "bidirectional"))
      (node (ref "MOTB7-8") (pin "14") (pinfunction "~{SLEEP}_14") (pintype "bidirectional"))
    )
    (net (code "124") (name "MOTB7_DIR") (class "Default")
      (node (ref "JCTRL") (pin "38") (pinfunction "38_38") (pintype "bidirectional"))
      (node (ref "MOTB7-8") (pin "19") (pinfunction "AIN2_19") (pintype "bidirectional"))
    )
    (net (code "125") (name "MOTB7_PWM") (class "Default")
      (node (ref "JCTRL") (pin "37") (pinfunction "37_37") (pintype "bidirectional"))
      (node (ref "MOTB7-8") (pin "20") (pinfunction "AIN1_20") (pintype "bidirectional"))
    )
    (net (code "126") (name "MOTB7_SEN") (class "Default")
      (node (ref "IC4") (pin "12") (pinfunction "+IN_12") (pintype "input"))
      (node (ref "MOTB7-8") (pin "17") (pinfunction "ISENA_17") (pintype "bidirectional"))
    )
    (net (code "127") (name "MOTB8_DIR") (class "Default")
      (node (ref "JCTRL") (pin "35") (pinfunction "35_35") (pintype "bidirectional"))
      (node (ref "MOTB7-8") (pin "22") (pinfunction "BIN2_22") (pintype "bidirectional"))
    )
    (net (code "128") (name "MOTB8_PWM") (class "Default")
      (node (ref "JCTRL") (pin "36") (pinfunction "36_36") (pintype "bidirectional"))
      (node (ref "MOTB7-8") (pin "21") (pinfunction "BIN1_21") (pintype "bidirectional"))
    )
    (net (code "129") (name "MOTB8_SEN") (class "Default")
      (node (ref "IC4") (pin "10") (pinfunction "+IN_10") (pintype "input"))
      (node (ref "MOTB7-8") (pin "16") (pinfunction "ISENB_16") (pintype "bidirectional"))
    )
    (net (code "130") (name "MOT_~{RESET}") (class "Default")
      (node (ref "JCTRL") (pin "2") (pinfunction "2_2") (pintype "bidirectional"))
      (node (ref "MOTA1") (pin "13") (pinfunction "~{RESET}_13") (pintype "bidirectional"))
      (node (ref "MOTA2") (pin "13") (pinfunction "~{RESET}_13") (pintype "bidirectional"))
      (node (ref "MOTA3") (pin "13") (pinfunction "~{RESET}_13") (pintype "bidirectional"))
      (node (ref "MOTB1-2") (pin "13") (pinfunction "~{RESET}_13") (pintype "bidirectional"))
      (node (ref "MOTB3-4") (pin "13") (pinfunction "~{RESET}_13") (pintype "bidirectional"))
      (node (ref "MOTB5-6") (pin "13") (pinfunction "~{RESET}_13") (pintype "bidirectional"))
      (node (ref "MOTB7-8") (pin "13") (pinfunction "~{RESET}_13") (pintype "bidirectional"))
    )
    (net (code "131") (name "Net-(ASV1-Pad1)") (class "Default")
      (node (ref "ASV1") (pin "1") (pinfunction "1_1") (pintype "bidirectional"))
      (node (ref "RS3") (pin "2") (pinfunction "2_2") (pintype "passive"))
    )
    (net (code "132") (name "Net-(ASV2-Pad1)") (class "Default")
      (node (ref "ASV2") (pin "1") (pinfunction "1_1") (pintype "bidirectional"))
      (node (ref "RS5") (pin "2") (pinfunction "2_2") (pintype "passive"))
    )
    (net (code "133") (name "Net-(ASV3-Pad1)") (class "Default")
      (node (ref "ASV3") (pin "1") (pinfunction "1_1") (pintype "bidirectional"))
      (node (ref "RS7") (pin "2") (pinfunction "2_2") (pintype "passive"))
    )
    (net (code "134") (name "Net-(ASV4-Pad1)") (class "Default")
      (node (ref "ASV4") (pin "1") (pinfunction "1_1") (pintype "bidirectional"))
      (node (ref "RS9") (pin "2") (pinfunction "2_2") (pintype "passive"))
    )
    (net (code "135") (name "Net-(ASV5-Pad1)") (class "Default")
      (node (ref "ASV5") (pin "1") (pinfunction "1_1") (pintype "bidirectional"))
      (node (ref "RS11") (pin "2") (pinfunction "2_2") (pintype "passive"))
    )
    (net (code "136") (name "Net-(ASV6-Pad1)") (class "Default")
      (node (ref "ASV6") (pin "1") (pinfunction "1_1") (pintype "bidirectional"))
      (node (ref "RS13") (pin "2") (pinfunction "2_2") (pintype "passive"))
    )
    (net (code "137") (name "Net-(ASV7-Pad1)") (class "Default")
      (node (ref "ASV7") (pin "1") (pinfunction "1_1") (pintype "bidirectional"))
      (node (ref "RS15") (pin "2") (pinfunction "2_2") (pintype "passive"))
    )
    (net (code "138") (name "Net-(ASV8-Pad1)") (class "Default")
      (node (ref "ASV8") (pin "1") (pinfunction "1_1") (pintype "bidirectional"))
      (node (ref "RS17") (pin "2") (pinfunction "2_2") (pintype "passive"))
    )
    (net (code "139") (name "Net-(C6-Pad2)") (class "Default")
      (node (ref "C6") (pin "2") (pinfunction "2_2") (pintype "passive"))
      (node (ref "C7") (pin "1") (pinfunction "1_1") (pintype "passive"))
      (node (ref "JM2") (pin "1") (pinfunction "1_1") (pintype "bidirectional"))
      (node (ref "MOS2") (pin "2") (pinfunction "VOUT,C1_2") (pintype "bidirectional"))
      (node (ref "MOS2") (pin "3") (pinfunction "VOUT,C1_3") (pintype "bidirectional"))
    )
    (net (code "140") (name "Net-(C8-Pad2)") (class "Default")
      (node (ref "C8") (pin "2") (pinfunction "2_2") (pintype "passive"))
      (node (ref "C9") (pin "1") (pinfunction "1_1") (pintype "passive"))
      (node (ref "JM3") (pin "1") (pinfunction "1_1") (pintype "bidirectional"))
      (node (ref "MOS3") (pin "2") (pinfunction "VOUT,C1_2") (pintype "bidirectional"))
      (node (ref "MOS3") (pin "3") (pinfunction "VOUT,C1_3") (pintype "bidirectional"))
    )
    (net (code "141") (name "Net-(C10-Pad2)") (class "Default")
      (node (ref "C10") (pin "2") (pinfunction "2_2") (pintype "passive"))
      (node (ref "C11") (pin "1") (pinfunction "1_1") (pintype "passive"))
      (node (ref "JM4") (pin "1") (pinfunction "1_1") (pintype "bidirectional"))
      (node (ref "MOS4") (pin "2") (pinfunction "VOUT,C1_2") (pintype "bidirectional"))
      (node (ref "MOS4") (pin "3") (pinfunction "VOUT,C1_3") (pintype "bidirectional"))
    )
    (net (code "142") (name "Net-(C27-Pad1)") (class "Default")
      (node (ref "C27") (pin "1") (pinfunction "1_1") (pintype "passive"))
      (node (ref "C5") (pin "2") (pinfunction "2_2") (pintype "passive"))
      (node (ref "JM5") (pin "1") (pinfunction "1_1") (pintype "bidirectional"))
      (node (ref "MOS5") (pin "2") (pinfunction "VOUT,C1_2") (pintype "bidirectional"))
      (node (ref "MOS5") (pin "3") (pinfunction "VOUT,C1_3") (pintype "bidirectional"))
    )
    (net (code "143") (name "Net-(C28-Pad2)") (class "Default")
      (node (ref "C28") (pin "2") (pinfunction "2_2") (pintype "passive"))
      (node (ref "C29") (pin "1") (pinfunction "1_1") (pintype "passive"))
      (node (ref "JM6") (pin "1") (pinfunction "1_1") (pintype "bidirectional"))
      (node (ref "MOS6") (pin "2") (pinfunction "VOUT,C1_2") (pintype "bidirectional"))
      (node (ref "MOS6") (pin "3") (pinfunction "VOUT,C1_3") (pintype "bidirectional"))
    )
    (net (code "144") (name "Net-(C30-Pad2)") (class "Default")
      (node (ref "C30") (pin "2") (pinfunction "2_2") (pintype "passive"))
      (node (ref "C31") (pin "1") (pinfunction "1_1") (pintype "passive"))
      (node (ref "JM7") (pin "1") (pinfunction "1_1") (pintype "bidirectional"))
      (node (ref "MOS7") (pin "2") (pinfunction "VOUT,C1_2") (pintype "bidirectional"))
      (node (ref "MOS7") (pin "3") (pinfunction "VOUT,C1_3") (pintype "bidirectional"))
    )
    (net (code "145") (name "Net-(C32-Pad2)") (class "Default")
      (node (ref "C32") (pin "2") (pinfunction "2_2") (pintype "passive"))
      (node (ref "C33") (pin "1") (pinfunction "1_1") (pintype "passive"))
      (node (ref "JM8") (pin "1") (pinfunction "1_1") (pintype "bidirectional"))
      (node (ref "MOS8") (pin "2") (pinfunction "VOUT,C1_2") (pintype "bidirectional"))
      (node (ref "MOS8") (pin "3") (pinfunction "VOUT,C1_3") (pintype "bidirectional"))
    )
    (net (code "146") (name "Net-(C40-Pad2)") (class "Default")
      (node (ref "C40") (pin "2") (pinfunction "2_2") (pintype "passive"))
      (node (ref "C41") (pin "1") (pinfunction "1_1") (pintype "passive"))
      (node (ref "JM1") (pin "1") (pinfunction "1_1") (pintype "bidirectional"))
      (node (ref "MOS1") (pin "2") (pinfunction "VOUT,C1_2") (pintype "bidirectional"))
      (node (ref "MOS1") (pin "3") (pinfunction "VOUT,C1_3") (pintype "bidirectional"))
    )
    (net (code "147") (name "Net-(CEL1-IN+)") (class "Default")
      (node (ref "C47") (pin "2") (pinfunction "2_2") (pintype "passive"))
      (node (ref "C49") (pin "1") (pinfunction "1_1") (pintype "passive"))
      (node (ref "CEL1") (pin "3") (pinfunction "IN+_3") (pintype "bidirectional"))
      (node (ref "CEL2") (pin "2") (pinfunction "IN-_2") (pintype "bidirectional"))
      (node (ref "J1") (pin "2") (pinfunction "2_2") (pintype "bidirectional"))
      (node (ref "R58") (pin "1") (pinfunction "1_1") (pintype "passive"))
      (node (ref "R61") (pin "2") (pinfunction "2_2") (pintype "passive"))
    )
    (net (code "148") (name "Net-(CEL1-IN-)") (class "Default")
      (node (ref "C47") (pin "1") (pinfunction "1_1") (pintype "passive"))
      (node (ref "CEL1") (pin "2") (pinfunction "IN-_2") (pintype "bidirectional"))
      (node (ref "J1") (pin "1") (pinfunction "1_1") (pintype "bidirectional"))
      (node (ref "R58") (pin "2") (pinfunction "2_2") (pintype "passive"))
    )
    (net (code "149") (name "Net-(CEL1-OUT)") (class "Default")
      (node (ref "CEL1") (pin "6") (pinfunction "OUT_6") (pintype "bidirectional"))
      (node (ref "R78") (pin "1") (pinfunction "1_1") (pintype "passive"))
    )
    (net (code "150") (name "Net-(CEL2-IN+)") (class "Default")
      (node (ref "C49") (pin "2") (pinfunction "2_2") (pintype "passive"))
      (node (ref "C51") (pin "1") (pinfunction "1_1") (pintype "passive"))
      (node (ref "CEL2") (pin "3") (pinfunction "IN+_3") (pintype "bidirectional"))
      (node (ref "CEL3") (pin "2") (pinfunction "IN-_2") (pintype "bidirectional"))
      (node (ref "J1") (pin "3") (pinfunction "3_3") (pintype "bidirectional"))
      (node (ref "R61") (pin "1") (pinfunction "1_1") (pintype "passive"))
      (node (ref "R64") (pin "2") (pinfunction "2_2") (pintype "passive"))
    )
    (net (code "151") (name "Net-(CEL2-OUT)") (class "Default")
      (node (ref "CEL2") (pin "6") (pinfunction "OUT_6") (pintype "bidirectional"))
      (node (ref "R59") (pin "1") (pinfunction "1_1") (pintype "passive"))
    )
    (net (code "152") (name "Net-(CEL3-IN+)") (class "Default")
      (node (ref "C51") (pin "2") (pinfunction "2_2") (pintype "passive"))
      (node (ref "C53") (pin "1") (pinfunction "1_1") (pintype "passive"))
      (node (ref "CEL3") (pin "3") (pinfunction "IN+_3") (pintype "bidirectional"))
      (node (ref "CEL4") (pin "2") (pinfunction "IN-_2") (pintype "bidirectional"))
      (node (ref "J1") (pin "4") (pinfunction "4_4") (pintype "bidirectional"))
      (node (ref "R64") (pin "1") (pinfunction "1_1") (pintype "passive"))
      (node (ref "R67") (pin "2") (pinfunction "2_2") (pintype "passive"))
    )
    (net (code "153") (name "Net-(CEL3-OUT)") (class "Default")
      (node (ref "CEL3") (pin "6") (pinfunction "OUT_6") (pintype "bidirectional"))
      (node (ref "R62") (pin "1") (pinfunction "1_1") (pintype "passive"))
    )
    (net (code "154") (name "Net-(CEL4-IN+)") (class "Default")
      (node (ref "C53") (pin "2") (pinfunction "2_2") (pintype "passive"))
      (node (ref "C55") (pin "1") (pinfunction "1_1") (pintype "passive"))
      (node (ref "CEL4") (pin "3") (pinfunction "IN+_3") (pintype "bidirectional"))
      (node (ref "CEL5") (pin "2") (pinfunction "IN-_2") (pintype "bidirectional"))
      (node (ref "J1") (pin "5") (pinfunction "5_5") (pintype "bidirectional"))
      (node (ref "R67") (pin "1") (pinfunction "1_1") (pintype "passive"))
      (node (ref "R70") (pin "2") (pinfunction "2_2") (pintype "passive"))
    )
    (net (code "155") (name "Net-(CEL4-OUT)") (class "Default")
      (node (ref "CEL4") (pin "6") (pinfunction "OUT_6") (pintype "bidirectional"))
      (node (ref "R65") (pin "1") (pinfunction "1_1") (pintype "passive"))
    )
    (net (code "156") (name "Net-(CEL5-IN+)") (class "Default")
      (node (ref "C55") (pin "2") (pinfunction "2_2") (pintype "passive"))
      (node (ref "C57") (pin "1") (pinfunction "1_1") (pintype "passive"))
      (node (ref "CEL5") (pin "3") (pinfunction "IN+_3") (pintype "bidirectional"))
      (node (ref "CEL6") (pin "2") (pinfunction "IN-_2") (pintype "bidirectional"))
      (node (ref "J1") (pin "6") (pinfunction "6_6") (pintype "bidirectional"))
      (node (ref "R70") (pin "1") (pinfunction "1_1") (pintype "passive"))
      (node (ref "R73") (pin "2") (pinfunction "2_2") (pintype "passive"))
    )
    (net (code "157") (name "Net-(CEL5-OUT)") (class "Default")
      (node (ref "CEL5") (pin "6") (pinfunction "OUT_6") (pintype "bidirectional"))
      (node (ref "R68") (pin "1") (pinfunction "1_1") (pintype "passive"))
    )
    (net (code "158") (name "Net-(CEL6-IN+)") (class "Default")
      (node (ref "C57") (pin "2") (pinfunction "2_2") (pintype "passive"))
      (node (ref "CEL6") (pin "3") (pinfunction "IN+_3") (pintype "bidirectional"))
      (node (ref "J1") (pin "7") (pinfunction "7_7") (pintype "bidirectional"))
      (node (ref "R73") (pin "1") (pinfunction "1_1") (pintype "passive"))
    )
    (net (code "159") (name "Net-(CEL6-OUT)") (class "Default")
      (node (ref "CEL6") (pin "6") (pinfunction "OUT_6") (pintype "bidirectional"))
      (node (ref "R71") (pin "1") (pinfunction "1_1") (pintype "passive"))
    )
    (net (code "160") (name "Net-(IC1A--IN)") (class "Default")
      (node (ref "IC1") (pin "1") (pinfunction "OUT_1") (pintype "output"))
      (node (ref "IC1") (pin "2") (pinfunction "-IN_2") (pintype "input"))
      (node (ref "R86") (pin "1") (pinfunction "1_1") (pintype "passive"))
    )
    (net (code "161") (name "Net-(IC1B--IN)") (class "Default")
      (node (ref "IC1") (pin "6") (pinfunction "-IN_6") (pintype "input"))
      (node (ref "IC1") (pin "7") (pinfunction "OUT_7") (pintype "output"))
      (node (ref "R87") (pin "1") (pinfunction "1_1") (pintype "passive"))
    )
    (net (code "162") (name "Net-(IC1C--IN)") (class "Default")
      (node (ref "IC1") (pin "8") (pinfunction "OUT_8") (pintype "output"))
      (node (ref "IC1") (pin "9") (pinfunction "-IN_9") (pintype "input"))
      (node (ref "R88") (pin "1") (pinfunction "1_1") (pintype "passive"))
    )
    (net (code "163") (name "Net-(IC1D--IN)") (class "Default")
      (node (ref "IC1") (pin "13") (pinfunction "-IN_13") (pintype "input"))
      (node (ref "IC1") (pin "14") (pinfunction "OUT_14") (pintype "output"))
      (node (ref "R89") (pin "1") (pinfunction "1_1") (pintype "passive"))
    )
    (net (code "164") (name "Net-(IC2A--IN)") (class "Default")
      (node (ref "IC2") (pin "1") (pinfunction "OUT_1") (pintype "output"))
      (node (ref "IC2") (pin "2") (pinfunction "-IN_2") (pintype "input"))
      (node (ref "R92") (pin "1") (pinfunction "1_1") (pintype "passive"))
    )
    (net (code "165") (name "Net-(IC2B--IN)") (class "Default")
      (node (ref "IC2") (pin "6") (pinfunction "-IN_6") (pintype "input"))
      (node (ref "R93") (pin "1") (pinfunction "1_1") (pintype "passive"))
      (node (ref "R94") (pin "2") (pinfunction "2_2") (pintype "passive"))
    )
    (net (code "166") (name "Net-(IC2B-OUT)") (class "Default")
      (node (ref "IC2") (pin "7") (pinfunction "OUT_7") (pintype "output"))
      (node (ref "R93") (pin "2") (pinfunction "2_2") (pintype "passive"))
      (node (ref "R99") (pin "1") (pinfunction "1_1") (pintype "passive"))
    )
    (net (code "167") (name "Net-(IC2C--IN)") (class "Default")
      (node (ref "IC2") (pin "9") (pinfunction "-IN_9") (pintype "input"))
      (node (ref "R95") (pin "2") (pinfunction "2_2") (pintype "passive"))
      (node (ref "R96") (pin "1") (pinfunction "1_1") (pintype "passive"))
    )
    (net (code "168") (name "Net-(IC2C-OUT)") (class "Default")
      (node (ref "IC2") (pin "8") (pinfunction "OUT_8") (pintype "output"))
      (node (ref "R100") (pin "1") (pinfunction "1_1") (pintype "passive"))
      (node (ref "R96") (pin "2") (pinfunction "2_2") (pintype "passive"))
    )
    (net (code "169") (name "Net-(IC2D--IN)") (class "Default")
      (node (ref "IC2") (pin "13") (pinfunction "-IN_13") (pintype "input"))
      (node (ref "R97") (pin "2") (pinfunction "2_2") (pintype "passive"))
      (node (ref "R98") (pin "1") (pinfunction "1_1") (pintype "passive"))
    )
    (net (code "170") (name "Net-(IC2D-OUT)") (class "Default")
      (node (ref "IC2") (pin "14") (pinfunction "OUT_14") (pintype "output"))
      (node (ref "R101") (pin "1") (pinfunction "1_1") (pintype "passive"))
      (node (ref "R98") (pin "2") (pinfunction "2_2") (pintype "passive"))
    )
    (net (code "171") (name "Net-(IC3A--IN)") (class "Default")
      (node (ref "IC3") (pin "2") (pinfunction "-IN_2") (pintype "input"))
      (node (ref "R1") (pin "1") (pinfunction "1_1") (pintype "passive"))
      (node (ref "R3") (pin "2") (pinfunction "2_2") (pintype "passive"))
    )
    (net (code "172") (name "Net-(IC3A-OUT)") (class "Default")
      (node (ref "IC3") (pin "1") (pinfunction "OUT_1") (pintype "output"))
      (node (ref "R1") (pin "2") (pinfunction "2_2") (pintype "passive"))
      (node (ref "R102") (pin "1") (pinfunction "1_1") (pintype "passive"))
    )
    (net (code "173") (name "Net-(IC3B--IN)") (class "Default")
      (node (ref "IC3") (pin "6") (pinfunction "-IN_6") (pintype "input"))
      (node (ref "R103") (pin "1") (pinfunction "1_1") (pintype "passive"))
      (node (ref "R104") (pin "2") (pinfunction "2_2") (pintype "passive"))
    )
    (net (code "174") (name "Net-(IC3B-OUT)") (class "Default")
      (node (ref "IC3") (pin "7") (pinfunction "OUT_7") (pintype "output"))
      (node (ref "R103") (pin "2") (pinfunction "2_2") (pintype "passive"))
      (node (ref "R109") (pin "1") (pinfunction "1_1") (pintype "passive"))
    )
    (net (code "175") (name "Net-(IC3C--IN)") (class "Default")
      (node (ref "IC3") (pin "9") (pinfunction "-IN_9") (pintype "input"))
      (node (ref "R105") (pin "2") (pinfunction "2_2") (pintype "passive"))
      (node (ref "R106") (pin "1") (pinfunction "1_1") (pintype "passive"))
    )
    (net (code "176") (name "Net-(IC3C-OUT)") (class "Default")
      (node (ref "IC3") (pin "8") (pinfunction "OUT_8") (pintype "output"))
      (node (ref "R106") (pin "2") (pinfunction "2_2") (pintype "passive"))
      (node (ref "R110") (pin "1") (pinfunction "1_1") (pintype "passive"))
    )
    (net (code "177") (name "Net-(IC3D--IN)") (class "Default")
      (node (ref "IC3") (pin "13") (pinfunction "-IN_13") (pintype "input"))
      (node (ref "R107") (pin "2") (pinfunction "2_2") (pintype "passive"))
      (node (ref "R108") (pin "1") (pinfunction "1_1") (pintype "passive"))
    )
    (net (code "178") (name "Net-(IC3D-OUT)") (class "Default")
      (node (ref "IC3") (pin "14") (pinfunction "OUT_14") (pintype "output"))
      (node (ref "R108") (pin "2") (pinfunction "2_2") (pintype "passive"))
      (node (ref "R111") (pin "1") (pinfunction "1_1") (pintype "passive"))
    )
    (net (code "179") (name "Net-(IC4A--IN)") (class "Default")
      (node (ref "IC4") (pin "2") (pinfunction "-IN_2") (pintype "input"))
      (node (ref "R2") (pin "1") (pinfunction "1_1") (pintype "passive"))
      (node (ref "R9") (pin "2") (pinfunction "2_2") (pintype "passive"))
    )
    (net (code "180") (name "Net-(IC4A-OUT)") (class "Default")
      (node (ref "IC4") (pin "1") (pinfunction "OUT_1") (pintype "output"))
      (node (ref "R112") (pin "1") (pinfunction "1_1") (pintype "passive"))
      (node (ref "R2") (pin "2") (pinfunction "2_2") (pintype "passive"))
    )
    (net (code "181") (name "Net-(IC4B--IN)") (class "Default")
      (node (ref "IC4") (pin "6") (pinfunction "-IN_6") (pintype "input"))
      (node (ref "R113") (pin "1") (pinfunction "1_1") (pintype "passive"))
      (node (ref "R114") (pin "2") (pinfunction "2_2") (pintype "passive"))
    )
    (net (code "182") (name "Net-(IC4B-OUT)") (class "Default")
      (node (ref "IC4") (pin "7") (pinfunction "OUT_7") (pintype "output"))
      (node (ref "R113") (pin "2") (pinfunction "2_2") (pintype "passive"))
      (node (ref "R119") (pin "1") (pinfunction "1_1") (pintype "passive"))
    )
    (net (code "183") (name "Net-(IC4C--IN)") (class "Default")
      (node (ref "IC4") (pin "9") (pinfunction "-IN_9") (pintype "input"))
      (node (ref "R115") (pin "2") (pinfunction "2_2") (pintype "passive"))
      (node (ref "R116") (pin "1") (pinfunction "1_1") (pintype "passive"))
    )
    (net (code "184") (name "Net-(IC4C-OUT)") (class "Default")
      (node (ref "IC4") (pin "8") (pinfunction "OUT_8") (pintype "output"))
      (node (ref "R116") (pin "2") (pinfunction "2_2") (pintype "passive"))
      (node (ref "R120") (pin "1") (pinfunction "1_1") (pintype "passive"))
    )
    (net (code "185") (name "Net-(IC4D--IN)") (class "Default")
      (node (ref "IC4") (pin "13") (pinfunction "-IN_13") (pintype "input"))
      (node (ref "R117") (pin "2") (pinfunction "2_2") (pintype "passive"))
      (node (ref "R118") (pin "1") (pinfunction "1_1") (pintype "passive"))
    )
    (net (code "186") (name "Net-(IC4D-OUT)") (class "Default")
      (node (ref "IC4") (pin "14") (pinfunction "OUT_14") (pintype "output"))
      (node (ref "R118") (pin "2") (pinfunction "2_2") (pintype "passive"))
      (node (ref "R121") (pin "1") (pinfunction "1_1") (pintype "passive"))
    )
    (net (code "187") (name "Net-(JA1-Pad1)") (class "Default")
      (node (ref "JA1") (pin "1") (pinfunction "1_1") (pintype "bidirectional"))
      (node (ref "MOTA1") (pin "4") (pinfunction "OUT2_4") (pintype "bidirectional"))
      (node (ref "MOTA1") (pin "5") (pinfunction "OUT2_5") (pintype "bidirectional"))
      (node (ref "MOTA1") (pin "6") (pinfunction "OUT2_6") (pintype "bidirectional"))
    )
    (net (code "188") (name "Net-(JA1-Pad2)") (class "Default")
      (node (ref "JA1") (pin "2") (pinfunction "2_2") (pintype "bidirectional"))
      (node (ref "MOTA1") (pin "7") (pinfunction "OUT1_7") (pintype "bidirectional"))
      (node (ref "MOTA1") (pin "8") (pinfunction "OUT1_8") (pintype "bidirectional"))
      (node (ref "MOTA1") (pin "9") (pinfunction "OUT1_9") (pintype "bidirectional"))
    )
    (net (code "189") (name "Net-(JA2-Pad1)") (class "Default")
      (node (ref "JA2") (pin "1") (pinfunction "1_1") (pintype "bidirectional"))
      (node (ref "MOTA2") (pin "4") (pinfunction "OUT2_4") (pintype "bidirectional"))
      (node (ref "MOTA2") (pin "5") (pinfunction "OUT2_5") (pintype "bidirectional"))
      (node (ref "MOTA2") (pin "6") (pinfunction "OUT2_6") (pintype "bidirectional"))
    )
    (net (code "190") (name "Net-(JA2-Pad2)") (class "Default")
      (node (ref "JA2") (pin "2") (pinfunction "2_2") (pintype "bidirectional"))
      (node (ref "MOTA2") (pin "7") (pinfunction "OUT1_7") (pintype "bidirectional"))
      (node (ref "MOTA2") (pin "8") (pinfunction "OUT1_8") (pintype "bidirectional"))
      (node (ref "MOTA2") (pin "9") (pinfunction "OUT1_9") (pintype "bidirectional"))
    )
    (net (code "191") (name "Net-(JA3-Pad1)") (class "Default")
      (node (ref "JA3") (pin "1") (pinfunction "1_1") (pintype "bidirectional"))
      (node (ref "MOTA3") (pin "4") (pinfunction "OUT2_4") (pintype "bidirectional"))
      (node (ref "MOTA3") (pin "5") (pinfunction "OUT2_5") (pintype "bidirectional"))
      (node (ref "MOTA3") (pin "6") (pinfunction "OUT2_6") (pintype "bidirectional"))
    )
    (net (code "192") (name "Net-(JA3-Pad2)") (class "Default")
      (node (ref "JA3") (pin "2") (pinfunction "2_2") (pintype "bidirectional"))
      (node (ref "MOTA3") (pin "7") (pinfunction "OUT1_7") (pintype "bidirectional"))
      (node (ref "MOTA3") (pin "8") (pinfunction "OUT1_8") (pintype "bidirectional"))
      (node (ref "MOTA3") (pin "9") (pinfunction "OUT1_9") (pintype "bidirectional"))
    )
    (net (code "193") (name "Net-(JB1-Pad1)") (class "Default")
      (node (ref "JB1") (pin "1") (pinfunction "1_1") (pintype "bidirectional"))
      (node (ref "MOTB1-2") (pin "3") (pinfunction "AOUT1_3") (pintype "bidirectional"))
      (node (ref "MOTB1-2") (pin "4") (pinfunction "AOUT1_4") (pintype "bidirectional"))
    )
    (net (code "194") (name "Net-(JB1-Pad2)") (class "Default")
      (node (ref "JB1") (pin "2") (pinfunction "2_2") (pintype "bidirectional"))
      (node (ref "MOTB1-2") (pin "5") (pinfunction "AOUT2_5") (pintype "bidirectional"))
      (node (ref "MOTB1-2") (pin "6") (pinfunction "AOUT2_6") (pintype "bidirectional"))
    )
    (net (code "195") (name "Net-(JB2-Pad1)") (class "Default")
      (node (ref "JB2") (pin "1") (pinfunction "1_1") (pintype "bidirectional"))
      (node (ref "MOTB1-2") (pin "7") (pinfunction "BOUT2_7") (pintype "bidirectional"))
      (node (ref "MOTB1-2") (pin "8") (pinfunction "BOUT2_8") (pintype "bidirectional"))
    )
    (net (code "196") (name "Net-(JB2-Pad2)") (class "Default")
      (node (ref "JB2") (pin "2") (pinfunction "2_2") (pintype "bidirectional"))
      (node (ref "MOTB1-2") (pin "10") (pinfunction "BOUT1_10") (pintype "bidirectional"))
      (node (ref "MOTB1-2") (pin "9") (pinfunction "BOUT1_9") (pintype "bidirectional"))
    )
    (net (code "197") (name "Net-(JB3-Pad1)") (class "Default")
      (node (ref "JB3") (pin "1") (pinfunction "1_1") (pintype "bidirectional"))
      (node (ref "MOTB3-4") (pin "3") (pinfunction "AOUT1_3") (pintype "bidirectional"))
      (node (ref "MOTB3-4") (pin "4") (pinfunction "AOUT1_4") (pintype "bidirectional"))
    )
    (net (code "198") (name "Net-(JB3-Pad2)") (class "Default")
      (node (ref "JB3") (pin "2") (pinfunction "2_2") (pintype "bidirectional"))
      (node (ref "MOTB3-4") (pin "5") (pinfunction "AOUT2_5") (pintype "bidirectional"))
      (node (ref "MOTB3-4") (pin "6") (pinfunction "AOUT2_6") (pintype "bidirectional"))
    )
    (net (code "199") (name "Net-(JB4-Pad1)") (class "Default")
      (node (ref "JB4") (pin "1") (pinfunction "1_1") (pintype "bidirectional"))
      (node (ref "MOTB3-4") (pin "7") (pinfunction "BOUT2_7") (pintype "bidirectional"))
      (node (ref "MOTB3-4") (pin "8") (pinfunction "BOUT2_8") (pintype "bidirectional"))
    )
    (net (code "200") (name "Net-(JB4-Pad2)") (class "Default")
      (node (ref "JB4") (pin "2") (pinfunction "2_2") (pintype "bidirectional"))
      (node (ref "MOTB3-4") (pin "10") (pinfunction "BOUT1_10") (pintype "bidirectional"))
      (node (ref "MOTB3-4") (pin "9") (pinfunction "BOUT1_9") (pintype "bidirectional"))
    )
    (net (code "201") (name "Net-(JB5-Pad1)") (class "Default")
      (node (ref "JB5") (pin "1") (pinfunction "1_1") (pintype "bidirectional"))
      (node (ref "MOTB5-6") (pin "3") (pinfunction "AOUT1_3") (pintype "bidirectional"))
      (node (ref "MOTB5-6") (pin "4") (pinfunction "AOUT1_4") (pintype "bidirectional"))
    )
    (net (code "202") (name "Net-(JB5-Pad2)") (class "Default")
      (node (ref "JB5") (pin "2") (pinfunction "2_2") (pintype "bidirectional"))
      (node (ref "MOTB5-6") (pin "5") (pinfunction "AOUT2_5") (pintype "bidirectional"))
      (node (ref "MOTB5-6") (pin "6") (pinfunction "AOUT2_6") (pintype "bidirectional"))
    )
    (net (code "203") (name "Net-(JB6-Pad1)") (class "Default")
      (node (ref "JB6") (pin "1") (pinfunction "1_1") (pintype "bidirectional"))
      (node (ref "MOTB5-6") (pin "7") (pinfunction "BOUT2_7") (pintype "bidirectional"))
      (node (ref "MOTB5-6") (pin "8") (pinfunction "BOUT2_8") (pintype "bidirectional"))
    )
    (net (code "204") (name "Net-(JB6-Pad2)") (class "Default")
      (node (ref "JB6") (pin "2") (pinfunction "2_2") (pintype "bidirectional"))
      (node (ref "MOTB5-6") (pin "10") (pinfunction "BOUT1_10") (pintype "bidirectional"))
      (node (ref "MOTB5-6") (pin "9") (pinfunction "BOUT1_9") (pintype "bidirectional"))
    )
    (net (code "205") (name "Net-(JB7-Pad1)") (class "Default")
      (node (ref "JB7") (pin "1") (pinfunction "1_1") (pintype "bidirectional"))
      (node (ref "MOTB7-8") (pin "3") (pinfunction "AOUT1_3") (pintype "bidirectional"))
      (node (ref "MOTB7-8") (pin "4") (pinfunction "AOUT1_4") (pintype "bidirectional"))
    )
    (net (code "206") (name "Net-(JB7-Pad2)") (class "Default")
      (node (ref "JB7") (pin "2") (pinfunction "2_2") (pintype "bidirectional"))
      (node (ref "MOTB7-8") (pin "5") (pinfunction "AOUT2_5") (pintype "bidirectional"))
      (node (ref "MOTB7-8") (pin "6") (pinfunction "AOUT2_6") (pintype "bidirectional"))
    )
    (net (code "207") (name "Net-(JB8-Pad1)") (class "Default")
      (node (ref "JB8") (pin "1") (pinfunction "1_1") (pintype "bidirectional"))
      (node (ref "MOTB7-8") (pin "7") (pinfunction "BOUT2_7") (pintype "bidirectional"))
      (node (ref "MOTB7-8") (pin "8") (pinfunction "BOUT2_8") (pintype "bidirectional"))
    )
    (net (code "208") (name "Net-(JB8-Pad2)") (class "Default")
      (node (ref "JB8") (pin "2") (pinfunction "2_2") (pintype "bidirectional"))
      (node (ref "MOTB7-8") (pin "10") (pinfunction "BOUT1_10") (pintype "bidirectional"))
      (node (ref "MOTB7-8") (pin "9") (pinfunction "BOUT1_9") (pintype "bidirectional"))
    )
    (net (code "209") (name "Net-(LED1-PadA)") (class "Default")
      (node (ref "LED1") (pin "A") (pinfunction "A_A") (pintype "passive"))
      (node (ref "R37") (pin "1") (pinfunction "1_1") (pintype "passive"))
    )
    (net (code "210") (name "Net-(LED2-PadA)") (class "Default")
      (node (ref "LED2") (pin "A") (pinfunction "A_A") (pintype "passive"))
      (node (ref "R45") (pin "1") (pinfunction "1_1") (pintype "passive"))
    )
    (net (code "211") (name "Net-(LED3-PadA)") (class "Default")
      (node (ref "LED3") (pin "A") (pinfunction "A_A") (pintype "passive"))
      (node (ref "R48") (pin "1") (pinfunction "1_1") (pintype "passive"))
    )
    (net (code "212") (name "Net-(LED4-PadA)") (class "Default")
      (node (ref "LED4") (pin "A") (pinfunction "A_A") (pintype "passive"))
      (node (ref "R51") (pin "1") (pinfunction "1_1") (pintype "passive"))
    )
    (net (code "213") (name "Net-(LED5-PadA)") (class "Default")
      (node (ref "LED5") (pin "A") (pinfunction "A_A") (pintype "passive"))
      (node (ref "R54") (pin "1") (pinfunction "1_1") (pintype "passive"))
    )
    (net (code "214") (name "Net-(LED6-PadA)") (class "Default")
      (node (ref "LED6") (pin "A") (pinfunction "A_A") (pintype "passive"))
      (node (ref "R57") (pin "1") (pinfunction "1_1") (pintype "passive"))
    )
    (net (code "215") (name "Net-(MOS1-R1,C1)") (class "Default")
      (node (ref "C40") (pin "1") (pinfunction "1_1") (pintype "passive"))
      (node (ref "MOS1") (pin "6") (pinfunction "R1,C1_6") (pintype "bidirectional"))
      (node (ref "R25") (pin "2") (pinfunction "2_2") (pintype "passive"))
    )
    (net (code "216") (name "Net-(MOS1-R2)") (class "Default")
      (node (ref "MOS1") (pin "1") (pinfunction "R2_1") (pintype "bidirectional"))
      (node (ref "R26") (pin "2") (pinfunction "2_2") (pintype "passive"))
    )
    (net (code "217") (name "Net-(MOS2-R1,C1)") (class "Default")
      (node (ref "C6") (pin "1") (pinfunction "1_1") (pintype "passive"))
      (node (ref "MOS2") (pin "6") (pinfunction "R1,C1_6") (pintype "bidirectional"))
      (node (ref "R29") (pin "2") (pinfunction "2_2") (pintype "passive"))
    )
    (net (code "218") (name "Net-(MOS2-R2)") (class "Default")
      (node (ref "MOS2") (pin "1") (pinfunction "R2_1") (pintype "bidirectional"))
      (node (ref "R30") (pin "2") (pinfunction "2_2") (pintype "passive"))
    )
    (net (code "219") (name "Net-(MOS3-R1,C1)") (class "Default")
      (node (ref "C8") (pin "1") (pinfunction "1_1") (pintype "passive"))
      (node (ref "MOS3") (pin "6") (pinfunction "R1,C1_6") (pintype "bidirectional"))
      (node (ref "R31") (pin "2") (pinfunction "2_2") (pintype "passive"))
    )
    (net (code "220") (name "Net-(MOS3-R2)") (class "Default")
      (node (ref "MOS3") (pin "1") (pinfunction "R2_1") (pintype "bidirectional"))
      (node (ref "R32") (pin "2") (pinfunction "2_2") (pintype "passive"))
    )
    (net (code "221") (name "Net-(MOS4-R1,C1)") (class "Default")
      (node (ref "C10") (pin "1") (pinfunction "1_1") (pintype "passive"))
      (node (ref "MOS4") (pin "6") (pinfunction "R1,C1_6") (pintype "bidirectional"))
      (node (ref "R33") (pin "2") (pinfunction "2_2") (pintype "passive"))
    )
    (net (code "222") (name "Net-(MOS4-R2)") (class "Default")
      (node (ref "MOS4") (pin "1") (pinfunction "R2_1") (pintype "bidirectional"))
      (node (ref "R34") (pin "2") (pinfunction "2_2") (pintype "passive"))
    )
    (net (code "223") (name "Net-(MOS5-R1,C1)") (class "Default")
      (node (ref "C5") (pin "1") (pinfunction "1_1") (pintype "passive"))
      (node (ref "MOS5") (pin "6") (pinfunction "R1,C1_6") (pintype "bidirectional"))
      (node (ref "R10") (pin "2") (pinfunction "2_2") (pintype "passive"))
    )
    (net (code "224") (name "Net-(MOS5-R2)") (class "Default")
      (node (ref "MOS5") (pin "1") (pinfunction "R2_1") (pintype "bidirectional"))
      (node (ref "R27") (pin "2") (pinfunction "2_2") (pintype "passive"))
    )
    (net (code "225") (name "Net-(MOS6-R1,C1)") (class "Default")
      (node (ref "C28") (pin "1") (pinfunction "1_1") (pintype "passive"))
      (node (ref "MOS6") (pin "6") (pinfunction "R1,C1_6") (pintype "bidirectional"))
      (node (ref "R28") (pin "2") (pinfunction "2_2") (pintype "passive"))
    )
    (net (code "226") (name "Net-(MOS6-R2)") (class "Default")
      (node (ref "MOS6") (pin "1") (pinfunction "R2_1") (pintype "bidirectional"))
      (node (ref "R38") (pin "2") (pinfunction "2_2") (pintype "passive"))
    )
    (net (code "227") (name "Net-(MOS7-R1,C1)") (class "Default")
      (node (ref "C30") (pin "1") (pinfunction "1_1") (pintype "passive"))
      (node (ref "MOS7") (pin "6") (pinfunction "R1,C1_6") (pintype "bidirectional"))
      (node (ref "R39") (pin "2") (pinfunction "2_2") (pintype "passive"))
    )
    (net (code "228") (name "Net-(MOS7-R2)") (class "Default")
      (node (ref "MOS7") (pin "1") (pinfunction "R2_1") (pintype "bidirectional"))
      (node (ref "R40") (pin "2") (pinfunction "2_2") (pintype "passive"))
    )
    (net (code "229") (name "Net-(MOS8-R1,C1)") (class "Default")
      (node (ref "C32") (pin "1") (pinfunction "1_1") (pintype "passive"))
      (node (ref "MOS8") (pin "6") (pinfunction "R1,C1_6") (pintype "bidirectional"))
      (node (ref "R41") (pin "2") (pinfunction "2_2") (pintype "passive"))
    )
    (net (code "230") (name "Net-(MOS8-R2)") (class "Default")
      (node (ref "MOS8") (pin "1") (pinfunction "R2_1") (pintype "bidirectional"))
      (node (ref "R42") (pin "2") (pinfunction "2_2") (pintype "passive"))
    )
    (net (code "231") (name "Net-(P1-A)") (class "Default")
      (node (ref "P1") (pin "1") (pinfunction "A_1") (pintype "passive"))
      (node (ref "SOL1") (pin "1") (pinfunction "DUTY_1") (pintype "bidirectional"))
    )
    (net (code "232") (name "Net-(P1-E)") (class "Default")
      (node (ref "P1") (pin "2") (pinfunction "S_2") (pintype "passive"))
      (node (ref "P1") (pin "3") (pinfunction "E_3") (pintype "passive"))
      (node (ref "R36") (pin "2") (pinfunction "2_2") (pintype "passive"))
    )
    (net (code "233") (name "Net-(P2-A)") (class "Default")
      (node (ref "P2") (pin "1") (pinfunction "A_1") (pintype "passive"))
      (node (ref "SOL2") (pin "1") (pinfunction "DUTY_1") (pintype "bidirectional"))
    )
    (net (code "234") (name "Net-(P2-E)") (class "Default")
      (node (ref "P2") (pin "2") (pinfunction "S_2") (pintype "passive"))
      (node (ref "P2") (pin "3") (pinfunction "E_3") (pintype "passive"))
      (node (ref "R44") (pin "2") (pinfunction "2_2") (pintype "passive"))
    )
    (net (code "235") (name "Net-(P3-A)") (class "Default")
      (node (ref "P3") (pin "1") (pinfunction "A_1") (pintype "passive"))
      (node (ref "SOL3") (pin "1") (pinfunction "DUTY_1") (pintype "bidirectional"))
    )
    (net (code "236") (name "Net-(P3-E)") (class "Default")
      (node (ref "P3") (pin "2") (pinfunction "S_2") (pintype "passive"))
      (node (ref "P3") (pin "3") (pinfunction "E_3") (pintype "passive"))
      (node (ref "R47") (pin "2") (pinfunction "2_2") (pintype "passive"))
    )
    (net (code "237") (name "Net-(P4-A)") (class "Default")
      (node (ref "P4") (pin "1") (pinfunction "A_1") (pintype "passive"))
      (node (ref "SOL4") (pin "1") (pinfunction "DUTY_1") (pintype "bidirectional"))
    )
    (net (code "238") (name "Net-(P4-E)") (class "Default")
      (node (ref "P4") (pin "2") (pinfunction "S_2") (pintype "passive"))
      (node (ref "P4") (pin "3") (pinfunction "E_3") (pintype "passive"))
      (node (ref "R50") (pin "2") (pinfunction "2_2") (pintype "passive"))
    )
    (net (code "239") (name "Net-(P5-A)") (class "Default")
      (node (ref "P5") (pin "1") (pinfunction "A_1") (pintype "passive"))
      (node (ref "SOL5") (pin "1") (pinfunction "DUTY_1") (pintype "bidirectional"))
    )
    (net (code "240") (name "Net-(P5-E)") (class "Default")
      (node (ref "P5") (pin "2") (pinfunction "S_2") (pintype "passive"))
      (node (ref "P5") (pin "3") (pinfunction "E_3") (pintype "passive"))
      (node (ref "R53") (pin "2") (pinfunction "2_2") (pintype "passive"))
    )
    (net (code "241") (name "Net-(P6-A)") (class "Default")
      (node (ref "P6") (pin "1") (pinfunction "A_1") (pintype "passive"))
      (node (ref "SOL6") (pin "1") (pinfunction "DUTY_1") (pintype "bidirectional"))
    )
    (net (code "242") (name "Net-(P6-E)") (class "Default")
      (node (ref "P6") (pin "2") (pinfunction "S_2") (pintype "passive"))
      (node (ref "P6") (pin "3") (pinfunction "E_3") (pintype "passive"))
      (node (ref "R56") (pin "2") (pinfunction "2_2") (pintype "passive"))
    )
    (net (code "243") (name "Net-(P7-A)") (class "Default")
      (node (ref "P7") (pin "1") (pinfunction "A_1") (pintype "passive"))
      (node (ref "R74") (pin "1") (pinfunction "1_1") (pintype "passive"))
    )
    (net (code "244") (name "Net-(P7-E)") (class "Default")
      (node (ref "P7") (pin "3") (pinfunction "E_3") (pintype "passive"))
      (node (ref "R75") (pin "2") (pinfunction "2_2") (pintype "passive"))
    )
    (net (code "245") (name "Net-(P8-A)") (class "Default")
      (node (ref "P8") (pin "1") (pinfunction "A_1") (pintype "passive"))
      (node (ref "R76") (pin "1") (pinfunction "1_1") (pintype "passive"))
    )
    (net (code "246") (name "Net-(P8-E)") (class "Default")
      (node (ref "P8") (pin "3") (pinfunction "E_3") (pintype "passive"))
      (node (ref "R77") (pin "2") (pinfunction "2_2") (pintype "passive"))
    )
    (net (code "247") (name "Net-(P9-A)") (class "Default")
      (node (ref "P9") (pin "1") (pinfunction "A_1") (pintype "passive"))
      (node (ref "R80") (pin "1") (pinfunction "1_1") (pintype "passive"))
    )
    (net (code "248") (name "Net-(P9-E)") (class "Default")
      (node (ref "P9") (pin "3") (pinfunction "E_3") (pintype "passive"))
      (node (ref "R81") (pin "2") (pinfunction "2_2") (pintype "passive"))
    )
    (net (code "249") (name "Net-(P10-A)") (class "Default")
      (node (ref "P10") (pin "1") (pinfunction "A_1") (pintype "passive"))
      (node (ref "R82") (pin "1") (pinfunction "1_1") (pintype "passive"))
    )
    (net (code "250") (name "Net-(P10-E)") (class "Default")
      (node (ref "P10") (pin "3") (pinfunction "E_3") (pintype "passive"))
      (node (ref "R83") (pin "2") (pinfunction "2_2") (pintype "passive"))
    )
    (net (code "251") (name "Net-(P11-A)") (class "Default")
      (node (ref "P11") (pin "1") (pinfunction "A_1") (pintype "passive"))
      (node (ref "R84") (pin "1") (pinfunction "1_1") (pintype "passive"))
    )
    (net (code "252") (name "Net-(P11-E)") (class "Default")
      (node (ref "P11") (pin "3") (pinfunction "E_3") (pintype "passive"))
      (node (ref "R85") (pin "2") (pinfunction "2_2") (pintype "passive"))
    )
    (net (code "253") (name "Net-(Q1-D)") (class "Default")
      (node (ref "Q1") (pin "3") (pinfunction "D_3") (pintype "passive"))
      (node (ref "VP1") (pin "3") (pinfunction "~{INHIBIT}_3") (pintype "input"))
    )
    (net (code "254") (name "Net-(Q2-D)") (class "Default")
      (node (ref "Q2") (pin "3") (pinfunction "D_3") (pintype "passive"))
      (node (ref "VP2") (pin "3") (pinfunction "~{INHIBIT}_3") (pintype "input"))
    )
    (net (code "255") (name "Net-(Q3-D)") (class "Default")
      (node (ref "Q3") (pin "3") (pinfunction "D_3") (pintype "passive"))
      (node (ref "VP3") (pin "3") (pinfunction "~{INHIBIT}_3") (pintype "input"))
    )
    (net (code "256") (name "Net-(Q4-D)") (class "Default")
      (node (ref "Q4") (pin "3") (pinfunction "D_3") (pintype "passive"))
      (node (ref "VP4") (pin "3") (pinfunction "~{INHIBIT}_3") (pintype "input"))
    )
    (net (code "257") (name "Net-(SENSE_VBAT-VIN+)") (class "Default")
      (node (ref "JSW") (pin "3") (pinfunction "3_3") (pintype "bidirectional"))
      (node (ref "R90") (pin "1") (pinfunction "1_1") (pintype "passive"))
      (node (ref "SENSE_VBAT") (pin "3") (pinfunction "VIN+_3") (pintype "bidirectional"))
    )
    (net (code "258") (name "Net-(SENSE_VP1-VIN+)") (class "Default")
      (node (ref "C20") (pin "1") (pinfunction "1_1") (pintype "passive"))
      (node (ref "L4") (pin "2") (pinfunction "2_2") (pintype "passive"))
      (node (ref "R8") (pin "1") (pinfunction "1_1") (pintype "passive"))
      (node (ref "SENSE_VP1") (pin "3") (pinfunction "VIN+_3") (pintype "bidirectional"))
    )
    (net (code "259") (name "Net-(SENSE_VP2-VIN+)") (class "Default")
      (node (ref "C22") (pin "1") (pinfunction "1_1") (pintype "passive"))
      (node (ref "L5") (pin "2") (pinfunction "2_2") (pintype "passive"))
      (node (ref "R11") (pin "1") (pinfunction "1_1") (pintype "passive"))
      (node (ref "SENSE_VP2") (pin "3") (pinfunction "VIN+_3") (pintype "bidirectional"))
    )
    (net (code "260") (name "Net-(SENSE_VP3-VIN+)") (class "Default")
      (node (ref "C24") (pin "1") (pinfunction "1_1") (pintype "passive"))
      (node (ref "L6") (pin "2") (pinfunction "2_2") (pintype "passive"))
      (node (ref "R14") (pin "1") (pinfunction "1_1") (pintype "passive"))
      (node (ref "SENSE_VP3") (pin "3") (pinfunction "VIN+_3") (pintype "bidirectional"))
    )
    (net (code "261") (name "Net-(SENSE_VP4-VIN+)") (class "Default")
      (node (ref "C26") (pin "1") (pinfunction "1_1") (pintype "passive"))
      (node (ref "L7") (pin "2") (pinfunction "2_2") (pintype "passive"))
      (node (ref "R16") (pin "1") (pinfunction "1_1") (pintype "passive"))
      (node (ref "SENSE_VP4") (pin "3") (pinfunction "VIN+_3") (pintype "bidirectional"))
    )
    (net (code "262") (name "Net-(SOL1-DELAY)") (class "Default")
      (node (ref "C12") (pin "1") (pinfunction "1_1") (pintype "passive"))
      (node (ref "SOL1") (pin "2") (pinfunction "DELAY_2") (pintype "bidirectional"))
    )
    (net (code "263") (name "Net-(SOL1-FREQ)") (class "Default")
      (node (ref "R35") (pin "2") (pinfunction "2_2") (pintype "passive"))
      (node (ref "SOL1") (pin "3") (pinfunction "FREQ_3") (pintype "bidirectional"))
    )
    (net (code "264") (name "Net-(SOL1-STATUS)") (class "Default")
      (node (ref "LED1") (pin "C") (pinfunction "C_C") (pintype "passive"))
      (node (ref "SOL1") (pin "7") (pinfunction "STATUS_7") (pintype "bidirectional"))
    )
    (net (code "265") (name "Net-(SOL2-DELAY)") (class "Default")
      (node (ref "C34") (pin "1") (pinfunction "1_1") (pintype "passive"))
      (node (ref "SOL2") (pin "2") (pinfunction "DELAY_2") (pintype "bidirectional"))
    )
    (net (code "266") (name "Net-(SOL2-FREQ)") (class "Default")
      (node (ref "R43") (pin "2") (pinfunction "2_2") (pintype "passive"))
      (node (ref "SOL2") (pin "3") (pinfunction "FREQ_3") (pintype "bidirectional"))
    )
    (net (code "267") (name "Net-(SOL2-STATUS)") (class "Default")
      (node (ref "LED2") (pin "C") (pinfunction "C_C") (pintype "passive"))
      (node (ref "SOL2") (pin "7") (pinfunction "STATUS_7") (pintype "bidirectional"))
    )
    (net (code "268") (name "Net-(SOL3-DELAY)") (class "Default")
      (node (ref "C36") (pin "1") (pinfunction "1_1") (pintype "passive"))
      (node (ref "SOL3") (pin "2") (pinfunction "DELAY_2") (pintype "bidirectional"))
    )
    (net (code "269") (name "Net-(SOL3-FREQ)") (class "Default")
      (node (ref "R46") (pin "2") (pinfunction "2_2") (pintype "passive"))
      (node (ref "SOL3") (pin "3") (pinfunction "FREQ_3") (pintype "bidirectional"))
    )
    (net (code "270") (name "Net-(SOL3-STATUS)") (class "Default")
      (node (ref "LED3") (pin "C") (pinfunction "C_C") (pintype "passive"))
      (node (ref "SOL3") (pin "7") (pinfunction "STATUS_7") (pintype "bidirectional"))
    )
    (net (code "271") (name "Net-(SOL4-DELAY)") (class "Default")
      (node (ref "C38") (pin "1") (pinfunction "1_1") (pintype "passive"))
      (node (ref "SOL4") (pin "2") (pinfunction "DELAY_2") (pintype "bidirectional"))
    )
    (net (code "272") (name "Net-(SOL4-FREQ)") (class "Default")
      (node (ref "R49") (pin "2") (pinfunction "2_2") (pintype "passive"))
      (node (ref "SOL4") (pin "3") (pinfunction "FREQ_3") (pintype "bidirectional"))
    )
    (net (code "273") (name "Net-(SOL4-STATUS)") (class "Default")
      (node (ref "LED4") (pin "C") (pinfunction "C_C") (pintype "passive"))
      (node (ref "SOL4") (pin "7") (pinfunction "STATUS_7") (pintype "bidirectional"))
    )
    (net (code "274") (name "Net-(SOL5-DELAY)") (class "Default")
      (node (ref "C42") (pin "1") (pinfunction "1_1") (pintype "passive"))
      (node (ref "SOL5") (pin "2") (pinfunction "DELAY_2") (pintype "bidirectional"))
    )
    (net (code "275") (name "Net-(SOL5-FREQ)") (class "Default")
      (node (ref "R52") (pin "2") (pinfunction "2_2") (pintype "passive"))
      (node (ref "SOL5") (pin "3") (pinfunction "FREQ_3") (pintype "bidirectional"))
    )
    (net (code "276") (name "Net-(SOL5-STATUS)") (class "Default")
      (node (ref "LED5") (pin "C") (pinfunction "C_C") (pintype "passive"))
      (node (ref "SOL5") (pin "7") (pinfunction "STATUS_7") (pintype "bidirectional"))
    )
    (net (code "277") (name "Net-(SOL6-DELAY)") (class "Default")
      (node (ref "C44") (pin "1") (pinfunction "1_1") (pintype "passive"))
      (node (ref "SOL6") (pin "2") (pinfunction "DELAY_2") (pintype "bidirectional"))
    )
    (net (code "278") (name "Net-(SOL6-FREQ)") (class "Default")
      (node (ref "R55") (pin "2") (pinfunction "2_2") (pintype "passive"))
      (node (ref "SOL6") (pin "3") (pinfunction "FREQ_3") (pintype "bidirectional"))
    )
    (net (code "279") (name "Net-(SOL6-STATUS)") (class "Default")
      (node (ref "LED6") (pin "C") (pinfunction "C_C") (pintype "passive"))
      (node (ref "SOL6") (pin "7") (pinfunction "STATUS_7") (pintype "bidirectional"))
    )
    (net (code "280") (name "Net-(VP1-VO)") (class "Default")
      (node (ref "C19") (pin "+") (pinfunction "+_+") (pintype "passive"))
      (node (ref "L4") (pin "1") (pinfunction "1_1") (pintype "passive"))
      (node (ref "VP1") (pin "5") (pinfunction "VO_SENSE_5") (pintype "input"))
      (node (ref "VP1") (pin "6") (pinfunction "VO_6") (pintype "power_in"))
    )
    (net (code "281") (name "Net-(VP1-VO_ADJ)") (class "Default")
      (node (ref "R4") (pin "2") (pinfunction "2_2") (pintype "passive"))
      (node (ref "VP1") (pin "4") (pinfunction "VO_ADJ_4") (pintype "power_in"))
    )
    (net (code "282") (name "Net-(VP2-VO)") (class "Default")
      (node (ref "C21") (pin "+") (pinfunction "+_+") (pintype "passive"))
      (node (ref "L5") (pin "1") (pinfunction "1_1") (pintype "passive"))
      (node (ref "VP2") (pin "5") (pinfunction "VO_SENSE_5") (pintype "input"))
      (node (ref "VP2") (pin "6") (pinfunction "VO_6") (pintype "power_in"))
    )
    (net (code "283") (name "Net-(VP2-VO_ADJ)") (class "Default")
      (node (ref "R5") (pin "2") (pinfunction "2_2") (pintype "passive"))
      (node (ref "VP2") (pin "4") (pinfunction "VO_ADJ_4") (pintype "power_in"))
    )
    (net (code "284") (name "Net-(VP3-VO)") (class "Default")
      (node (ref "C23") (pin "+") (pinfunction "+_+") (pintype "passive"))
      (node (ref "L6") (pin "1") (pinfunction "1_1") (pintype "passive"))
      (node (ref "VP3") (pin "5") (pinfunction "VO_SENSE_5") (pintype "input"))
      (node (ref "VP3") (pin "6") (pinfunction "VO_6") (pintype "power_in"))
    )
    (net (code "285") (name "Net-(VP3-VO_ADJ)") (class "Default")
      (node (ref "R6") (pin "2") (pinfunction "2_2") (pintype "passive"))
      (node (ref "VP3") (pin "4") (pinfunction "VO_ADJ_4") (pintype "power_in"))
    )
    (net (code "286") (name "Net-(VP4-VO)") (class "Default")
      (node (ref "C25") (pin "+") (pinfunction "+_+") (pintype "passive"))
      (node (ref "L7") (pin "1") (pinfunction "1_1") (pintype "passive"))
      (node (ref "VP4") (pin "5") (pinfunction "VO_SENSE_5") (pintype "input"))
      (node (ref "VP4") (pin "6") (pinfunction "VO_6") (pintype "power_in"))
    )
    (net (code "287") (name "Net-(VP4-VO_ADJ)") (class "Default")
      (node (ref "R7") (pin "2") (pinfunction "2_2") (pintype "passive"))
      (node (ref "VP4") (pin "4") (pinfunction "VO_ADJ_4") (pintype "power_in"))
    )
    (net (code "288") (name "SOL1_EN") (class "Default")
      (node (ref "IOE2") (pin "2") (pinfunction "GPB1_2") (pintype "bidirectional"))
      (node (ref "SOL1") (pin "8") (pinfunction "IN_8") (pintype "bidirectional"))
    )
    (net (code "289") (name "SOL1_OUT") (class "Default")
      (node (ref "D1") (pin "A") (pinfunction "A_A") (pintype "passive"))
      (node (ref "JS1") (pin "2") (pinfunction "2_2") (pintype "bidirectional"))
      (node (ref "SOL1") (pin "5") (pinfunction "OUT_5") (pintype "bidirectional"))
    )
    (net (code "290") (name "SOL2_EN") (class "Default")
      (node (ref "IOE2") (pin "3") (pinfunction "GPB2_3") (pintype "bidirectional"))
      (node (ref "SOL2") (pin "8") (pinfunction "IN_8") (pintype "bidirectional"))
    )
    (net (code "291") (name "SOL2_OUT") (class "Default")
      (node (ref "D2") (pin "A") (pinfunction "A_A") (pintype "passive"))
      (node (ref "JS2") (pin "2") (pinfunction "2_2") (pintype "bidirectional"))
      (node (ref "SOL2") (pin "5") (pinfunction "OUT_5") (pintype "bidirectional"))
    )
    (net (code "292") (name "SOL3_EN") (class "Default")
      (node (ref "IOE2") (pin "4") (pinfunction "GPB3_4") (pintype "bidirectional"))
      (node (ref "SOL3") (pin "8") (pinfunction "IN_8") (pintype "bidirectional"))
    )
    (net (code "293") (name "SOL3_OUT") (class "Default")
      (node (ref "D3") (pin "A") (pinfunction "A_A") (pintype "passive"))
      (node (ref "JS3") (pin "2") (pinfunction "2_2") (pintype "bidirectional"))
      (node (ref "SOL3") (pin "5") (pinfunction "OUT_5") (pintype "bidirectional"))
    )
    (net (code "294") (name "SOL4_EN") (class "Default")
      (node (ref "IOE2") (pin "5") (pinfunction "GPB4_5") (pintype "bidirectional"))
      (node (ref "SOL4") (pin "8") (pinfunction "IN_8") (pintype "bidirectional"))
    )
    (net (code "295") (name "SOL4_OUT") (class "Default")
      (node (ref "D4") (pin "A") (pinfunction "A_A") (pintype "passive"))
      (node (ref "JS4") (pin "2") (pinfunction "2_2") (pintype "bidirectional"))
      (node (ref "SOL4") (pin "5") (pinfunction "OUT_5") (pintype "bidirectional"))
    )
    (net (code "296") (name "SOL5_EN") (class "Default")
      (node (ref "IOE2") (pin "6") (pinfunction "GPB5_6") (pintype "bidirectional"))
      (node (ref "SOL5") (pin "8") (pinfunction "IN_8") (pintype "bidirectional"))
    )
    (net (code "297") (name "SOL5_OUT") (class "Default")
      (node (ref "D5") (pin "A") (pinfunction "A_A") (pintype "passive"))
      (node (ref "JS5") (pin "2") (pinfunction "2_2") (pintype "bidirectional"))
      (node (ref "SOL5") (pin "5") (pinfunction "OUT_5") (pintype "bidirectional"))
    )
    (net (code "298") (name "SOL6_EN") (class "Default")
      (node (ref "IOE2") (pin "7") (pinfunction "GPB6_7") (pintype "bidirectional"))
      (node (ref "SOL6") (pin "8") (pinfunction "IN_8") (pintype "bidirectional"))
    )
    (net (code "299") (name "SOL6_OUT") (class "Default")
      (node (ref "D6") (pin "A") (pinfunction "A_A") (pintype "passive"))
      (node (ref "JS6") (pin "2") (pinfunction "2_2") (pintype "bidirectional"))
      (node (ref "SOL6") (pin "5") (pinfunction "OUT_5") (pintype "bidirectional"))
    )
    (net (code "300") (name "SPI_MISO") (class "Default")
      (node (ref "ADC1") (pin "16") (pinfunction "D_OUT_16") (pintype "bidirectional"))
      (node (ref "ADC2") (pin "16") (pinfunction "D_OUT_16") (pintype "bidirectional"))
      (node (ref "IOE1") (pin "14") (pinfunction "SO_14") (pintype "output"))
      (node (ref "IOE2") (pin "14") (pinfunction "SO_14") (pintype "output"))
      (node (ref "IOE3") (pin "14") (pinfunction "SO_14") (pintype "output"))
      (node (ref "JCTRL") (pin "5") (pinfunction "5_5") (pintype "bidirectional"))
    )
    (net (code "301") (name "SPI_MOSI") (class "Default")
      (node (ref "ADC1") (pin "17") (pinfunction "D_IN_17") (pintype "bidirectional"))
      (node (ref "ADC2") (pin "17") (pinfunction "D_IN_17") (pintype "bidirectional"))
      (node (ref "IOE1") (pin "13") (pinfunction "SI_13") (pintype "input"))
      (node (ref "IOE2") (pin "13") (pinfunction "SI_13") (pintype "input"))
      (node (ref "IOE3") (pin "13") (pinfunction "SI_13") (pintype "input"))
      (node (ref "JCTRL") (pin "4") (pinfunction "4_4") (pintype "bidirectional"))
    )
    (net (code "302") (name "SPI_SCK") (class "Default")
      (node (ref "ADC1") (pin "18") (pinfunction "I/O_CLK_18") (pintype "bidirectional"))
      (node (ref "ADC2") (pin "18") (pinfunction "I/O_CLK_18") (pintype "bidirectional"))
      (node (ref "IOE1") (pin "12") (pinfunction "SCK_12") (pintype "input"))
      (node (ref "IOE2") (pin "12") (pinfunction "SCK_12") (pintype "input"))
      (node (ref "IOE3") (pin "12") (pinfunction "SCK_12") (pintype "input"))
      (node (ref "JCTRL") (pin "3") (pinfunction "3_3") (pintype "bidirectional"))
    )
    (net (code "303") (name "SPI_~{CS}_ADC1") (class "Default")
      (node (ref "ADC1") (pin "15") (pinfunction "~{CS}_15") (pintype "bidirectional"))
      (node (ref "JCTRL") (pin "6") (pinfunction "6_6") (pintype "bidirectional"))
    )
    (net (code "304") (name "SPI_~{CS}_ADC2") (class "Default")
      (node (ref "ADC2") (pin "15") (pinfunction "~{CS}_15") (pintype "bidirectional"))
      (node (ref "JCTRL") (pin "7") (pinfunction "7_7") (pintype "bidirectional"))
    )
    (net (code "305") (name "SPI_~{CS}_IOE") (class "Default")
      (node (ref "IOE1") (pin "11") (pinfunction "~{CS}_11") (pintype "input"))
      (node (ref "IOE2") (pin "11") (pinfunction "~{CS}_11") (pintype "input"))
      (node (ref "IOE3") (pin "11") (pinfunction "~{CS}_11") (pintype "input"))
      (node (ref "JCTRL") (pin "8") (pinfunction "8_8") (pintype "bidirectional"))
    )
    (net (code "306") (name "VBAT_SEN") (class "Default")
      (node (ref "IC2") (pin "3") (pinfunction "+IN_3") (pintype "input"))
      (node (ref "R91") (pin "2") (pinfunction "2_2") (pintype "passive"))
      (node (ref "SENSE_VBAT") (pin "1") (pinfunction "OUT_1") (pintype "bidirectional"))
    )
    (net (code "307") (name "VP1_SEN") (class "Default")
      (node (ref "IC1") (pin "3") (pinfunction "+IN_3") (pintype "input"))
      (node (ref "R12") (pin "2") (pinfunction "2_2") (pintype "passive"))
      (node (ref "SENSE_VP1") (pin "1") (pinfunction "OUT_1") (pintype "bidirectional"))
    )
    (net (code "308") (name "VP1_~{EN}") (class "Default")
      (node (ref "IOE1") (pin "1") (pinfunction "GPB0_1") (pintype "bidirectional"))
      (node (ref "Q1") (pin "1") (pinfunction "G_1") (pintype "passive"))
    )
    (net (code "309") (name "VP2_SEN") (class "Default")
      (node (ref "IC1") (pin "5") (pinfunction "+IN_5") (pintype "input"))
      (node (ref "R13") (pin "2") (pinfunction "2_2") (pintype "passive"))
      (node (ref "SENSE_VP2") (pin "1") (pinfunction "OUT_1") (pintype "bidirectional"))
    )
    (net (code "310") (name "VP2_~{EN}") (class "Default")
      (node (ref "IOE1") (pin "2") (pinfunction "GPB1_2") (pintype "bidirectional"))
      (node (ref "Q2") (pin "1") (pinfunction "G_1") (pintype "passive"))
    )
    (net (code "311") (name "VP3_SEN") (class "Default")
      (node (ref "IC1") (pin "10") (pinfunction "+IN_10") (pintype "input"))
      (node (ref "R15") (pin "2") (pinfunction "2_2") (pintype "passive"))
      (node (ref "SENSE_VP3") (pin "1") (pinfunction "OUT_1") (pintype "bidirectional"))
    )
    (net (code "312") (name "VP3_~{EN}") (class "Default")
      (node (ref "IOE1") (pin "3") (pinfunction "GPB2_3") (pintype "bidirectional"))
      (node (ref "Q3") (pin "1") (pinfunction "G_1") (pintype "passive"))
    )
    (net (code "313") (name "VP4_SEN") (class "Default")
      (node (ref "IC1") (pin "12") (pinfunction "+IN_12") (pintype "input"))
      (node (ref "R17") (pin "2") (pinfunction "2_2") (pintype "passive"))
      (node (ref "SENSE_VP4") (pin "1") (pinfunction "OUT_1") (pintype "bidirectional"))
    )
    (net (code "314") (name "VP4_~{EN}") (class "Default")
      (node (ref "IOE1") (pin "4") (pinfunction "GPB3_4") (pintype "bidirectional"))
      (node (ref "Q4") (pin "1") (pinfunction "G_1") (pintype "passive"))
    )
    (net (code "315") (name "VPACK") (class "Default")
      (node (ref "JBAT1") (pin "1") (pinfunction "1_1") (pintype "bidirectional"))
      (node (ref "JSW") (pin "4") (pinfunction "4_4") (pintype "bidirectional"))
    )
    (net (code "316") (name "unconnected-(CEL1-G1-Pad8)") (class "Default")
      (node (ref "CEL1") (pin "8") (pinfunction "G1_8") (pintype "bidirectional"))
    )
    (net (code "317") (name "unconnected-(CEL1-G2-Pad5)") (class "Default")
      (node (ref "CEL1") (pin "5") (pinfunction "G2_5") (pintype "bidirectional"))
    )
    (net (code "318") (name "unconnected-(CEL2-G1-Pad8)") (class "Default")
      (node (ref "CEL2") (pin "8") (pinfunction "G1_8") (pintype "bidirectional"))
    )
    (net (code "319") (name "unconnected-(CEL2-G2-Pad5)") (class "Default")
      (node (ref "CEL2") (pin "5") (pinfunction "G2_5") (pintype "bidirectional"))
    )
    (net (code "320") (name "unconnected-(CEL3-G1-Pad8)") (class "Default")
      (node (ref "CEL3") (pin "8") (pinfunction "G1_8") (pintype "bidirectional"))
    )
    (net (code "321") (name "unconnected-(CEL3-G2-Pad5)") (class "Default")
      (node (ref "CEL3") (pin "5") (pinfunction "G2_5") (pintype "bidirectional"))
    )
    (net (code "322") (name "unconnected-(CEL4-G1-Pad8)") (class "Default")
      (node (ref "CEL4") (pin "8") (pinfunction "G1_8") (pintype "bidirectional"))
    )
    (net (code "323") (name "unconnected-(CEL4-G2-Pad5)") (class "Default")
      (node (ref "CEL4") (pin "5") (pinfunction "G2_5") (pintype "bidirectional"))
    )
    (net (code "324") (name "unconnected-(CEL5-G1-Pad8)") (class "Default")
      (node (ref "CEL5") (pin "8") (pinfunction "G1_8") (pintype "bidirectional"))
    )
    (net (code "325") (name "unconnected-(CEL5-G2-Pad5)") (class "Default")
      (node (ref "CEL5") (pin "5") (pinfunction "G2_5") (pintype "bidirectional"))
    )
    (net (code "326") (name "unconnected-(CEL6-G1-Pad8)") (class "Default")
      (node (ref "CEL6") (pin "8") (pinfunction "G1_8") (pintype "bidirectional"))
    )
    (net (code "327") (name "unconnected-(CEL6-G2-Pad5)") (class "Default")
      (node (ref "CEL6") (pin "5") (pinfunction "G2_5") (pintype "bidirectional"))
    )
    (net (code "328") (name "unconnected-(IOE1-GPA3-Pad24)") (class "Default")
      (node (ref "IOE1") (pin "24") (pinfunction "GPA3_24") (pintype "bidirectional"))
    )
    (net (code "329") (name "unconnected-(IOE1-GPA4-Pad25)") (class "Default")
      (node (ref "IOE1") (pin "25") (pinfunction "GPA4_25") (pintype "bidirectional"))
    )
    (net (code "330") (name "unconnected-(IOE1-GPA5-Pad26)") (class "Default")
      (node (ref "IOE1") (pin "26") (pinfunction "GPA5_26") (pintype "bidirectional"))
    )
    (net (code "331") (name "unconnected-(IOE1-GPA6-Pad27)") (class "Default")
      (node (ref "IOE1") (pin "27") (pinfunction "GPA6_27") (pintype "bidirectional"))
    )
    (net (code "332") (name "unconnected-(IOE1-GPA7-Pad28)") (class "Default")
      (node (ref "IOE1") (pin "28") (pinfunction "GPA7_28") (pintype "bidirectional"))
    )
    (net (code "333") (name "unconnected-(IOE1-GPB4-Pad5)") (class "Default")
      (node (ref "IOE1") (pin "5") (pinfunction "GPB4_5") (pintype "bidirectional"))
    )
    (net (code "334") (name "unconnected-(IOE1-GPB5-Pad6)") (class "Default")
      (node (ref "IOE1") (pin "6") (pinfunction "GPB5_6") (pintype "bidirectional"))
    )
    (net (code "335") (name "unconnected-(IOE1-GPB6-Pad7)") (class "Default")
      (node (ref "IOE1") (pin "7") (pinfunction "GPB6_7") (pintype "bidirectional"))
    )
    (net (code "336") (name "unconnected-(IOE1-GPB7-Pad8)") (class "Default")
      (node (ref "IOE1") (pin "8") (pinfunction "GPB7_8") (pintype "bidirectional"))
    )
    (net (code "337") (name "unconnected-(IOE1-INTA-Pad20)") (class "Default")
      (node (ref "IOE1") (pin "20") (pinfunction "INTA_20") (pintype "output"))
    )
    (net (code "338") (name "unconnected-(IOE1-INTB-Pad19)") (class "Default")
      (node (ref "IOE1") (pin "19") (pinfunction "INTB_19") (pintype "output"))
    )
    (net (code "339") (name "unconnected-(IOE2-GPB7-Pad8)") (class "Default")
      (node (ref "IOE2") (pin "8") (pinfunction "GPB7_8") (pintype "bidirectional"))
    )
    (net (code "340") (name "unconnected-(IOE2-INTA-Pad20)") (class "Default")
      (node (ref "IOE2") (pin "20") (pinfunction "INTA_20") (pintype "output"))
    )
    (net (code "341") (name "unconnected-(IOE2-INTB-Pad19)") (class "Default")
      (node (ref "IOE2") (pin "19") (pinfunction "INTB_19") (pintype "output"))
    )
    (net (code "342") (name "unconnected-(IOE3-INTA-Pad20)") (class "Default")
      (node (ref "IOE3") (pin "20") (pinfunction "INTA_20") (pintype "output"))
    )
    (net (code "343") (name "unconnected-(IOE3-INTB-Pad19)") (class "Default")
      (node (ref "IOE3") (pin "19") (pinfunction "INTB_19") (pintype "output"))
    )
  )
)
